# design.net
KiCad netlist of a schematic drawn in Altium Designer
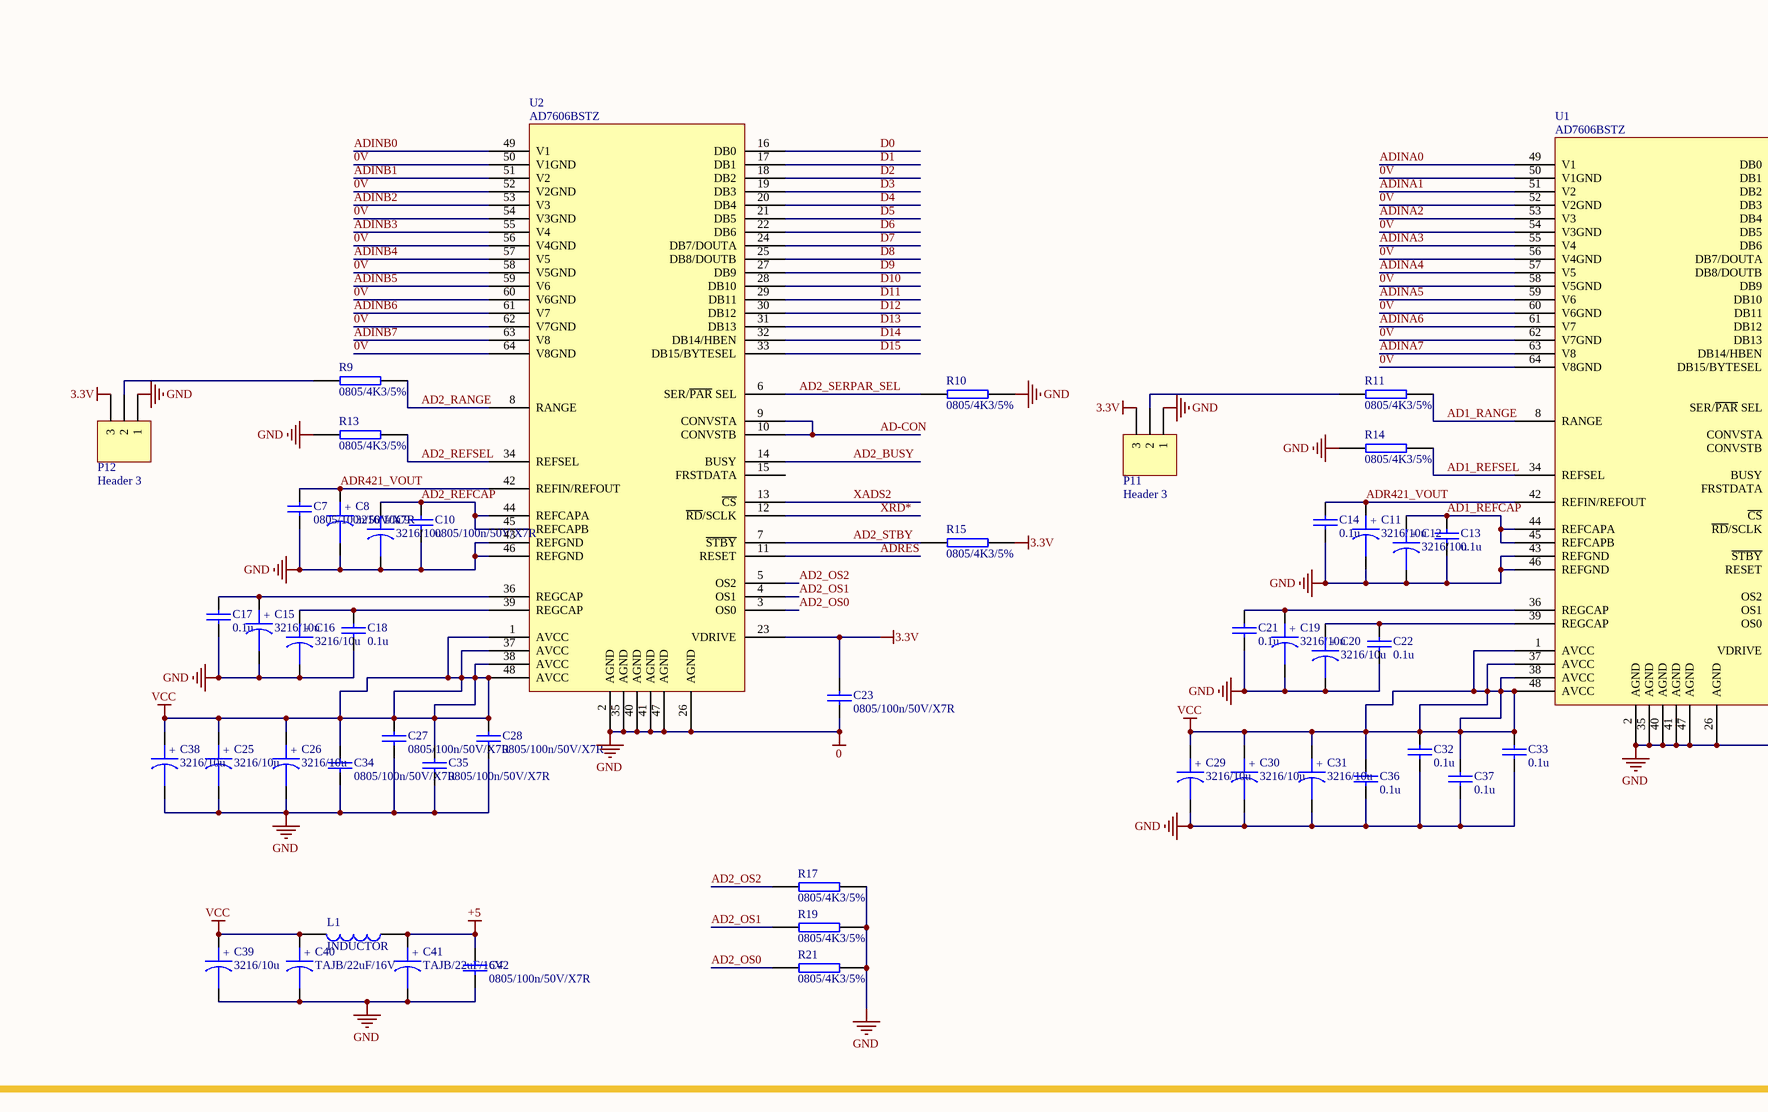
[diagram p0: 底板原理图.SchDoc, top left]
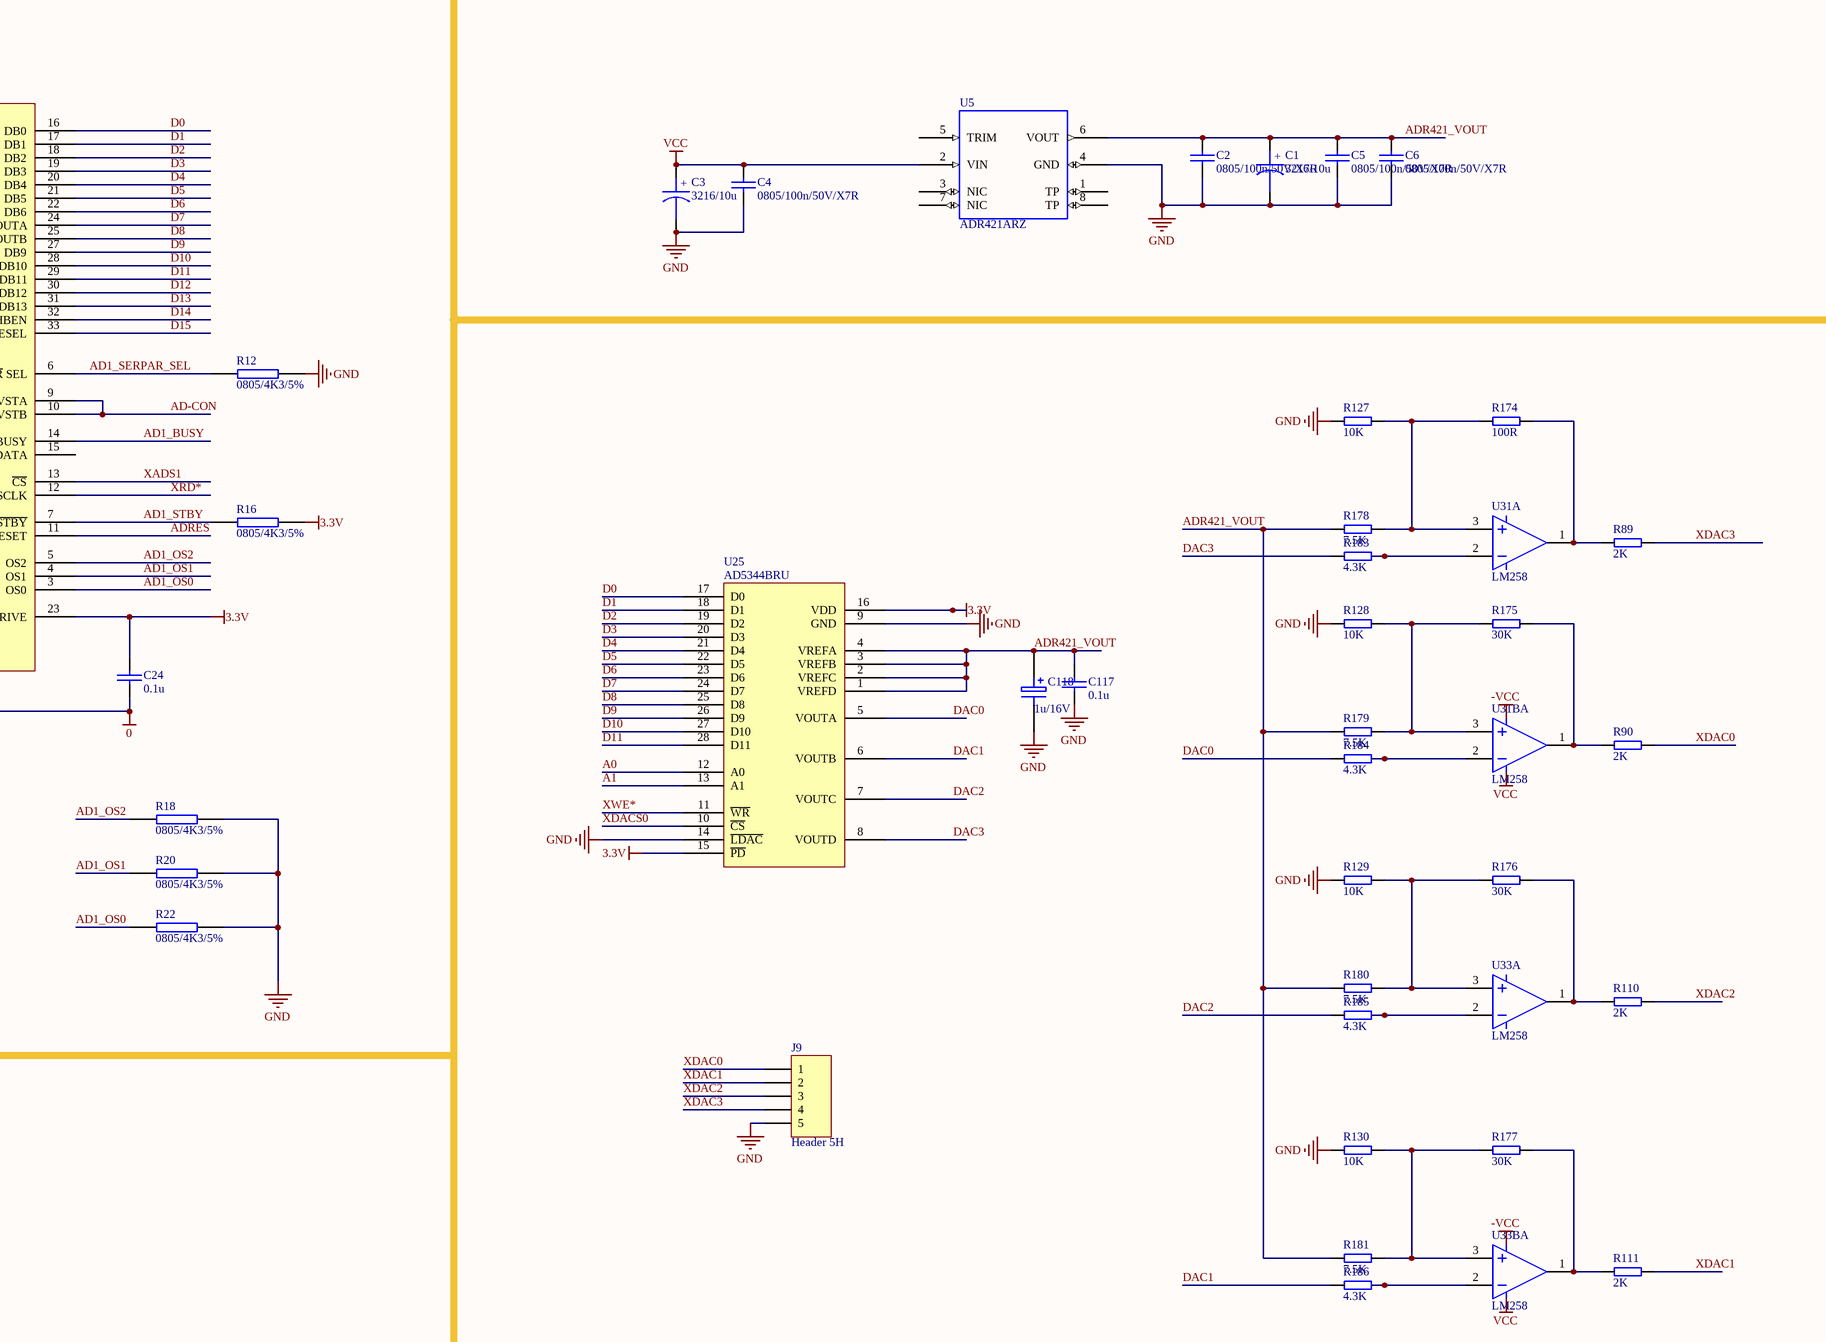
[diagram p1: 底板原理图.SchDoc, top middle]
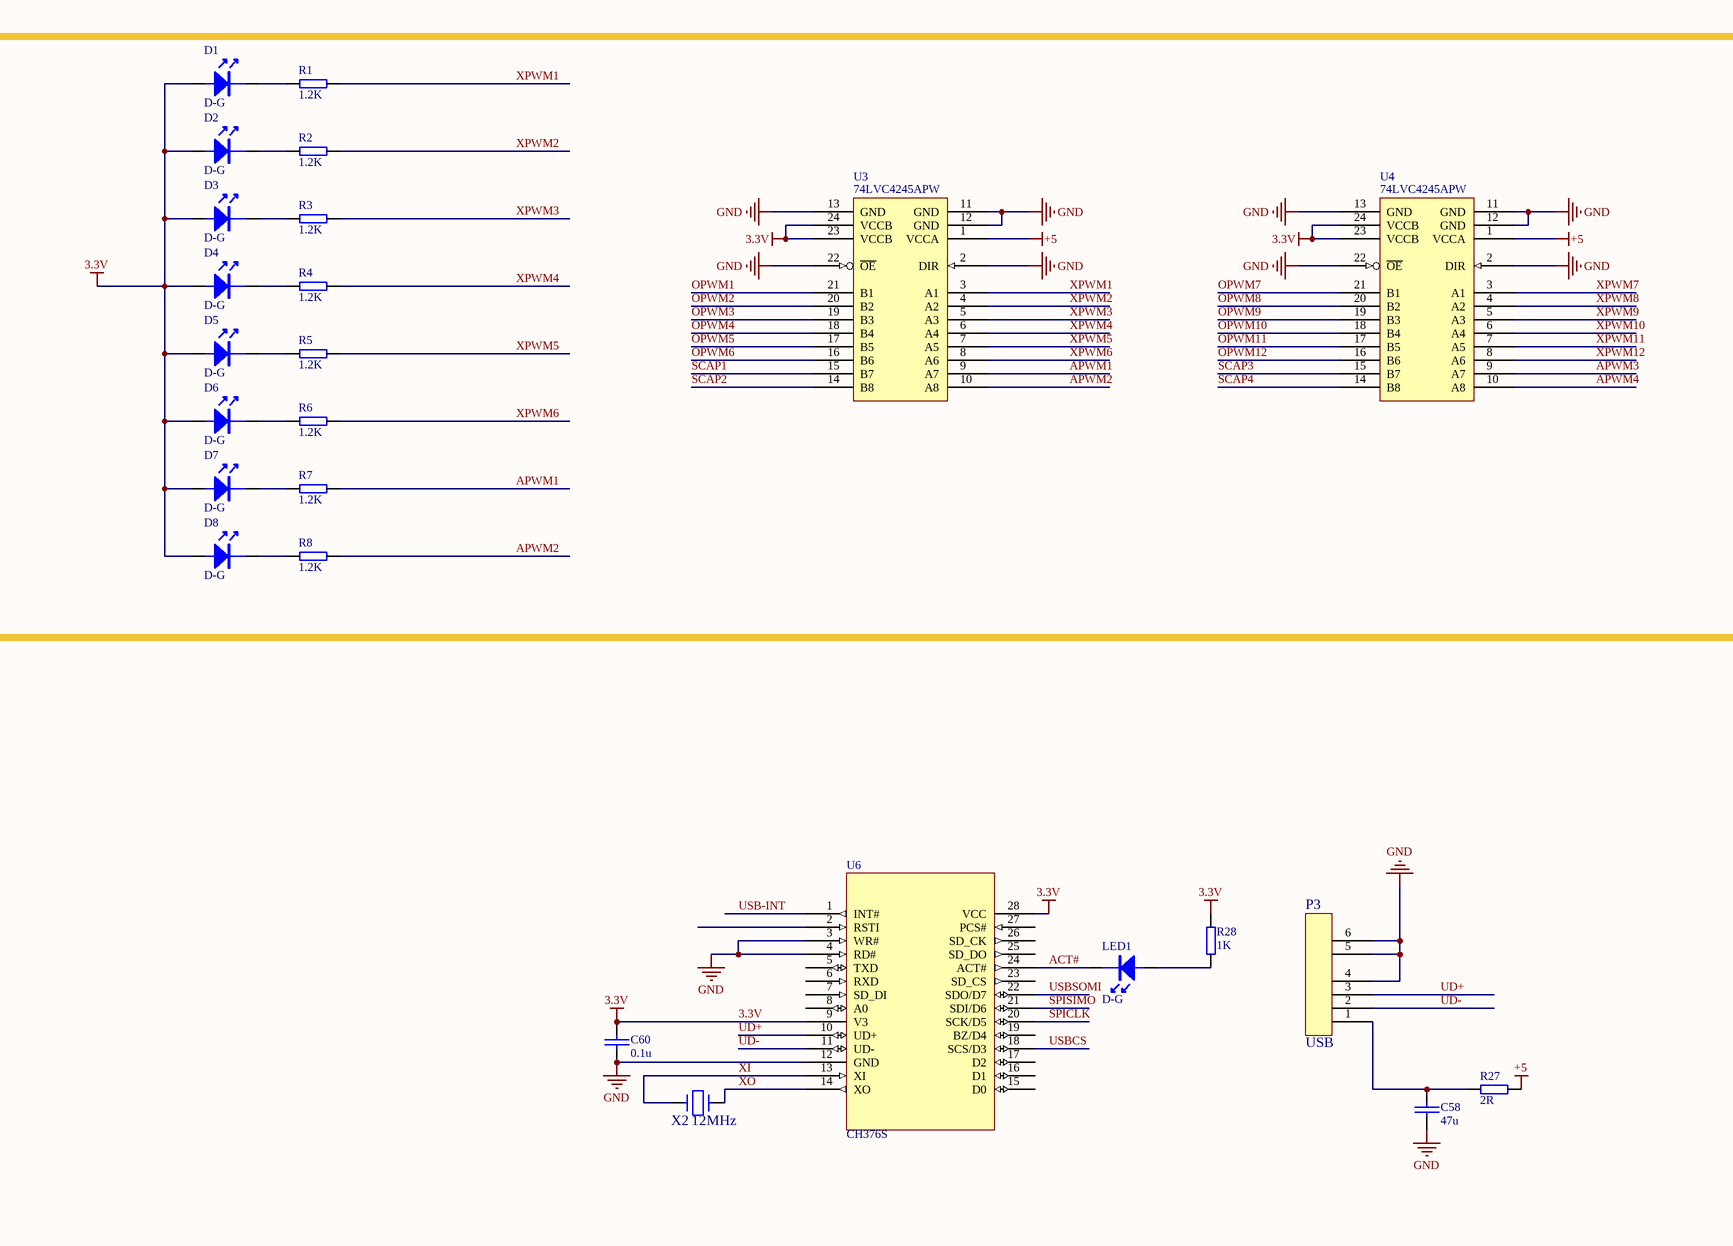
[diagram p2: 底板原理图.SchDoc, top right]
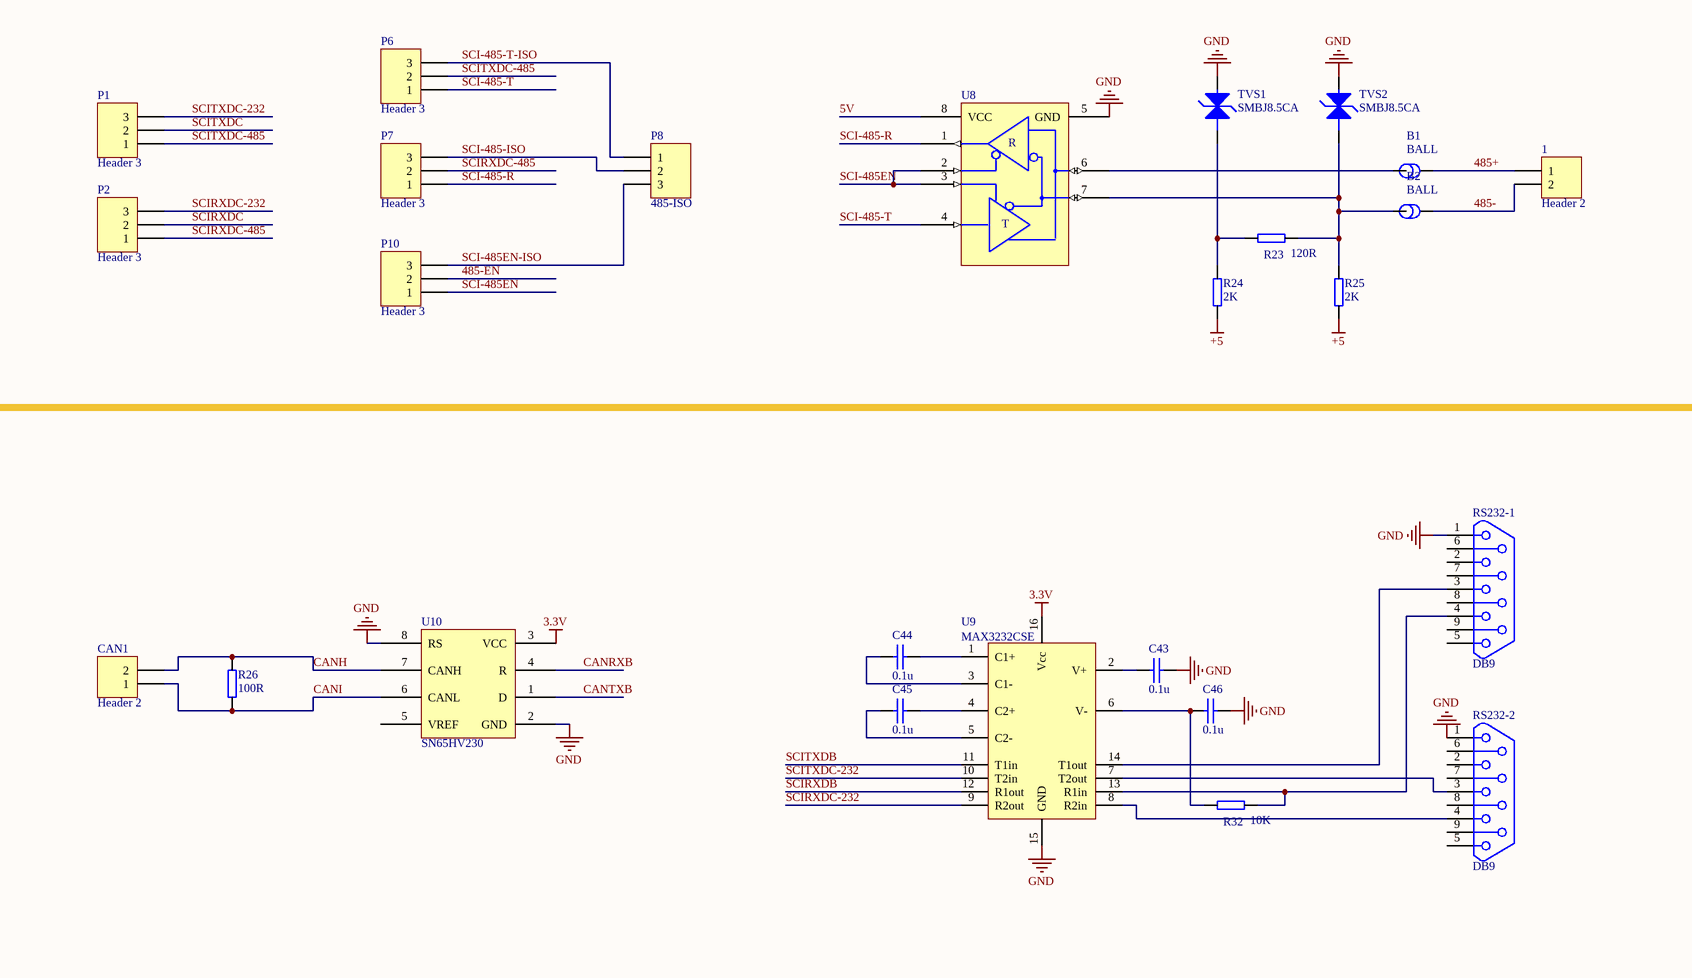
[diagram p3: 底板原理图.SchDoc, centre left]
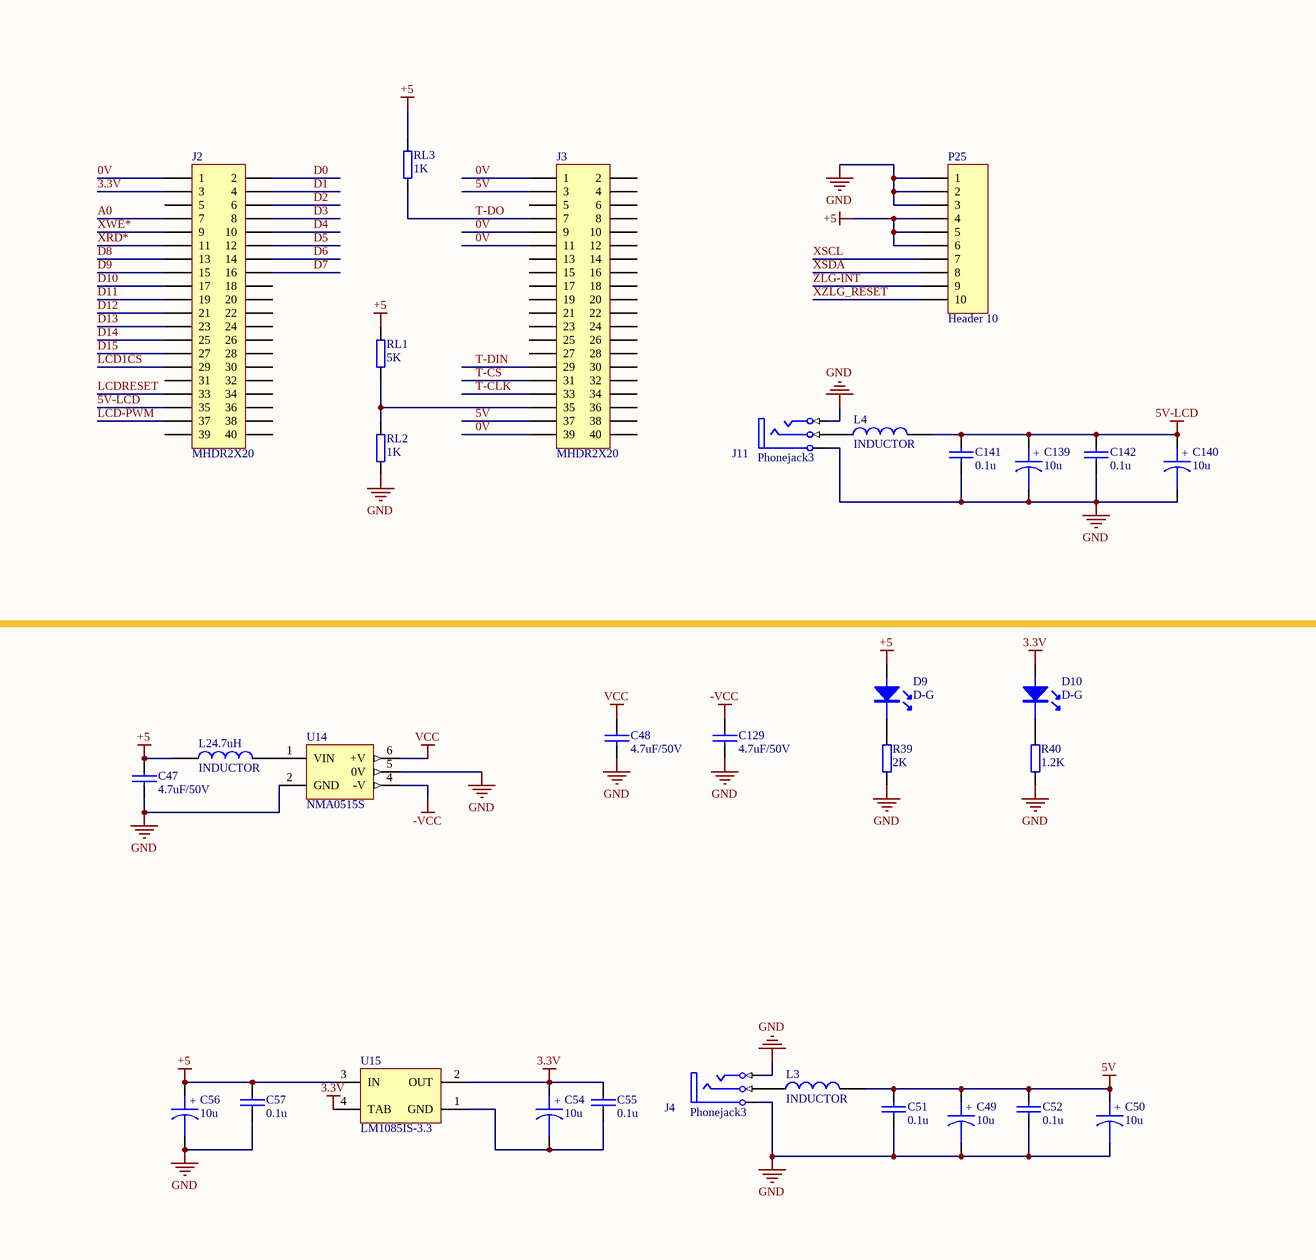
[diagram p4: 底板原理图.SchDoc, centre middle]
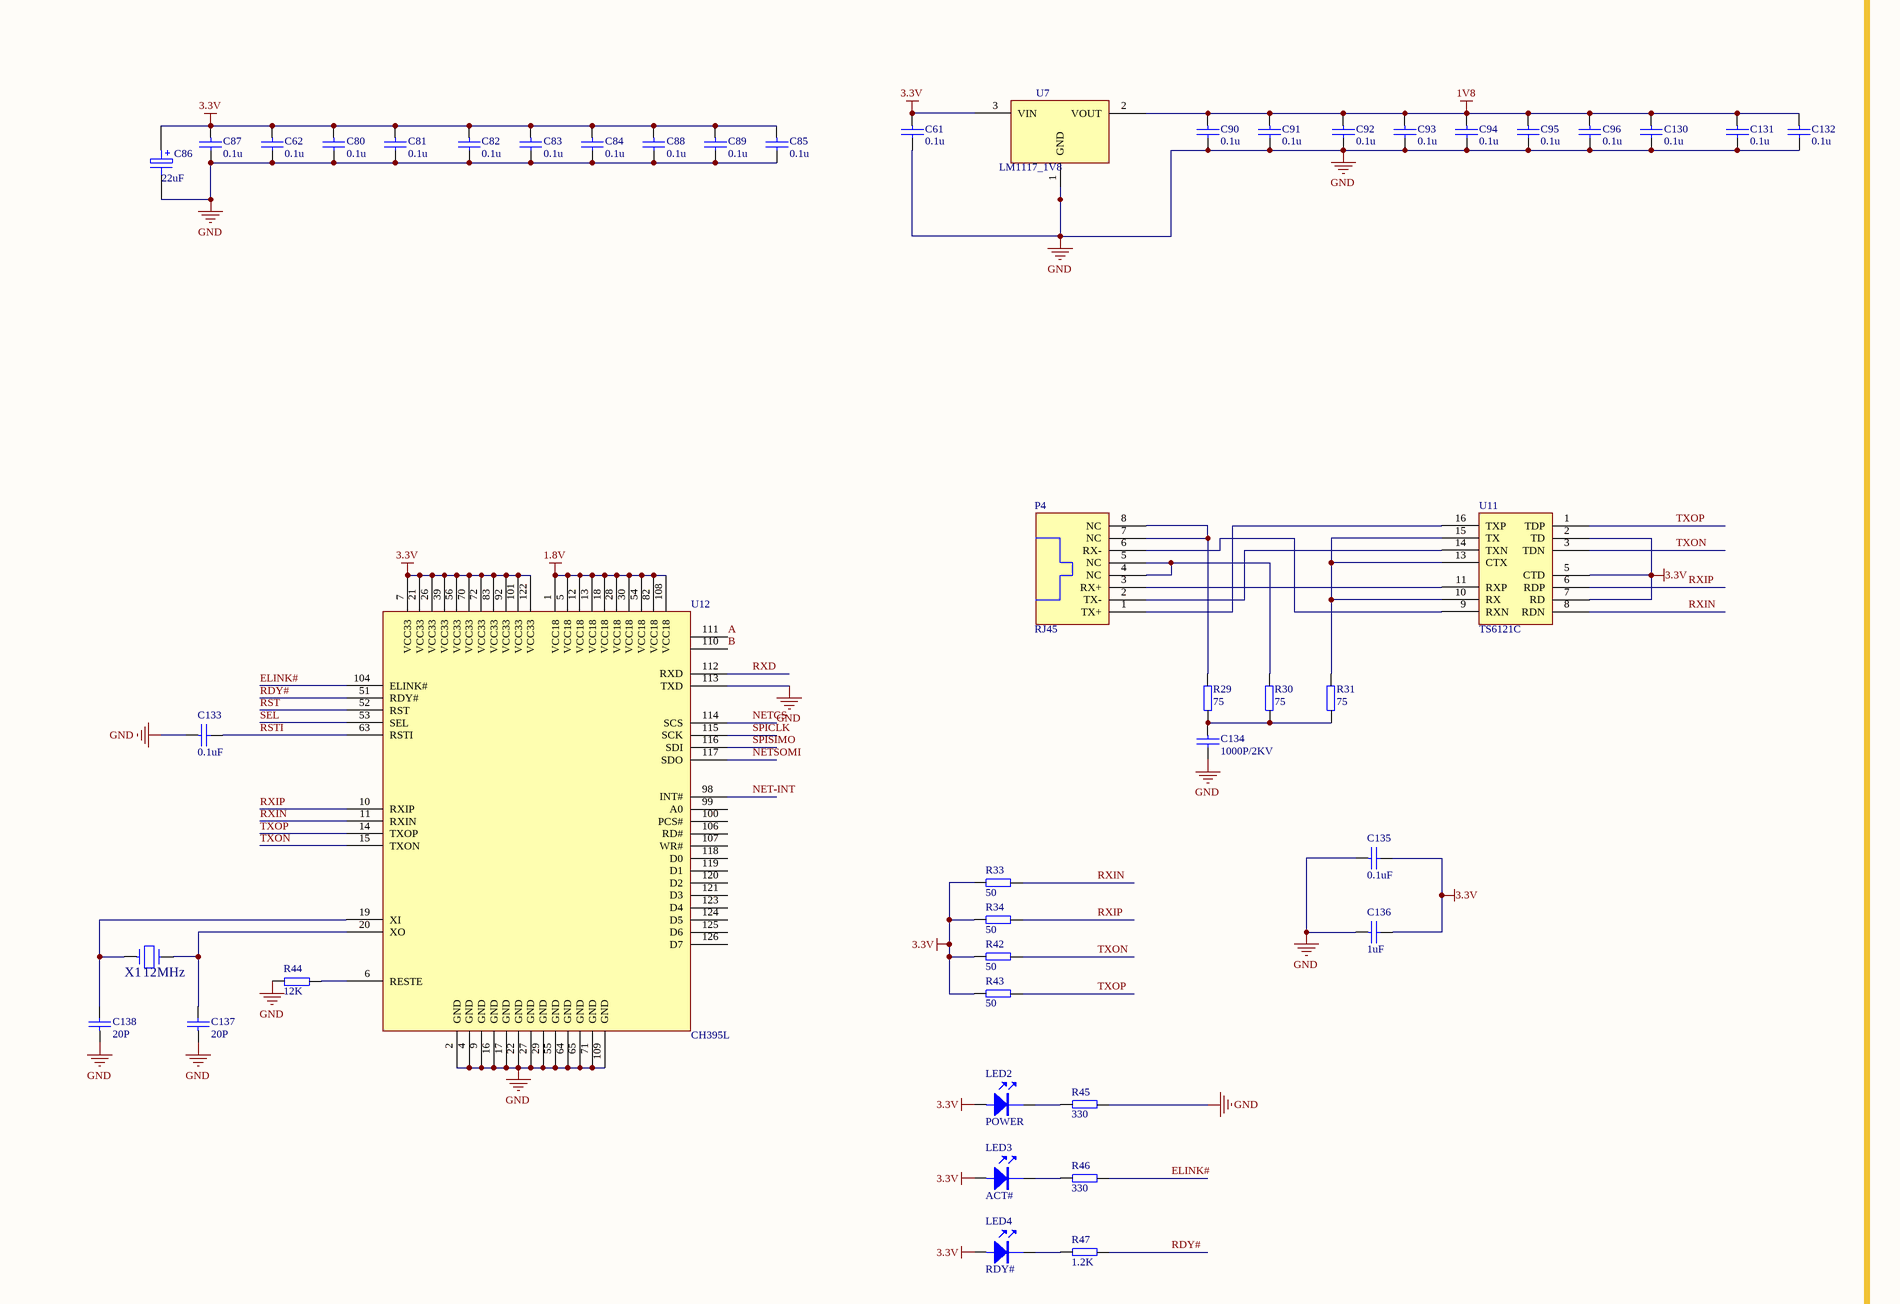
[diagram p5: 底板原理图.SchDoc, centre right]
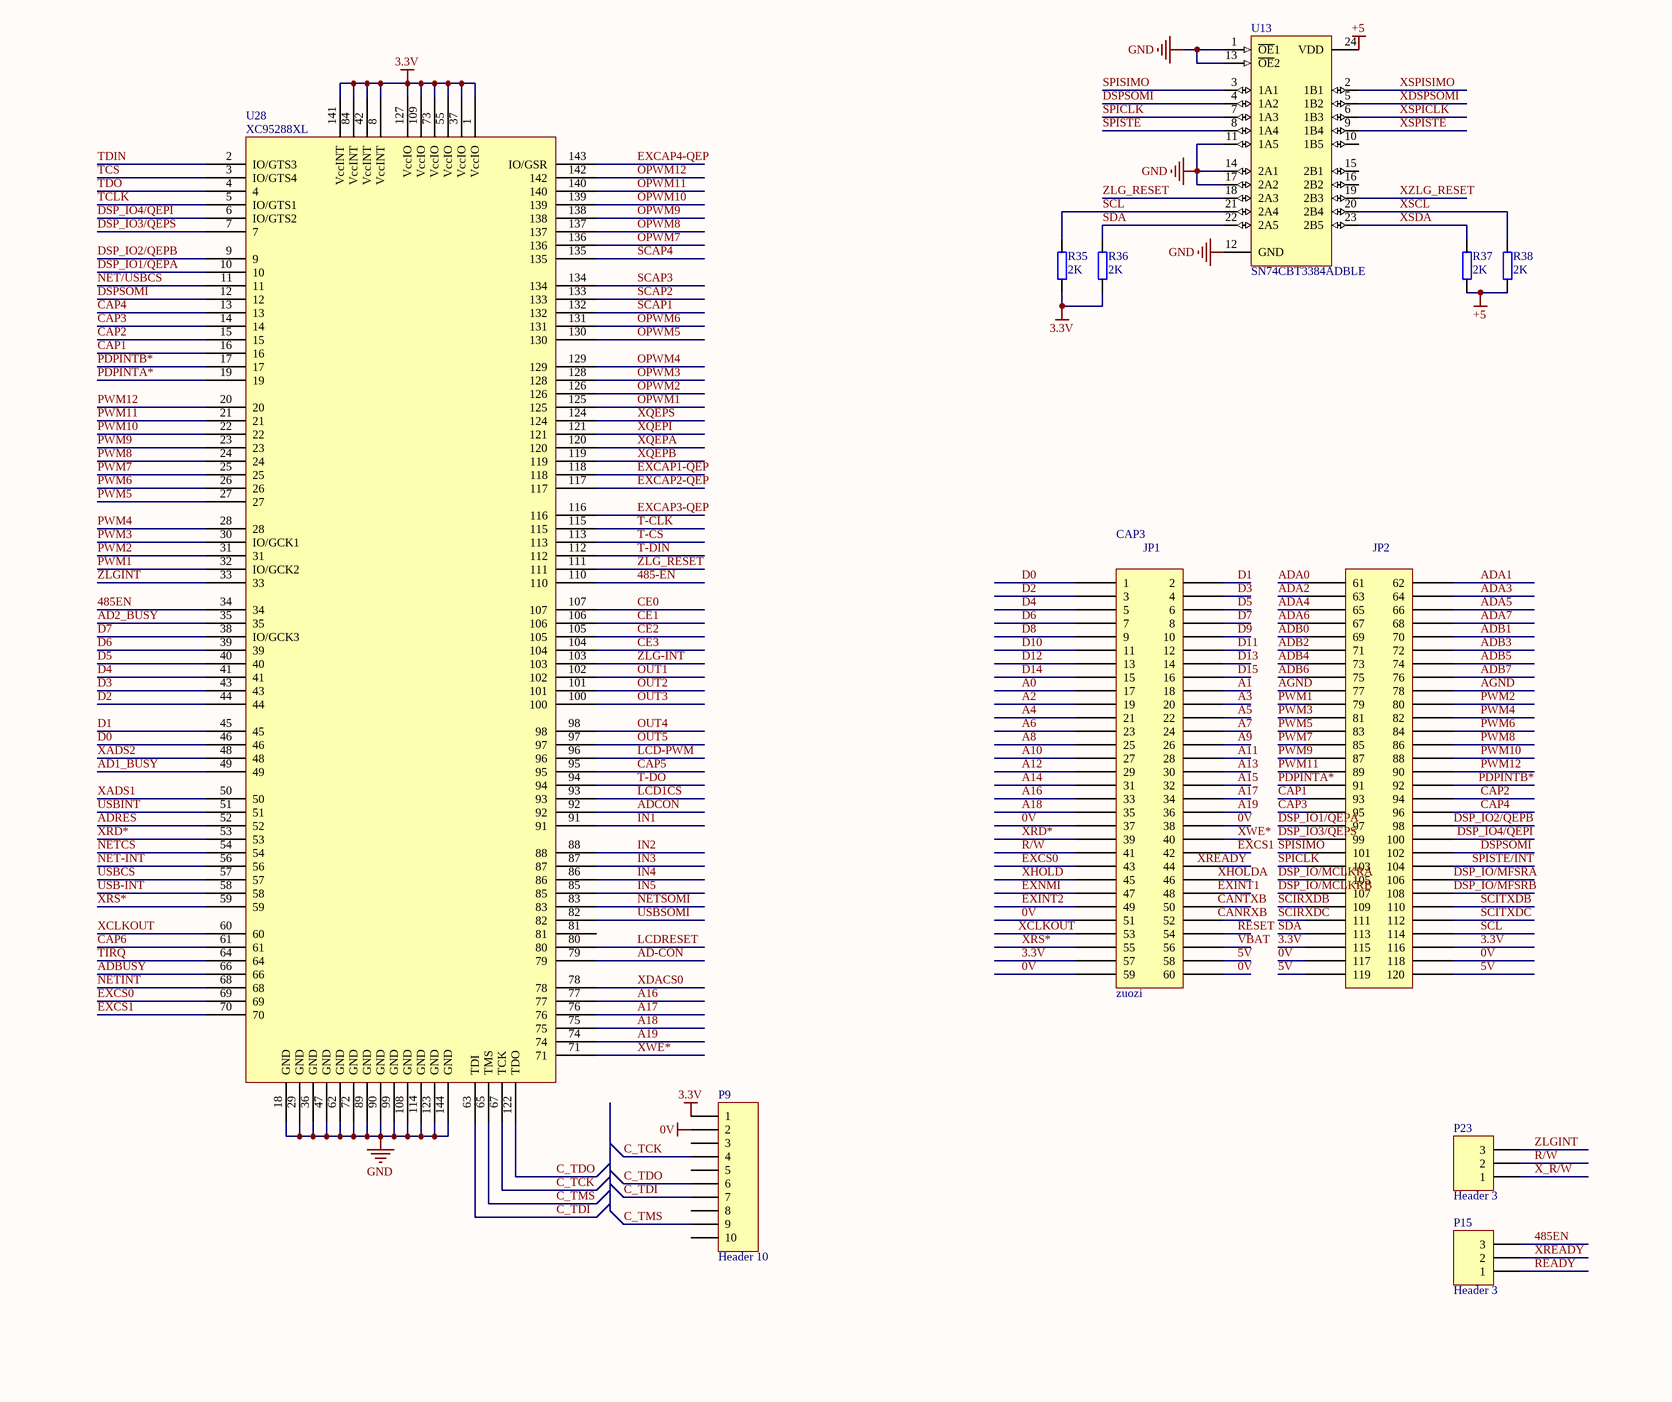
[diagram p6: 底板原理图.SchDoc, bottom left]
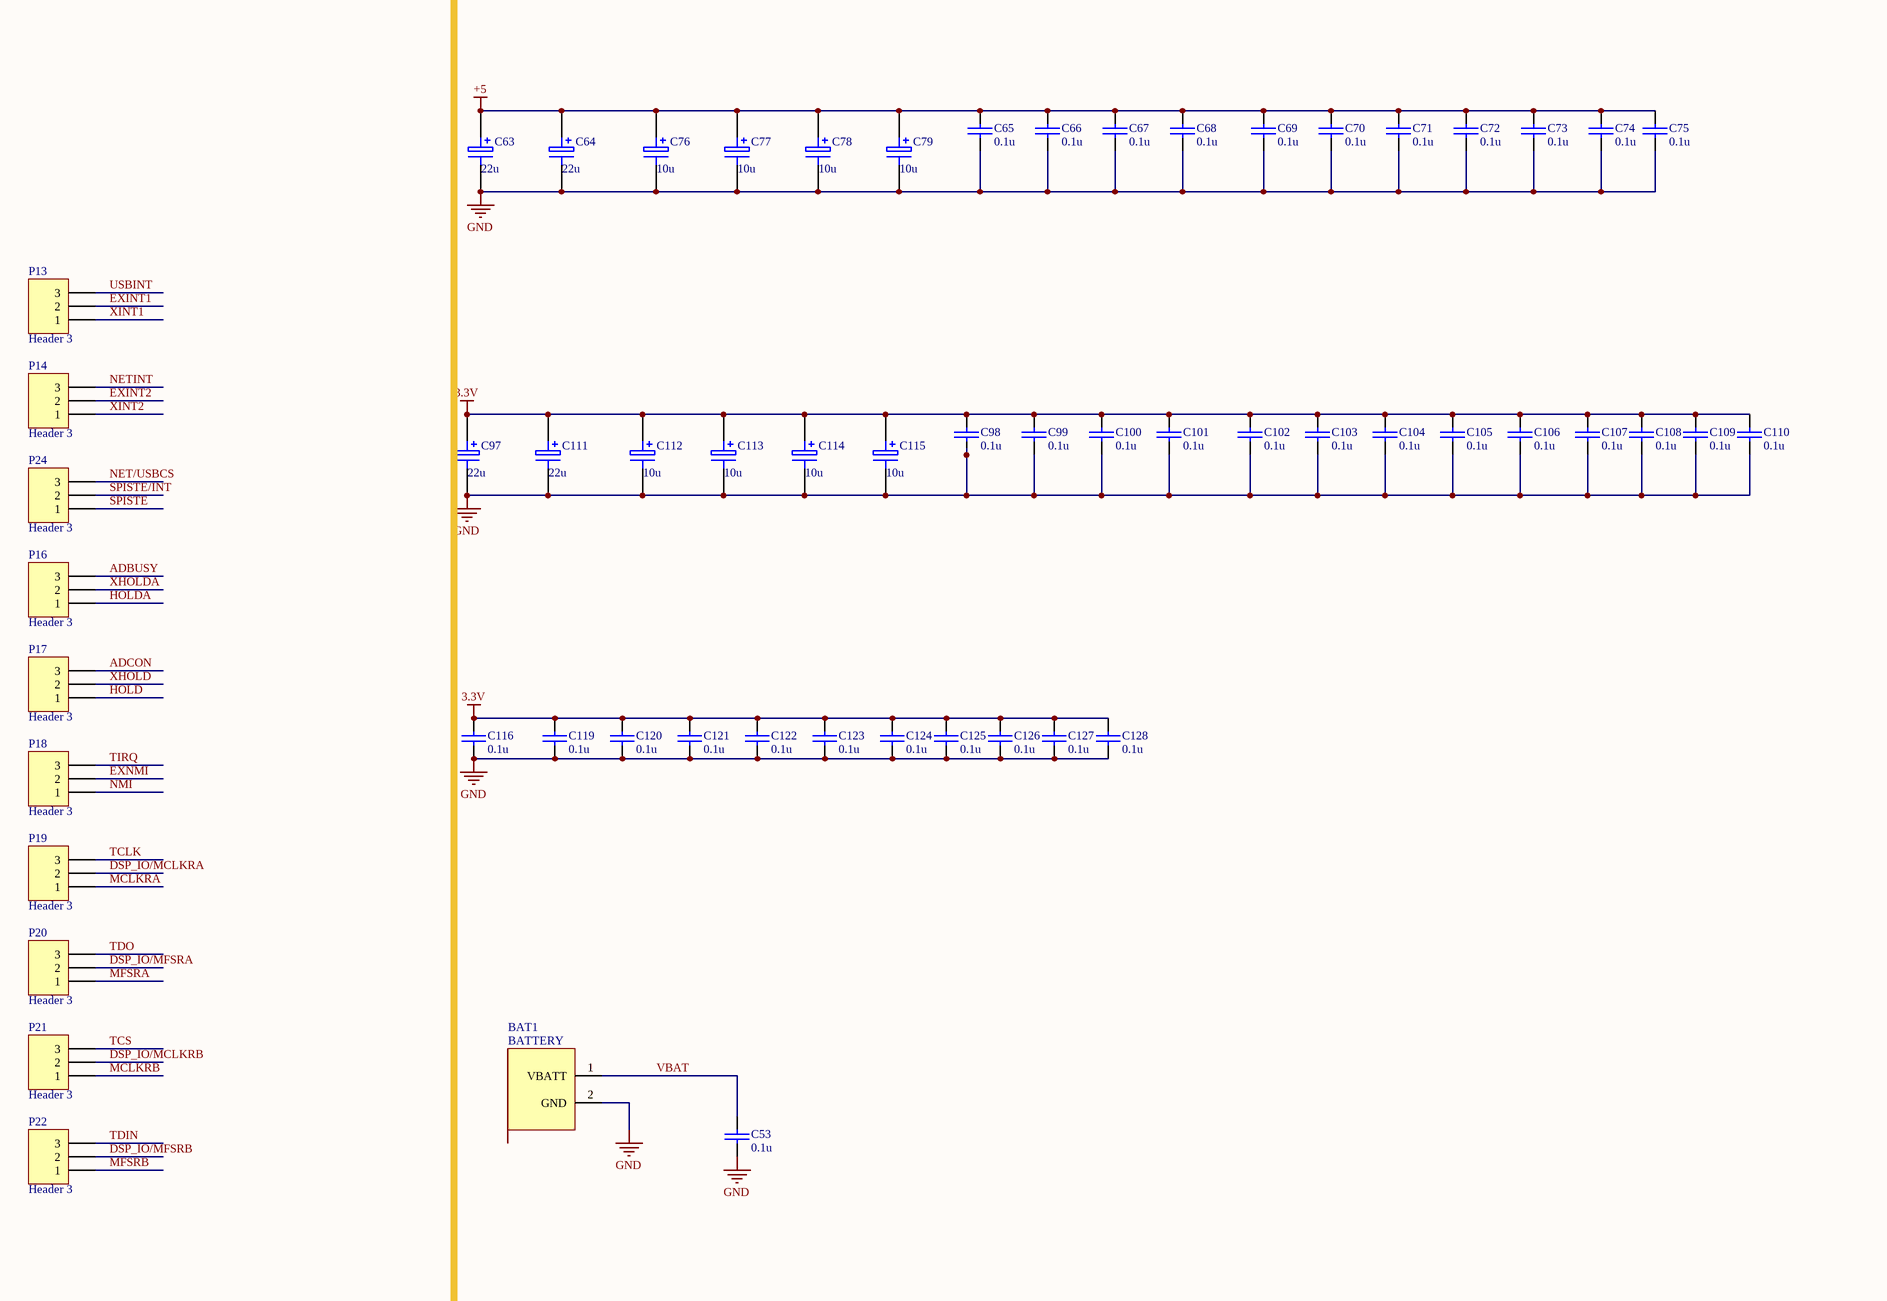
[diagram p7: 底板原理图.SchDoc, bottom middle]
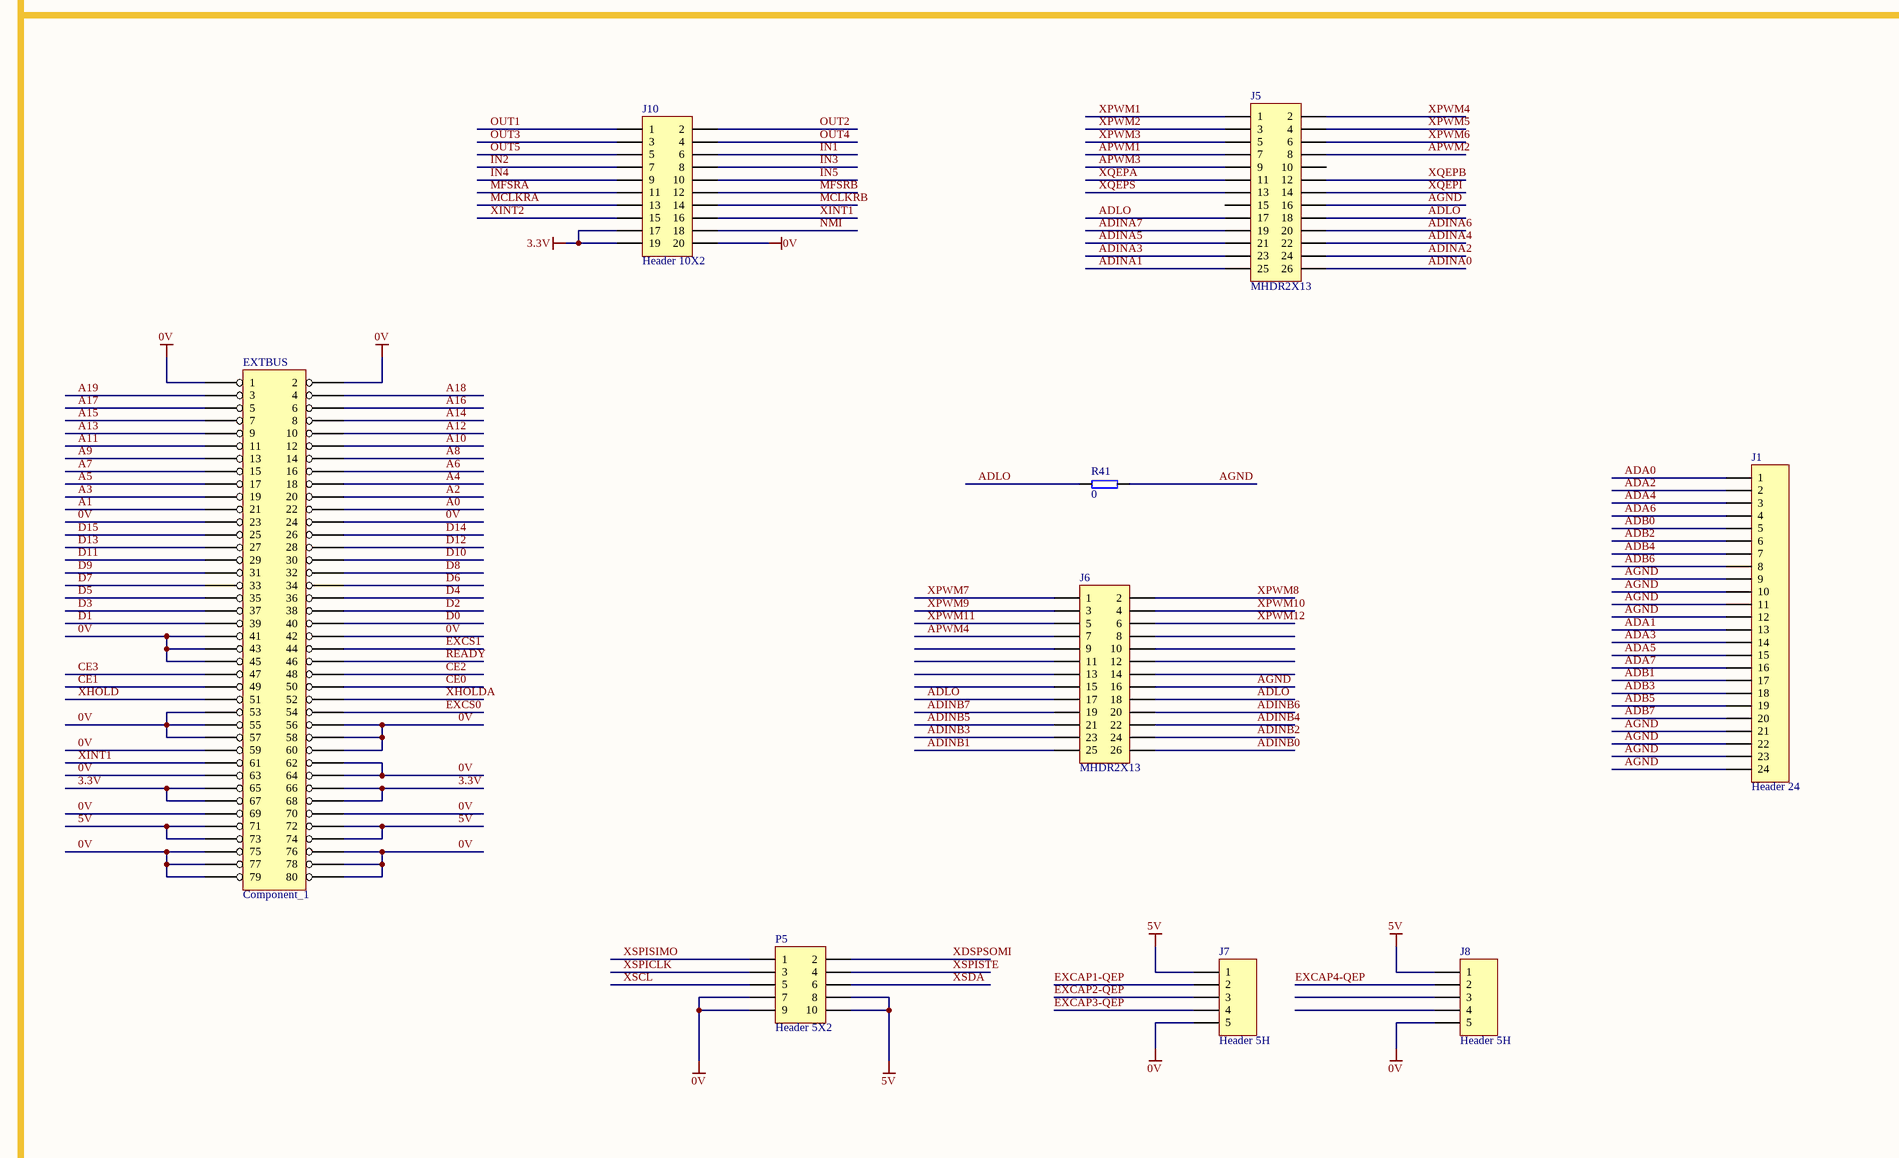
[diagram p8: 底板原理图.SchDoc, bottom right]

(export (version "E")
  (design (tool "Eeschema 10.0.6"))
  (components
    (comp (ref "1")
      (value "Header 2")
      (footprint "HDR1X2")
      (description "Header, 2-Pin")
      (fields (field (name "PUBLISHER") "Altium Limited"))
      (libsource (lib "") (part "Header 2_1"))
    )
    (comp (ref "B1") (value "BALL") (footprint "0805-S") (libsource (lib "*") (part "BALL/S")))
    (comp (ref "B2") (value "BALL") (footprint "0805-S") (libsource (lib "*") (part "BALL/S")))
    (comp (ref "BAT1") (value "BATTERY") (footprint "BAT600") (libsource (lib "*") (part "BATTERY")))
    (comp (ref "C1")
      (value "3216/10u")
      (footprint "3216")
      (description "Capacitor")
      (libsource (lib "*") (part "CAPACITOR POL"))
    )
    (comp (ref "C2") (value "0805/100n/50V/X7R") (footprint "0805") (libsource (lib "*") (part "C")))
    (comp (ref "C3")
      (value "3216/10u")
      (footprint "3216")
      (description "Capacitor")
      (libsource (lib "*") (part "CAPACITOR POL"))
    )
    (comp (ref "C4") (value "0805/100n/50V/X7R") (footprint "0805") (libsource (lib "*") (part "C")))
    (comp (ref "C5") (value "0805/100n/50V/X7R") (footprint "0805") (libsource (lib "*") (part "C")))
    (comp (ref "C6") (value "0805/100n/50V/X7R") (footprint "0805") (libsource (lib "*") (part "C")))
    (comp (ref "C7") (value "0805/100n/50V/X7R") (footprint "0805") (libsource (lib "*") (part "C")))
    (comp (ref "C8")
      (value "3216/10u")
      (footprint "3216")
      (description "Capacitor")
      (libsource (lib "*") (part "CAPACITOR POL"))
    )
    (comp (ref "C9")
      (value "3216/10u")
      (footprint "3216")
      (description "Capacitor")
      (libsource (lib "*") (part "CAPACITOR POL"))
    )
    (comp (ref "C10") (value "0805/100n/50V/X7R") (footprint "0805") (libsource (lib "*") (part "C")))
    (comp (ref "C11")
      (value "3216/10u")
      (footprint "3216")
      (description "Capacitor")
      (libsource (lib "*") (part "CAPACITOR POL"))
    )
    (comp (ref "C12")
      (value "3216/10u")
      (footprint "3216")
      (description "Capacitor")
      (libsource (lib "*") (part "CAPACITOR POL"))
    )
    (comp (ref "C13") (value "0.1u") (footprint "0805") (libsource (lib "*") (part "C")))
    (comp (ref "C14") (value "0.1u") (footprint "0805") (libsource (lib "*") (part "C")))
    (comp (ref "C15")
      (value "3216/10u")
      (footprint "3216")
      (description "Capacitor")
      (libsource (lib "*") (part "CAPACITOR POL"))
    )
    (comp (ref "C16")
      (value "3216/10u")
      (footprint "3216")
      (description "Capacitor")
      (libsource (lib "*") (part "CAPACITOR POL"))
    )
    (comp (ref "C17") (value "0.1u") (footprint "0805") (libsource (lib "*") (part "C")))
    (comp (ref "C18") (value "0.1u") (footprint "0805") (libsource (lib "*") (part "C")))
    (comp (ref "C19")
      (value "3216/10u")
      (footprint "3216")
      (description "Capacitor")
      (libsource (lib "*") (part "CAPACITOR POL"))
    )
    (comp (ref "C20")
      (value "3216/10u")
      (footprint "3216")
      (description "Capacitor")
      (libsource (lib "*") (part "CAPACITOR POL"))
    )
    (comp (ref "C21") (value "0.1u") (footprint "0805") (libsource (lib "*") (part "C")))
    (comp (ref "C22") (value "0.1u") (footprint "0805") (libsource (lib "*") (part "C")))
    (comp (ref "C23") (value "0805/100n/50V/X7R") (footprint "0805") (libsource (lib "*") (part "C")))
    (comp (ref "C24") (value "0.1u") (footprint "0805") (libsource (lib "*") (part "C")))
    (comp (ref "C25")
      (value "3216/10u")
      (footprint "3216")
      (description "Capacitor")
      (libsource (lib "*") (part "CAPACITOR POL"))
    )
    (comp (ref "C26")
      (value "3216/10u")
      (footprint "3216")
      (description "Capacitor")
      (libsource (lib "*") (part "CAPACITOR POL"))
    )
    (comp (ref "C27") (value "0805/100n/50V/X7R") (footprint "0805") (libsource (lib "*") (part "C")))
    (comp (ref "C28") (value "0805/100n/50V/X7R") (footprint "0805") (libsource (lib "*") (part "C")))
    (comp (ref "C29")
      (value "3216/10u")
      (footprint "3216")
      (description "Capacitor")
      (libsource (lib "*") (part "CAPACITOR POL"))
    )
    (comp (ref "C30")
      (value "3216/10u")
      (footprint "3216")
      (description "Capacitor")
      (libsource (lib "*") (part "CAPACITOR POL"))
    )
    (comp (ref "C31")
      (value "3216/10u")
      (footprint "3216")
      (description "Capacitor")
      (libsource (lib "*") (part "CAPACITOR POL"))
    )
    (comp (ref "C32") (value "0.1u") (footprint "0805") (libsource (lib "*") (part "C")))
    (comp (ref "C33") (value "0.1u") (footprint "0805") (libsource (lib "*") (part "C")))
    (comp (ref "C34") (value "0805/100n/50V/X7R") (footprint "0805") (libsource (lib "*") (part "C")))
    (comp (ref "C35") (value "0805/100n/50V/X7R") (footprint "0805") (libsource (lib "*") (part "C")))
    (comp (ref "C36") (value "0.1u") (footprint "0805") (libsource (lib "*") (part "C")))
    (comp (ref "C37") (value "0.1u") (footprint "0805") (libsource (lib "*") (part "C")))
    (comp (ref "C38")
      (value "3216/10u")
      (footprint "3216")
      (description "Capacitor")
      (libsource (lib "*") (part "CAPACITOR POL"))
    )
    (comp (ref "C39")
      (value "3216/10u")
      (footprint "3216")
      (description "Capacitor")
      (libsource (lib "*") (part "CAPACITOR POL"))
    )
    (comp (ref "C40")
      (value "TAJB/22uF/16V")
      (footprint "3216")
      (description "Capacitor")
      (libsource (lib "*") (part "CAPACITOR POL"))
    )
    (comp (ref "C41")
      (value "TAJB/22uF/16V")
      (footprint "3216")
      (description "Capacitor")
      (libsource (lib "*") (part "CAPACITOR POL"))
    )
    (comp (ref "C42") (value "0805/100n/50V/X7R") (footprint "0805") (libsource (lib "*") (part "C")))
    (comp (ref "C43") (value "0.1u") (footprint "0805") (libsource (lib "*") (part "C")))
    (comp (ref "C44") (value "0.1u") (footprint "0805") (libsource (lib "*") (part "C")))
    (comp (ref "C45") (value "0.1u") (footprint "0805") (libsource (lib "*") (part "C")))
    (comp (ref "C46") (value "0.1u") (footprint "0805") (libsource (lib "*") (part "C")))
    (comp (ref "C47") (value "4.7uF/50V") (footprint "0805") (libsource (lib "*") (part "C")))
    (comp (ref "C48") (value "4.7uF/50V") (footprint "0805") (libsource (lib "*") (part "C")))
    (comp (ref "C49")
      (value "10u")
      (footprint "3216")
      (description "Capacitor")
      (libsource (lib "*") (part "CAPACITOR POL"))
    )
    (comp (ref "C50")
      (value "10u")
      (footprint "3216")
      (description "Capacitor")
      (libsource (lib "*") (part "CAPACITOR POL"))
    )
    (comp (ref "C51") (value "0.1u") (footprint "0805") (libsource (lib "*") (part "C")))
    (comp (ref "C52") (value "0.1u") (footprint "0805") (libsource (lib "*") (part "C")))
    (comp (ref "C53") (value "0.1u") (footprint "0805") (libsource (lib "*") (part "C")))
    (comp (ref "C54")
      (value "10u")
      (footprint "3216")
      (description "Capacitor")
      (libsource (lib "*") (part "CAPACITOR POL"))
    )
    (comp (ref "C55") (value "0.1u") (footprint "0805") (libsource (lib "*") (part "C")))
    (comp (ref "C56")
      (value "10u")
      (footprint "3216")
      (description "Capacitor")
      (libsource (lib "*") (part "CAPACITOR POL"))
    )
    (comp (ref "C57") (value "0.1u") (footprint "0805") (libsource (lib "*") (part "C")))
    (comp (ref "C58") (value "47u") (footprint "0805") (libsource (lib "*") (part "C")))
    (comp (ref "C60") (value "0.1u") (footprint "0805") (libsource (lib "*") (part "C")))
    (comp (ref "C61") (value "0.1u") (footprint "0805") (libsource (lib "*") (part "C")))
    (comp (ref "C62") (value "0.1u") (footprint "0805") (libsource (lib "*") (part "C")))
    (comp (ref "C63")
      (value "22u")
      (footprint "3528")
      (description "Electrolytic Capacitor")
      (libsource (lib "*") (part "ELECTRO1"))
    )
    (comp (ref "C64")
      (value "22u")
      (footprint "3528")
      (description "Electrolytic Capacitor")
      (libsource (lib "*") (part "ELECTRO1"))
    )
    (comp (ref "C65") (value "0.1u") (footprint "0805") (libsource (lib "*") (part "C")))
    (comp (ref "C66") (value "0.1u") (footprint "0805") (libsource (lib "*") (part "C")))
    (comp (ref "C67") (value "0.1u") (footprint "0805") (libsource (lib "*") (part "C")))
    (comp (ref "C68") (value "0.1u") (footprint "0805") (libsource (lib "*") (part "C")))
    (comp (ref "C69") (value "0.1u") (footprint "0805") (libsource (lib "*") (part "C")))
    (comp (ref "C70") (value "0.1u") (footprint "0805") (libsource (lib "*") (part "C")))
    (comp (ref "C71") (value "0.1u") (footprint "0805") (libsource (lib "*") (part "C")))
    (comp (ref "C72") (value "0.1u") (footprint "0805") (libsource (lib "*") (part "C")))
    (comp (ref "C73") (value "0.1u") (footprint "0805") (libsource (lib "*") (part "C")))
    (comp (ref "C74") (value "0.1u") (footprint "0805") (libsource (lib "*") (part "C")))
    (comp (ref "C75") (value "0.1u") (footprint "0805") (libsource (lib "*") (part "C")))
    (comp (ref "C76")
      (value "10u")
      (footprint "3528")
      (description "Electrolytic Capacitor")
      (libsource (lib "*") (part "ELECTRO1"))
    )
    (comp (ref "C77")
      (value "10u")
      (footprint "3528")
      (description "Electrolytic Capacitor")
      (libsource (lib "*") (part "ELECTRO1"))
    )
    (comp (ref "C78")
      (value "10u")
      (footprint "3528")
      (description "Electrolytic Capacitor")
      (libsource (lib "*") (part "ELECTRO1"))
    )
    (comp (ref "C79")
      (value "10u")
      (footprint "3528")
      (description "Electrolytic Capacitor")
      (libsource (lib "*") (part "ELECTRO1"))
    )
    (comp (ref "C80") (value "0.1u") (footprint "0805") (libsource (lib "*") (part "C")))
    (comp (ref "C81") (value "0.1u") (footprint "0805") (libsource (lib "*") (part "C")))
    (comp (ref "C82") (value "0.1u") (footprint "0805") (libsource (lib "*") (part "C")))
    (comp (ref "C83") (value "0.1u") (footprint "0805") (libsource (lib "*") (part "C")))
    (comp (ref "C84") (value "0.1u") (footprint "0805") (libsource (lib "*") (part "C")))
    (comp (ref "C85") (value "0.1u") (footprint "0805") (libsource (lib "*") (part "C")))
    (comp (ref "C86")
      (value "22uF")
      (footprint "3528")
      (description "Electrolytic Capacitor")
      (libsource (lib "*") (part "ELECTRO1"))
    )
    (comp (ref "C87") (value "0.1u") (footprint "0805") (libsource (lib "*") (part "C")))
    (comp (ref "C88") (value "0.1u") (footprint "0805") (libsource (lib "*") (part "C")))
    (comp (ref "C89") (value "0.1u") (footprint "0805") (libsource (lib "*") (part "C")))
    (comp (ref "C90") (value "0.1u") (footprint "0805") (libsource (lib "*") (part "C")))
    (comp (ref "C91") (value "0.1u") (footprint "0805") (libsource (lib "*") (part "C")))
    (comp (ref "C92") (value "0.1u") (footprint "0805") (libsource (lib "*") (part "C")))
    (comp (ref "C93") (value "0.1u") (footprint "0805") (libsource (lib "*") (part "C")))
    (comp (ref "C94") (value "0.1u") (footprint "0805") (libsource (lib "*") (part "C")))
    (comp (ref "C95") (value "0.1u") (footprint "0805") (libsource (lib "*") (part "C")))
    (comp (ref "C96") (value "0.1u") (footprint "0805") (libsource (lib "*") (part "C")))
    (comp (ref "C97")
      (value "22u")
      (footprint "3528")
      (description "Electrolytic Capacitor")
      (libsource (lib "*") (part "ELECTRO1"))
    )
    (comp (ref "C98") (value "0.1u") (footprint "0805") (libsource (lib "*") (part "C")))
    (comp (ref "C99") (value "0.1u") (footprint "0805") (libsource (lib "*") (part "C")))
    (comp (ref "C100") (value "0.1u") (footprint "0805") (libsource (lib "*") (part "C")))
    (comp (ref "C101") (value "0.1u") (footprint "0805") (libsource (lib "*") (part "C")))
    (comp (ref "C102") (value "0.1u") (footprint "0805") (libsource (lib "*") (part "C")))
    (comp (ref "C103") (value "0.1u") (footprint "0805") (libsource (lib "*") (part "C")))
    (comp (ref "C104") (value "0.1u") (footprint "0805") (libsource (lib "*") (part "C")))
    (comp (ref "C105") (value "0.1u") (footprint "0805") (libsource (lib "*") (part "C")))
    (comp (ref "C106") (value "0.1u") (footprint "0805") (libsource (lib "*") (part "C")))
    (comp (ref "C107") (value "0.1u") (footprint "0805") (libsource (lib "*") (part "C")))
    (comp (ref "C108") (value "0.1u") (footprint "0805") (libsource (lib "*") (part "C")))
    (comp (ref "C109") (value "0.1u") (footprint "0805") (libsource (lib "*") (part "C")))
    (comp (ref "C110") (value "0.1u") (footprint "0805") (libsource (lib "*") (part "C")))
    (comp (ref "C111")
      (value "22u")
      (footprint "3528")
      (description "Electrolytic Capacitor")
      (libsource (lib "*") (part "ELECTRO1"))
    )
    (comp (ref "C112")
      (value "10u")
      (footprint "3528")
      (description "Electrolytic Capacitor")
      (libsource (lib "*") (part "ELECTRO1"))
    )
    (comp (ref "C113")
      (value "10u")
      (footprint "3528")
      (description "Electrolytic Capacitor")
      (libsource (lib "*") (part "ELECTRO1"))
    )
    (comp (ref "C114")
      (value "10u")
      (footprint "3528")
      (description "Electrolytic Capacitor")
      (libsource (lib "*") (part "ELECTRO1"))
    )
    (comp (ref "C115")
      (value "10u")
      (footprint "3528")
      (description "Electrolytic Capacitor")
      (libsource (lib "*") (part "ELECTRO1"))
    )
    (comp (ref "C116") (value "0.1u") (footprint "0805") (libsource (lib "*") (part "C")))
    (comp (ref "C117") (value "0.1u") (footprint "0805") (libsource (lib "*") (part "C")))
    (comp (ref "C118")
      (value "1u/16V")
      (footprint "3528")
      (description "Electrolytic Capacitor")
      (libsource (lib "*") (part "ELECTRO1"))
    )
    (comp (ref "C119") (value "0.1u") (footprint "0805") (libsource (lib "*") (part "C")))
    (comp (ref "C120") (value "0.1u") (footprint "0805") (libsource (lib "*") (part "C")))
    (comp (ref "C121") (value "0.1u") (footprint "0805") (libsource (lib "*") (part "C")))
    (comp (ref "C122") (value "0.1u") (footprint "0805") (libsource (lib "*") (part "C")))
    (comp (ref "C123") (value "0.1u") (footprint "0805") (libsource (lib "*") (part "C")))
    (comp (ref "C124") (value "0.1u") (footprint "0805") (libsource (lib "*") (part "C")))
    (comp (ref "C125") (value "0.1u") (footprint "0805") (libsource (lib "*") (part "C")))
    (comp (ref "C126") (value "0.1u") (footprint "0805") (libsource (lib "*") (part "C")))
    (comp (ref "C127") (value "0.1u") (footprint "0805") (libsource (lib "*") (part "C")))
    (comp (ref "C128") (value "0.1u") (footprint "0805") (libsource (lib "*") (part "C")))
    (comp (ref "C129") (value "4.7uF/50V") (footprint "0805") (libsource (lib "*") (part "C")))
    (comp (ref "C130") (value "0.1u") (footprint "0805") (libsource (lib "*") (part "C")))
    (comp (ref "C131") (value "0.1u") (footprint "0805") (libsource (lib "*") (part "C")))
    (comp (ref "C132") (value "0.1u") (footprint "0805") (libsource (lib "*") (part "C")))
    (comp (ref "C133") (value "0.1uF") (footprint "0805") (libsource (lib "*") (part "C")))
    (comp (ref "C134") (value "1000P/2KV") (footprint "0805") (libsource (lib "*") (part "C")))
    (comp (ref "C135") (value "0.1uF") (footprint "0805") (libsource (lib "*") (part "C")))
    (comp (ref "C136") (value "1uF") (footprint "0805") (libsource (lib "*") (part "C")))
    (comp (ref "C137") (value "20P") (footprint "0805") (libsource (lib "*") (part "C")))
    (comp (ref "C138") (value "20P") (footprint "0805") (libsource (lib "*") (part "C")))
    (comp (ref "C139")
      (value "10u")
      (footprint "3216")
      (description "Capacitor")
      (libsource (lib "*") (part "CAPACITOR POL"))
    )
    (comp (ref "C140")
      (value "10u")
      (footprint "3216")
      (description "Capacitor")
      (libsource (lib "*") (part "CAPACITOR POL"))
    )
    (comp (ref "C141") (value "0.1u") (footprint "0805") (libsource (lib "*") (part "C")))
    (comp (ref "C142") (value "0.1u") (footprint "0805") (libsource (lib "*") (part "C")))
    (comp (ref "CAN1")
      (value "Header 2")
      (footprint "HDR1X2")
      (description "Header, 2-Pin")
      (fields (field (name "PUBLISHER") "Altium Limited"))
      (libsource (lib "Miscellaneous Connectors") (part "Header 2"))
    )
    (comp (ref "CAP3") (value "zuozi") (footprint "zuozi") (libsource (lib "zuozi") (part "zuozi")))
    (comp (ref "D1") (value "D-G") (footprint "LED0805-JW") (libsource (lib "PCB_Project1") (part "LED")))
    (comp (ref "D2") (value "D-G") (footprint "LED0805-JW") (libsource (lib "PCB_Project1") (part "LED")))
    (comp (ref "D3") (value "D-G") (footprint "LED0805-JW") (libsource (lib "PCB_Project1") (part "LED")))
    (comp (ref "D4") (value "D-G") (footprint "LED0805-JW") (libsource (lib "PCB_Project1") (part "LED")))
    (comp (ref "D5") (value "D-G") (footprint "LED0805-JW") (libsource (lib "PCB_Project1") (part "LED")))
    (comp (ref "D6") (value "D-G") (footprint "LED0805-JW") (libsource (lib "PCB_Project1") (part "LED")))
    (comp (ref "D7") (value "D-G") (footprint "LED0805-JW") (libsource (lib "PCB_Project1") (part "LED")))
    (comp (ref "D8") (value "D-G") (footprint "LED0805-JW") (libsource (lib "PCB_Project1") (part "LED")))
    (comp (ref "D9") (value "D-G") (footprint "LED0805-JW") (libsource (lib "PCB_Project1") (part "LED")))
    (comp (ref "D10") (value "D-G") (footprint "LED0805-JW") (libsource (lib "PCB_Project1") (part "LED")))
    (comp (ref "EXTBUS")
      (value "Component_1")
      (footprint "PLUG80")
      (libsource (lib "*") (part "Component_1_1"))
    )
    (comp (ref "J1")
      (value "Header 24")
      (footprint "PLUG24")
      (description "Header, 24-Pin")
      (fields (field (name "PUBLISHER") "Altium Limited"))
      (libsource (lib "Miscellaneous Connectors") (part "Header 24"))
    )
    (comp (ref "J2")
      (value "MHDR2X20")
      (footprint "MHDR2X20")
      (description "Header, 20-Pin, Dual row")
      (fields (field (name "PUBLISHER") "Altium Limited"))
      (libsource (lib "Miscellaneous Connectors") (part "MHDR2X20"))
    )
    (comp (ref "J3")
      (value "MHDR2X20")
      (footprint "MHDR2X20")
      (description "Header, 20-Pin, Dual row")
      (fields (field (name "PUBLISHER") "Altium Limited"))
      (libsource (lib "Miscellaneous Connectors") (part "MHDR2X20"))
    )
    (comp (ref "J4")
      (value "Phonejack3")
      (footprint "POWER_PLUG")
      (description "Jack Socket, 1/4\" [6.5mm], Thru-Hole, Vertical, 3-Conductor Open Circuit (Non-Normalling)")
      (fields (field (name "PUBLISHER") "Altium Limited"))
      (libsource (lib "PCB_Project1") (part "Phonejack3"))
    )
    (comp (ref "J5")
      (value "MHDR2X13")
      (footprint "IDC26")
      (description "Header, 13-Pin, Dual row")
      (fields (field (name "PUBLISHER") "Altium Limited"))
      (libsource (lib "Miscellaneous Connectors") (part "MHDR2X13"))
    )
    (comp (ref "J6")
      (value "MHDR2X13")
      (footprint "IDC26")
      (description "Header, 13-Pin, Dual row")
      (fields (field (name "PUBLISHER") "Altium Limited"))
      (libsource (lib "Miscellaneous Connectors") (part "MHDR2X13"))
    )
    (comp (ref "J7")
      (value "Header 5H")
      (footprint "SIP5")
      (description "Header, 5-Pin, Right Angle")
      (fields (field (name "PUBLISHER") "Altium Limited"))
      (libsource (lib "Miscellaneous Connectors") (part "Header 5H"))
    )
    (comp (ref "J8")
      (value "Header 5H")
      (footprint "SIP5")
      (description "Header, 5-Pin, Right Angle")
      (fields (field (name "PUBLISHER") "Altium Limited"))
      (libsource (lib "Miscellaneous Connectors") (part "Header 5H"))
    )
    (comp (ref "J9")
      (value "Header 5H")
      (footprint "SIP5")
      (description "Header, 5-Pin, Right Angle")
      (fields (field (name "PUBLISHER") "Altium Limited"))
      (libsource (lib "Miscellaneous Connectors") (part "Header 5H"))
    )
    (comp (ref "J10")
      (value "Header 10X2")
      (footprint "HDR210")
      (description "Header, 10-Pin, Dual row")
      (fields (field (name "PUBLISHER") "Altium Limited"))
      (libsource (lib "Miscellaneous Connectors") (part "Header 10X2"))
    )
    (comp (ref "J11")
      (value "Phonejack3")
      (footprint "POWER_PLUG")
      (description "Jack Socket, 1/4\" [6.5mm], Thru-Hole, Vertical, 3-Conductor Open Circuit (Non-Normalling)")
      (fields (field (name "PUBLISHER") "Altium Limited"))
      (libsource (lib "PCB_Project1") (part "Phonejack3"))
    )
    (comp (ref "L1") (value "INDUCTOR") (footprint "1206") (libsource (lib "*") (part "INDUCTOR")))
    (comp (ref "L3") (value "INDUCTOR") (footprint "1206") (libsource (lib "*") (part "INDUCTOR")))
    (comp (ref "L4") (value "INDUCTOR") (footprint "1206") (libsource (lib "*") (part "INDUCTOR")))
    (comp (ref "L24.7uH") (value "INDUCTOR") (footprint "1206") (libsource (lib "*") (part "INDUCTOR")))
    (comp (ref "LED1") (value "D-G") (footprint "LED0805-JW") (libsource (lib "PCB_Project1") (part "LED")))
    (comp (ref "LED2") (value "POWER") (footprint "LED0805-JW") (libsource (lib "PCB_Project1") (part "LED")))
    (comp (ref "LED3") (value "ACT#") (footprint "LED0805-JW") (libsource (lib "PCB_Project1") (part "LED")))
    (comp (ref "LED4") (value "RDY#") (footprint "LED0805-JW") (libsource (lib "PCB_Project1") (part "LED")))
    (comp (ref "P1")
      (value "Header 3")
      (footprint "HDR1X3")
      (description "Header, 3-Pin")
      (fields (field (name "PUBLISHER") "Altium Limited"))
      (libsource (lib "Miscellaneous Connectors") (part "Header 3"))
    )
    (comp (ref "P2")
      (value "Header 3")
      (footprint "HDR1X3")
      (description "Header, 3-Pin")
      (fields (field (name "PUBLISHER") "Altium Limited"))
      (libsource (lib "Miscellaneous Connectors") (part "Header 3"))
    )
    (comp (ref "P3") (value "USB") (footprint "USBA") (libsource (lib "*") (part "Pro7B.tmp_USB_24")))
    (comp (ref "P4") (value "RJ45") (footprint "RJ45") (libsource (lib "*") (part "RJ45")))
    (comp (ref "P5")
      (value "Header 5X2")
      (footprint "DIP10-2mm")
      (description "Header, 5-Pin, Dual row")
      (fields (field (name "PUBLISHER") "Altium Limited"))
      (libsource (lib "Miscellaneous Connectors") (part "Header 5X2"))
    )
    (comp (ref "P6")
      (value "Header 3")
      (footprint "HDR1X3")
      (description "Header, 3-Pin")
      (fields (field (name "PUBLISHER") "Altium Limited"))
      (libsource (lib "Miscellaneous Connectors") (part "Header 3"))
    )
    (comp (ref "P7")
      (value "Header 3")
      (footprint "HDR1X3")
      (description "Header, 3-Pin")
      (fields (field (name "PUBLISHER") "Altium Limited"))
      (libsource (lib "Miscellaneous Connectors") (part "Header 3"))
    )
    (comp (ref "P8")
      (value "485-ISO")
      (footprint "HDR1X3")
      (description "Header, 3-Pin")
      (fields (field (name "PUBLISHER") "Altium Limited"))
      (libsource (lib "") (part "Header 3_2"))
    )
    (comp (ref "P9")
      (value "Header 10")
      (footprint "HDR110")
      (description "Header, 10-Pin")
      (fields (field (name "PUBLISHER") "Altium Limited"))
      (libsource (lib "Miscellaneous Connectors") (part "Header 10"))
    )
    (comp (ref "P10")
      (value "Header 3")
      (footprint "HDR1X3")
      (description "Header, 3-Pin")
      (fields (field (name "PUBLISHER") "Altium Limited"))
      (libsource (lib "Miscellaneous Connectors") (part "Header 3"))
    )
    (comp (ref "P11")
      (value "Header 3")
      (footprint "HDR1X3")
      (description "Header, 3-Pin")
      (fields (field (name "PUBLISHER") "Altium Limited"))
      (libsource (lib "") (part "Header 3_1"))
    )
    (comp (ref "P12")
      (value "Header 3")
      (footprint "HDR1X3")
      (description "Header, 3-Pin")
      (fields (field (name "PUBLISHER") "Altium Limited"))
      (libsource (lib "") (part "Header 3_1"))
    )
    (comp (ref "P13")
      (value "Header 3")
      (footprint "HDR1X3")
      (description "Header, 3-Pin")
      (fields (field (name "PUBLISHER") "Altium Limited"))
      (libsource (lib "Miscellaneous Connectors") (part "Header 3"))
    )
    (comp (ref "P14")
      (value "Header 3")
      (footprint "HDR1X3")
      (description "Header, 3-Pin")
      (fields (field (name "PUBLISHER") "Altium Limited"))
      (libsource (lib "Miscellaneous Connectors") (part "Header 3"))
    )
    (comp (ref "P15")
      (value "Header 3")
      (footprint "HDR1X3")
      (description "Header, 3-Pin")
      (fields (field (name "PUBLISHER") "Altium Limited"))
      (libsource (lib "Miscellaneous Connectors") (part "Header 3"))
    )
    (comp (ref "P16")
      (value "Header 3")
      (footprint "HDR1X3")
      (description "Header, 3-Pin")
      (fields (field (name "PUBLISHER") "Altium Limited"))
      (libsource (lib "Miscellaneous Connectors") (part "Header 3"))
    )
    (comp (ref "P17")
      (value "Header 3")
      (footprint "HDR1X3")
      (description "Header, 3-Pin")
      (fields (field (name "PUBLISHER") "Altium Limited"))
      (libsource (lib "Miscellaneous Connectors") (part "Header 3"))
    )
    (comp (ref "P18")
      (value "Header 3")
      (footprint "HDR1X3")
      (description "Header, 3-Pin")
      (fields (field (name "PUBLISHER") "Altium Limited"))
      (libsource (lib "Miscellaneous Connectors") (part "Header 3"))
    )
    (comp (ref "P19")
      (value "Header 3")
      (footprint "HDR1X3")
      (description "Header, 3-Pin")
      (fields (field (name "PUBLISHER") "Altium Limited"))
      (libsource (lib "Miscellaneous Connectors") (part "Header 3"))
    )
    (comp (ref "P20")
      (value "Header 3")
      (footprint "HDR1X3")
      (description "Header, 3-Pin")
      (fields (field (name "PUBLISHER") "Altium Limited"))
      (libsource (lib "Miscellaneous Connectors") (part "Header 3"))
    )
    (comp (ref "P21")
      (value "Header 3")
      (footprint "HDR1X3")
      (description "Header, 3-Pin")
      (fields (field (name "PUBLISHER") "Altium Limited"))
      (libsource (lib "Miscellaneous Connectors") (part "Header 3"))
    )
    (comp (ref "P22")
      (value "Header 3")
      (footprint "HDR1X3")
      (description "Header, 3-Pin")
      (fields (field (name "PUBLISHER") "Altium Limited"))
      (libsource (lib "Miscellaneous Connectors") (part "Header 3"))
    )
    (comp (ref "P23")
      (value "Header 3")
      (footprint "HDR1X3")
      (description "Header, 3-Pin")
      (fields (field (name "PUBLISHER") "Altium Limited"))
      (libsource (lib "Miscellaneous Connectors") (part "Header 3"))
    )
    (comp (ref "P24")
      (value "Header 3")
      (footprint "HDR1X3")
      (description "Header, 3-Pin")
      (fields (field (name "PUBLISHER") "Altium Limited"))
      (libsource (lib "Miscellaneous Connectors") (part "Header 3"))
    )
    (comp (ref "P25")
      (value "Header 10")
      (footprint "HDR110")
      (description "Header, 10-Pin")
      (fields (field (name "PUBLISHER") "Altium Limited"))
      (libsource (lib "Miscellaneous Connectors") (part "Header 10"))
    )
    (comp (ref "R1") (value "1.2K") (footprint "0805") (libsource (lib "*") (part "DZ")))
    (comp (ref "R2") (value "1.2K") (footprint "0805") (libsource (lib "*") (part "DZ")))
    (comp (ref "R3") (value "1.2K") (footprint "0805") (libsource (lib "*") (part "DZ")))
    (comp (ref "R4") (value "1.2K") (footprint "0805") (libsource (lib "*") (part "DZ")))
    (comp (ref "R5") (value "1.2K") (footprint "0805") (libsource (lib "*") (part "DZ")))
    (comp (ref "R6") (value "1.2K") (footprint "0805") (libsource (lib "*") (part "DZ")))
    (comp (ref "R7") (value "1.2K") (footprint "0805") (libsource (lib "*") (part "DZ")))
    (comp (ref "R8") (value "1.2K") (footprint "0805") (libsource (lib "*") (part "DZ")))
    (comp (ref "R9") (value "0805/4K3/5%") (footprint "0805") (libsource (lib "*") (part "RES2")))
    (comp (ref "R10") (value "0805/4K3/5%") (footprint "0805") (libsource (lib "*") (part "RES2")))
    (comp (ref "R11") (value "0805/4K3/5%") (footprint "0805") (libsource (lib "*") (part "RES2")))
    (comp (ref "R12") (value "0805/4K3/5%") (footprint "0805") (libsource (lib "*") (part "RES2")))
    (comp (ref "R13") (value "0805/4K3/5%") (footprint "0805") (libsource (lib "*") (part "RES2")))
    (comp (ref "R14") (value "0805/4K3/5%") (footprint "0805") (libsource (lib "*") (part "RES2")))
    (comp (ref "R15") (value "0805/4K3/5%") (footprint "0805") (libsource (lib "*") (part "RES2")))
    (comp (ref "R16") (value "0805/4K3/5%") (footprint "0805") (libsource (lib "*") (part "RES2")))
    (comp (ref "R17") (value "0805/4K3/5%") (footprint "0805") (libsource (lib "*") (part "RES2")))
    (comp (ref "R18") (value "0805/4K3/5%") (footprint "0805") (libsource (lib "*") (part "RES2")))
    (comp (ref "R19") (value "0805/4K3/5%") (footprint "0805") (libsource (lib "*") (part "RES2")))
    (comp (ref "R20") (value "0805/4K3/5%") (footprint "0805") (libsource (lib "*") (part "RES2")))
    (comp (ref "R21") (value "0805/4K3/5%") (footprint "0805") (libsource (lib "*") (part "RES2")))
    (comp (ref "R22") (value "0805/4K3/5%") (footprint "0805") (libsource (lib "*") (part "RES2")))
    (comp (ref "R23") (value "120R") (footprint "0805") (libsource (lib "*") (part "DZ")))
    (comp (ref "R24") (value "2K") (footprint "0805") (libsource (lib "*") (part "DZ")))
    (comp (ref "R25") (value "2K") (footprint "0805") (libsource (lib "*") (part "DZ")))
    (comp (ref "R26") (value "100R") (footprint "0805") (libsource (lib "*") (part "DZ")))
    (comp (ref "R27") (value "2R") (footprint "0805") (libsource (lib "*") (part "DZ")))
    (comp (ref "R28") (value "1K") (footprint "0805") (libsource (lib "*") (part "DZ")))
    (comp (ref "R29") (value "75") (footprint "0805") (libsource (lib "*") (part "DZ")))
    (comp (ref "R30") (value "75") (footprint "0805") (libsource (lib "*") (part "DZ")))
    (comp (ref "R31") (value "75") (footprint "0805") (libsource (lib "*") (part "DZ")))
    (comp (ref "R32") (value "10K") (footprint "0805") (libsource (lib "*") (part "DZ")))
    (comp (ref "R33") (value "50") (footprint "0805") (libsource (lib "*") (part "DZ")))
    (comp (ref "R34") (value "50") (footprint "0805") (libsource (lib "*") (part "DZ")))
    (comp (ref "R35") (value "2K") (footprint "0805") (libsource (lib "*") (part "DZ")))
    (comp (ref "R36") (value "2K") (footprint "0805") (libsource (lib "*") (part "DZ")))
    (comp (ref "R37") (value "2K") (footprint "0805") (libsource (lib "*") (part "DZ")))
    (comp (ref "R38") (value "2K") (footprint "0805") (libsource (lib "*") (part "DZ")))
    (comp (ref "R39") (value "2K") (footprint "0805") (libsource (lib "*") (part "DZ")))
    (comp (ref "R40") (value "1.2K") (footprint "0805") (libsource (lib "*") (part "DZ")))
    (comp (ref "R41") (value "0") (footprint "0805") (libsource (lib "*") (part "DZ")))
    (comp (ref "R42") (value "50") (footprint "0805") (libsource (lib "*") (part "DZ")))
    (comp (ref "R43") (value "50") (footprint "0805") (libsource (lib "*") (part "DZ")))
    (comp (ref "R44") (value "12K") (footprint "0805") (libsource (lib "*") (part "DZ")))
    (comp (ref "R45") (value "330") (footprint "0805") (libsource (lib "*") (part "DZ")))
    (comp (ref "R46") (value "330") (footprint "0805") (libsource (lib "*") (part "DZ")))
    (comp (ref "R47") (value "1.2K") (footprint "0805") (libsource (lib "*") (part "DZ")))
    (comp (ref "R89") (value "2K") (footprint "0805") (libsource (lib "*") (part "DZ")))
    (comp (ref "R90") (value "2K") (footprint "0805") (libsource (lib "*") (part "DZ")))
    (comp (ref "R110") (value "2K") (footprint "0805") (libsource (lib "*") (part "DZ")))
    (comp (ref "R111") (value "2K") (footprint "0805") (libsource (lib "*") (part "DZ")))
    (comp (ref "R127") (value "10K") (footprint "0805") (libsource (lib "*") (part "DZ")))
    (comp (ref "R128") (value "10K") (footprint "0805") (libsource (lib "*") (part "DZ")))
    (comp (ref "R129") (value "10K") (footprint "0805") (libsource (lib "*") (part "DZ")))
    (comp (ref "R130") (value "10K") (footprint "0805") (libsource (lib "*") (part "DZ")))
    (comp (ref "R174") (value "100R") (footprint "0805") (libsource (lib "*") (part "DZ")))
    (comp (ref "R175") (value "30K") (footprint "0805") (libsource (lib "*") (part "DZ")))
    (comp (ref "R176") (value "30K") (footprint "0805") (libsource (lib "*") (part "DZ")))
    (comp (ref "R177") (value "30K") (footprint "0805") (libsource (lib "*") (part "DZ")))
    (comp (ref "R178") (value "7.5K") (footprint "0805") (libsource (lib "*") (part "DZ")))
    (comp (ref "R179") (value "7.5K") (footprint "0805") (libsource (lib "*") (part "DZ")))
    (comp (ref "R180") (value "7.5K") (footprint "0805") (libsource (lib "*") (part "DZ")))
    (comp (ref "R181") (value "7.5K") (footprint "0805") (libsource (lib "*") (part "DZ")))
    (comp (ref "R183") (value "4.3K") (footprint "0805") (libsource (lib "*") (part "DZ")))
    (comp (ref "R184") (value "4.3K") (footprint "0805") (libsource (lib "*") (part "DZ")))
    (comp (ref "R185") (value "4.3K") (footprint "0805") (libsource (lib "*") (part "DZ")))
    (comp (ref "R186") (value "4.3K") (footprint "0805") (libsource (lib "*") (part "DZ")))
    (comp (ref "RL1") (value "5K") (footprint "0805") (libsource (lib "*") (part "DZ")))
    (comp (ref "RL2") (value "1K") (footprint "0805") (libsource (lib "*") (part "DZ")))
    (comp (ref "RL3") (value "1K") (footprint "0805") (libsource (lib "*") (part "DZ")))
    (comp (ref "RS232-1") (value "DB9") (footprint "DB-9RA/M") (libsource (lib "*") (part "DB9")))
    (comp (ref "RS232-2") (value "DB9") (footprint "DB-9RA/M") (libsource (lib "*") (part "DB9")))
    (comp (ref "TVS1") (value "SMBJ8.5CA") (footprint "7227") (libsource (lib "*") (part "BITVS")))
    (comp (ref "TVS2") (value "SMBJ8.5CA") (footprint "7227") (libsource (lib "*") (part "BITVS")))
    (comp (ref "U1")
      (value "AD7606BSTZ")
      (footprint "TQFP64")
      (description "AD7606")
      (libsource (lib "*") (part "AD7606"))
    )
    (comp (ref "U2")
      (value "AD7606BSTZ")
      (footprint "TQFP64")
      (description "AD7606")
      (libsource (lib "*") (part "AD7606"))
    )
    (comp (ref "U3") (value "74LVC4245APW") (footprint "TSOP-24") (libsource (lib "*") (part "74LVC4245A")))
    (comp (ref "U4") (value "74LVC4245APW") (footprint "TSOP-24") (libsource (lib "*") (part "74LVC4245A")))
    (comp (ref "U5") (value "ADR421ARZ") (footprint "SO-8") (libsource (lib "*") (part "ADR421ARZ")))
    (comp (ref "U6")
      (value "CH376S")
      (footprint "SOP28")
      (description "USB Host and SD card Host with File System & USB Device for MCU, parallel / SPI / UART Serial")
      (libsource (lib "*") (part "CH376S"))
    )
    (comp (ref "U7") (value "LM1117_1V8") (footprint "SOT-223") (libsource (lib "*") (part "LM1117_3.3V")))
    (comp (ref "U8") (value "MAX485") (footprint "so-8") (libsource (lib "*") (part "MAX485E")))
    (comp (ref "U9") (value "MAX3232CSE") (footprint "SO-16") (libsource (lib "*") (part "MAX232")))
    (comp (ref "U10") (value "SN65HV230") (footprint "SO-8") (libsource (lib "Sheet1") (part "SN65HVD230")))
    (comp (ref "U11") (value "TS6121C") (footprint "HR601680") (libsource (lib "*") (part "TS6121C")))
    (comp (ref "U12") (value "CH395L") (footprint "LQFP128") (libsource (lib "*") (part "CH395L")))
    (comp (ref "U13")
      (value "SN74CBT3384ADBLE")
      (footprint "3384")
      (description "10-Bit FET Bus Switch")
      (fields (field (name "PUBLISHER") "Altium Limited"))
      (libsource (lib "TI Logic Switch") (part "SN74CBT3384ADBLE"))
    )
    (comp (ref "U14")
      (value "NMA0515S")
      (footprint "MIP-6")
      (description "Isolated 1W Dual Output")
      (fields (field (name "PUBLISHER") "Altium Limited"))
      (libsource (lib "Newport Power Mgt DC-DC Converter") (part "NMA0515S"))
    )
    (comp (ref "U15")
      (value "LM1085IS-3.3")
      (footprint "TS3B_N")
      (description "3A Low Dropout Positive Regulators")
      (fields
        (field (name "MANUFACTURER") "National Semiconductor")
        (field (name "DIGIKEYPARTNUMBER") "LM1085IS-3.3-ND")
        (field (name "PUBLISHER") "Altium Limited")
      )
      (libsource (lib "NSC LDO") (part "LM1085IS-3.3"))
    )
    (comp (ref "U25") (value "AD5344BRU") (footprint "TSOP-28") (libsource (lib "*") (part "AD5344")))
    (comp (ref "U28") (value "XC95288XL") (footprint "QFP144") (libsource (lib "*") (part "XC95288_TQ144")))
    (comp (ref "U31") (value "LM258") (footprint "SO-8") (libsource (lib "*") (part "LF412")))
    (comp (ref "U31B") (value "LM258") (footprint "SO-8") (libsource (lib "*") (part "LF412")))
    (comp (ref "U33") (value "LM258") (footprint "SO-8") (libsource (lib "*") (part "LF412")))
    (comp (ref "U33B") (value "LM258") (footprint "SO-8") (libsource (lib "*") (part "LF412")))
    (comp (ref "X1")
      (value "12MHz")
      (footprint "XTAL40/24")
      (libsource (lib "*") (part "Pro7B.tmp_12MHz_19"))
    )
    (comp (ref "X2")
      (value "12MHz")
      (footprint "XTAL40/24")
      (libsource (lib "*") (part "Pro7B.tmp_12MHz_19"))
    )
  )
  (nets
    (net (code "1") (name "+5") (class "Default")
      (node (ref "C41") (pin "1") (pinfunction "1_1") (pintype "passive"))
      (node (ref "C42") (pin "1") (pintype "passive"))
      (node (ref "C47") (pin "1") (pintype "passive"))
      (node (ref "C56") (pin "1") (pinfunction "1_1") (pintype "passive"))
      (node (ref "C57") (pin "1") (pintype "passive"))
      (node (ref "C63") (pin "1") (pinfunction "1_1") (pintype "passive"))
      (node (ref "C64") (pin "1") (pinfunction "1_1") (pintype "passive"))
      (node (ref "C65") (pin "1") (pintype "passive"))
      (node (ref "C66") (pin "1") (pintype "passive"))
      (node (ref "C67") (pin "1") (pintype "passive"))
      (node (ref "C68") (pin "1") (pintype "passive"))
      (node (ref "C69") (pin "1") (pintype "passive"))
      (node (ref "C70") (pin "1") (pintype "passive"))
      (node (ref "C71") (pin "1") (pintype "passive"))
      (node (ref "C72") (pin "1") (pintype "passive"))
      (node (ref "C73") (pin "1") (pintype "passive"))
      (node (ref "C74") (pin "1") (pintype "passive"))
      (node (ref "C75") (pin "1") (pintype "passive"))
      (node (ref "C76") (pin "1") (pinfunction "1_1") (pintype "passive"))
      (node (ref "C77") (pin "1") (pinfunction "1_1") (pintype "passive"))
      (node (ref "C78") (pin "1") (pinfunction "1_1") (pintype "passive"))
      (node (ref "C79") (pin "1") (pinfunction "1_1") (pintype "passive"))
      (node (ref "D9") (pin "1") (pintype "passive"))
      (node (ref "L1") (pin "1") (pinfunction "1_1") (pintype "passive"))
      (node (ref "L24.7uH") (pin "1") (pinfunction "1_1") (pintype "passive"))
      (node (ref "P25") (pin "4") (pinfunction "4_4") (pintype "passive"))
      (node (ref "P25") (pin "5") (pinfunction "5_5") (pintype "passive"))
      (node (ref "P25") (pin "6") (pinfunction "6_6") (pintype "passive"))
      (node (ref "R24") (pin "1") (pintype "passive"))
      (node (ref "R25") (pin "1") (pintype "passive"))
      (node (ref "R27") (pin "2") (pintype "passive"))
      (node (ref "R37") (pin "1") (pintype "passive"))
      (node (ref "R38") (pin "1") (pintype "passive"))
      (node (ref "RL1") (pin "1") (pintype "passive"))
      (node (ref "RL3") (pin "1") (pintype "passive"))
      (node (ref "U13") (pin "24") (pinfunction "VDD_24") (pintype "power_in"))
      (node (ref "U15") (pin "3") (pinfunction "IN_3") (pintype "power_in"))
      (node (ref "U3") (pin "1") (pinfunction "VCCA_1") (pintype "passive"))
      (node (ref "U4") (pin "1") (pinfunction "VCCA_1") (pintype "passive"))
    )
    (net (code "2") (name "-VCC") (class "Default")
      (node (ref "C129") (pin "1") (pintype "passive"))
      (node (ref "U14") (pin "4") (pinfunction "-V_4") (pintype "output"))
    )
    (net (code "3") (name "/485+") (class "Default")
      (node (ref "1") (pin "1") (pinfunction "1_1") (pintype "passive"))
      (node (ref "B1") (pin "2") (pinfunction "2_2") (pintype "passive"))
    )
    (net (code "4") (name "/485-") (class "Default")
      (node (ref "1") (pin "2") (pinfunction "2_2") (pintype "passive"))
      (node (ref "B2") (pin "2") (pinfunction "2_2") (pintype "passive"))
    )
    (net (code "5") (name "/485-EN") (class "Default")
      (node (ref "P10") (pin "2") (pinfunction "2_2") (pintype "passive"))
      (node (ref "U28") (pin "110") (pinfunction "110_110") (pintype "passive"))
    )
    (net (code "6") (name "/485EN") (class "Default")
      (node (ref "P15") (pin "3") (pinfunction "3_3") (pintype "passive"))
      (node (ref "U28") (pin "34") (pinfunction "34_34") (pintype "passive"))
    )
    (net (code "7") (name "/A") (class "Default") (node (ref "U12") (pin "111") (pintype "passive")))
    (net (code "8") (name "/A0") (class "Default")
      (node (ref "CAP3") (pin "17") (pinfunction "17_17") (pintype "passive"))
      (node (ref "EXTBUS") (pin "22") (pinfunction "22_22") (pintype "passive"))
      (node (ref "J2") (pin "7") (pinfunction "7_7") (pintype "passive"))
      (node (ref "U25") (pin "12") (pinfunction "A0_12") (pintype "passive"))
    )
    (net (code "9") (name "/A1") (class "Default")
      (node (ref "CAP3") (pin "18") (pinfunction "18_18") (pintype "passive"))
      (node (ref "EXTBUS") (pin "21") (pinfunction "21_21") (pintype "passive"))
      (node (ref "U25") (pin "13") (pinfunction "A1_13") (pintype "passive"))
    )
    (net (code "10") (name "/A2") (class "Default")
      (node (ref "CAP3") (pin "19") (pinfunction "19_19") (pintype "passive"))
      (node (ref "EXTBUS") (pin "20") (pinfunction "20_20") (pintype "passive"))
    )
    (net (code "11") (name "/A3") (class "Default")
      (node (ref "CAP3") (pin "20") (pinfunction "20_20") (pintype "passive"))
      (node (ref "EXTBUS") (pin "19") (pinfunction "19_19") (pintype "passive"))
    )
    (net (code "12") (name "/A4") (class "Default")
      (node (ref "CAP3") (pin "21") (pinfunction "21_21") (pintype "passive"))
      (node (ref "EXTBUS") (pin "18") (pinfunction "18_18") (pintype "passive"))
    )
    (net (code "13") (name "/A5") (class "Default")
      (node (ref "CAP3") (pin "22") (pinfunction "22_22") (pintype "passive"))
      (node (ref "EXTBUS") (pin "17") (pinfunction "17_17") (pintype "passive"))
    )
    (net (code "14") (name "/A6") (class "Default")
      (node (ref "CAP3") (pin "23") (pinfunction "23_23") (pintype "passive"))
      (node (ref "EXTBUS") (pin "16") (pinfunction "16_16") (pintype "passive"))
    )
    (net (code "15") (name "/A7") (class "Default")
      (node (ref "CAP3") (pin "24") (pinfunction "24_24") (pintype "passive"))
      (node (ref "EXTBUS") (pin "15") (pinfunction "15_15") (pintype "passive"))
    )
    (net (code "16") (name "/A8") (class "Default")
      (node (ref "CAP3") (pin "25") (pinfunction "25_25") (pintype "passive"))
      (node (ref "EXTBUS") (pin "14") (pinfunction "14_14") (pintype "passive"))
    )
    (net (code "17") (name "/A9") (class "Default")
      (node (ref "CAP3") (pin "26") (pinfunction "26_26") (pintype "passive"))
      (node (ref "EXTBUS") (pin "13") (pinfunction "13_13") (pintype "passive"))
    )
    (net (code "18") (name "/A10") (class "Default")
      (node (ref "CAP3") (pin "27") (pinfunction "27_27") (pintype "passive"))
      (node (ref "EXTBUS") (pin "12") (pinfunction "12_12") (pintype "passive"))
    )
    (net (code "19") (name "/A11") (class "Default")
      (node (ref "CAP3") (pin "28") (pinfunction "28_28") (pintype "passive"))
      (node (ref "EXTBUS") (pin "11") (pinfunction "11_11") (pintype "passive"))
    )
    (net (code "20") (name "/A12") (class "Default")
      (node (ref "CAP3") (pin "29") (pinfunction "29_29") (pintype "passive"))
      (node (ref "EXTBUS") (pin "10") (pinfunction "10_10") (pintype "passive"))
    )
    (net (code "21") (name "/A13") (class "Default")
      (node (ref "CAP3") (pin "30") (pinfunction "30_30") (pintype "passive"))
      (node (ref "EXTBUS") (pin "9") (pinfunction "9_9") (pintype "passive"))
    )
    (net (code "22") (name "/A14") (class "Default")
      (node (ref "CAP3") (pin "31") (pinfunction "31_31") (pintype "passive"))
      (node (ref "EXTBUS") (pin "8") (pinfunction "8_8") (pintype "passive"))
    )
    (net (code "23") (name "/A15") (class "Default")
      (node (ref "CAP3") (pin "32") (pinfunction "32_32") (pintype "passive"))
      (node (ref "EXTBUS") (pin "7") (pinfunction "7_7") (pintype "passive"))
    )
    (net (code "24") (name "/A16") (class "Default")
      (node (ref "CAP3") (pin "33") (pinfunction "33_33") (pintype "passive"))
      (node (ref "EXTBUS") (pin "6") (pinfunction "6_6") (pintype "passive"))
      (node (ref "U28") (pin "77") (pinfunction "77_77") (pintype "passive"))
    )
    (net (code "25") (name "/A17") (class "Default")
      (node (ref "CAP3") (pin "34") (pinfunction "34_34") (pintype "passive"))
      (node (ref "EXTBUS") (pin "5") (pinfunction "5_5") (pintype "passive"))
      (node (ref "U28") (pin "76") (pinfunction "76_76") (pintype "passive"))
    )
    (net (code "26") (name "/A18") (class "Default")
      (node (ref "CAP3") (pin "35") (pinfunction "35_35") (pintype "passive"))
      (node (ref "EXTBUS") (pin "4") (pinfunction "4_4") (pintype "passive"))
      (node (ref "U28") (pin "75") (pinfunction "75_75") (pintype "passive"))
    )
    (net (code "27") (name "/A19") (class "Default")
      (node (ref "CAP3") (pin "36") (pinfunction "36_36") (pintype "passive"))
      (node (ref "EXTBUS") (pin "3") (pinfunction "3_3") (pintype "passive"))
      (node (ref "U28") (pin "74") (pinfunction "74_74") (pintype "passive"))
    )
    (net (code "28") (name "/ACT#") (class "Default")
      (node (ref "LED1") (pin "2") (pintype "passive"))
      (node (ref "U6") (pin "24") (pinfunction "ACT#_24") (pintype "output"))
    )
    (net (code "29") (name "/AD-CON") (class "Default")
      (node (ref "U1") (pin "10") (pinfunction "CONVSTB_10") (pintype "passive"))
      (node (ref "U1") (pin "9") (pinfunction "CONVSTA_9") (pintype "passive"))
      (node (ref "U2") (pin "10") (pinfunction "CONVSTB_10") (pintype "passive"))
      (node (ref "U2") (pin "9") (pinfunction "CONVSTA_9") (pintype "passive"))
      (node (ref "U28") (pin "79") (pinfunction "79_79") (pintype "passive"))
    )
    (net (code "30") (name "/AD1_BUSY") (class "Default")
      (node (ref "U1") (pin "14") (pinfunction "BUSY_14") (pintype "passive"))
      (node (ref "U28") (pin "49") (pinfunction "49_49") (pintype "passive"))
    )
    (net (code "31") (name "/AD1_OS0") (class "Default")
      (node (ref "R22") (pin "2") (pinfunction "2_2") (pintype "passive"))
      (node (ref "U1") (pin "3") (pinfunction "OS0_3") (pintype "passive"))
    )
    (net (code "32") (name "/AD1_OS1") (class "Default")
      (node (ref "R20") (pin "2") (pinfunction "2_2") (pintype "passive"))
      (node (ref "U1") (pin "4") (pinfunction "OS1_4") (pintype "passive"))
    )
    (net (code "33") (name "/AD1_OS2") (class "Default")
      (node (ref "R18") (pin "2") (pinfunction "2_2") (pintype "passive"))
      (node (ref "U1") (pin "5") (pinfunction "OS2_5") (pintype "passive"))
    )
    (net (code "34") (name "/AD1_RANGE") (class "Default")
      (node (ref "R11") (pin "2") (pinfunction "2_2") (pintype "passive"))
      (node (ref "U1") (pin "8") (pinfunction "RANGE_8") (pintype "passive"))
    )
    (net (code "35") (name "/AD1_REFCAP") (class "Default")
      (node (ref "C12") (pin "1") (pinfunction "1_1") (pintype "passive"))
      (node (ref "C13") (pin "1") (pintype "passive"))
      (node (ref "U1") (pin "44") (pinfunction "REFCAPA_44") (pintype "passive"))
      (node (ref "U1") (pin "45") (pinfunction "REFCAPB_45") (pintype "passive"))
    )
    (net (code "36") (name "/AD1_REFSEL") (class "Default")
      (node (ref "R14") (pin "2") (pinfunction "2_2") (pintype "passive"))
      (node (ref "U1") (pin "34") (pinfunction "REFSEL_34") (pintype "passive"))
    )
    (net (code "37") (name "/AD1_SERPAR_SEL") (class "Default")
      (node (ref "R12") (pin "2") (pinfunction "2_2") (pintype "passive"))
      (node (ref "U1") (pin "6") (pinfunction "SER/~{PAR}_SEL_6") (pintype "passive"))
    )
    (net (code "38") (name "/AD1_STBY") (class "Default")
      (node (ref "R16") (pin "2") (pinfunction "2_2") (pintype "passive"))
      (node (ref "U1") (pin "7") (pinfunction "~{STBY}_7") (pintype "passive"))
    )
    (net (code "39") (name "/AD2_BUSY") (class "Default")
      (node (ref "U2") (pin "14") (pinfunction "BUSY_14") (pintype "passive"))
      (node (ref "U28") (pin "35") (pinfunction "35_35") (pintype "passive"))
    )
    (net (code "40") (name "/AD2_OS0") (class "Default")
      (node (ref "R21") (pin "2") (pinfunction "2_2") (pintype "passive"))
      (node (ref "U2") (pin "3") (pinfunction "OS0_3") (pintype "passive"))
    )
    (net (code "41") (name "/AD2_OS1") (class "Default")
      (node (ref "R19") (pin "2") (pinfunction "2_2") (pintype "passive"))
      (node (ref "U2") (pin "4") (pinfunction "OS1_4") (pintype "passive"))
    )
    (net (code "42") (name "/AD2_OS2") (class "Default")
      (node (ref "R17") (pin "2") (pinfunction "2_2") (pintype "passive"))
      (node (ref "U2") (pin "5") (pinfunction "OS2_5") (pintype "passive"))
    )
    (net (code "43") (name "/AD2_RANGE") (class "Default")
      (node (ref "R9") (pin "2") (pinfunction "2_2") (pintype "passive"))
      (node (ref "U2") (pin "8") (pinfunction "RANGE_8") (pintype "passive"))
    )
    (net (code "44") (name "/AD2_REFCAP") (class "Default")
      (node (ref "C10") (pin "1") (pintype "passive"))
      (node (ref "C9") (pin "1") (pinfunction "1_1") (pintype "passive"))
      (node (ref "U2") (pin "44") (pinfunction "REFCAPA_44") (pintype "passive"))
      (node (ref "U2") (pin "45") (pinfunction "REFCAPB_45") (pintype "passive"))
    )
    (net (code "45") (name "/AD2_REFSEL") (class "Default")
      (node (ref "R13") (pin "2") (pinfunction "2_2") (pintype "passive"))
      (node (ref "U2") (pin "34") (pinfunction "REFSEL_34") (pintype "passive"))
    )
    (net (code "46") (name "/AD2_SERPAR_SEL") (class "Default")
      (node (ref "R10") (pin "2") (pinfunction "2_2") (pintype "passive"))
      (node (ref "U2") (pin "6") (pinfunction "SER/~{PAR}_SEL_6") (pintype "passive"))
    )
    (net (code "47") (name "/AD2_STBY") (class "Default")
      (node (ref "R15") (pin "2") (pinfunction "2_2") (pintype "passive"))
      (node (ref "U2") (pin "7") (pinfunction "~{STBY}_7") (pintype "passive"))
    )
    (net (code "48") (name "/ADA0") (class "Default")
      (node (ref "CAP3") (pin "61") (pinfunction "61_61") (pintype "passive"))
      (node (ref "J1") (pin "1") (pinfunction "1_1") (pintype "passive"))
    )
    (net (code "49") (name "/ADA1") (class "Default")
      (node (ref "CAP3") (pin "62") (pinfunction "62_62") (pintype "passive"))
      (node (ref "J1") (pin "13") (pinfunction "13_13") (pintype "passive"))
    )
    (net (code "50") (name "/ADA2") (class "Default")
      (node (ref "CAP3") (pin "63") (pinfunction "63_63") (pintype "passive"))
      (node (ref "J1") (pin "2") (pinfunction "2_2") (pintype "passive"))
    )
    (net (code "51") (name "/ADA3") (class "Default")
      (node (ref "CAP3") (pin "64") (pinfunction "64_64") (pintype "passive"))
      (node (ref "J1") (pin "14") (pinfunction "14_14") (pintype "passive"))
    )
    (net (code "52") (name "/ADA4") (class "Default")
      (node (ref "CAP3") (pin "65") (pinfunction "65_65") (pintype "passive"))
      (node (ref "J1") (pin "3") (pinfunction "3_3") (pintype "passive"))
    )
    (net (code "53") (name "/ADA5") (class "Default")
      (node (ref "CAP3") (pin "66") (pinfunction "66_66") (pintype "passive"))
      (node (ref "J1") (pin "15") (pinfunction "15_15") (pintype "passive"))
    )
    (net (code "54") (name "/ADA6") (class "Default")
      (node (ref "CAP3") (pin "67") (pinfunction "67_67") (pintype "passive"))
      (node (ref "J1") (pin "4") (pinfunction "4_4") (pintype "passive"))
    )
    (net (code "55") (name "/ADA7") (class "Default")
      (node (ref "CAP3") (pin "68") (pinfunction "68_68") (pintype "passive"))
      (node (ref "J1") (pin "16") (pinfunction "16_16") (pintype "passive"))
    )
    (net (code "56") (name "/ADB0") (class "Default")
      (node (ref "CAP3") (pin "69") (pinfunction "69_69") (pintype "passive"))
      (node (ref "J1") (pin "5") (pinfunction "5_5") (pintype "passive"))
    )
    (net (code "57") (name "/ADB1") (class "Default")
      (node (ref "CAP3") (pin "70") (pinfunction "70_70") (pintype "passive"))
      (node (ref "J1") (pin "17") (pinfunction "17_17") (pintype "passive"))
    )
    (net (code "58") (name "/ADB2") (class "Default")
      (node (ref "CAP3") (pin "71") (pinfunction "71_71") (pintype "passive"))
      (node (ref "J1") (pin "6") (pinfunction "6_6") (pintype "passive"))
    )
    (net (code "59") (name "/ADB3") (class "Default")
      (node (ref "CAP3") (pin "72") (pinfunction "72_72") (pintype "passive"))
      (node (ref "J1") (pin "18") (pinfunction "18_18") (pintype "passive"))
    )
    (net (code "60") (name "/ADB4") (class "Default")
      (node (ref "CAP3") (pin "73") (pinfunction "73_73") (pintype "passive"))
      (node (ref "J1") (pin "7") (pinfunction "7_7") (pintype "passive"))
    )
    (net (code "61") (name "/ADB5") (class "Default")
      (node (ref "CAP3") (pin "74") (pinfunction "74_74") (pintype "passive"))
      (node (ref "J1") (pin "19") (pinfunction "19_19") (pintype "passive"))
    )
    (net (code "62") (name "/ADB6") (class "Default")
      (node (ref "CAP3") (pin "75") (pinfunction "75_75") (pintype "passive"))
      (node (ref "J1") (pin "8") (pinfunction "8_8") (pintype "passive"))
    )
    (net (code "63") (name "/ADB7") (class "Default")
      (node (ref "CAP3") (pin "76") (pinfunction "76_76") (pintype "passive"))
      (node (ref "J1") (pin "20") (pinfunction "20_20") (pintype "passive"))
    )
    (net (code "64") (name "/ADBUSY") (class "Default")
      (node (ref "P16") (pin "3") (pinfunction "3_3") (pintype "passive"))
      (node (ref "U28") (pin "66") (pinfunction "66_66") (pintype "passive"))
    )
    (net (code "65") (name "/ADCON") (class "Default")
      (node (ref "P17") (pin "3") (pinfunction "3_3") (pintype "passive"))
      (node (ref "U28") (pin "92") (pinfunction "92_92") (pintype "passive"))
    )
    (net (code "66") (name "/ADINA0") (class "Default")
      (node (ref "J5") (pin "26") (pinfunction "26_26") (pintype "passive"))
      (node (ref "U1") (pin "49") (pinfunction "V1_49") (pintype "passive"))
    )
    (net (code "67") (name "/ADINA1") (class "Default")
      (node (ref "J5") (pin "25") (pinfunction "25_25") (pintype "passive"))
      (node (ref "U1") (pin "51") (pinfunction "V2_51") (pintype "passive"))
    )
    (net (code "68") (name "/ADINA2") (class "Default")
      (node (ref "J5") (pin "24") (pinfunction "24_24") (pintype "passive"))
      (node (ref "U1") (pin "53") (pinfunction "V3_53") (pintype "passive"))
    )
    (net (code "69") (name "/ADINA3") (class "Default")
      (node (ref "J5") (pin "23") (pinfunction "23_23") (pintype "passive"))
      (node (ref "U1") (pin "55") (pinfunction "V4_55") (pintype "passive"))
    )
    (net (code "70") (name "/ADINA4") (class "Default")
      (node (ref "J5") (pin "22") (pinfunction "22_22") (pintype "passive"))
      (node (ref "U1") (pin "57") (pinfunction "V5_57") (pintype "passive"))
    )
    (net (code "71") (name "/ADINA5") (class "Default")
      (node (ref "J5") (pin "21") (pinfunction "21_21") (pintype "passive"))
      (node (ref "U1") (pin "59") (pinfunction "V6_59") (pintype "passive"))
    )
    (net (code "72") (name "/ADINA6") (class "Default")
      (node (ref "J5") (pin "20") (pinfunction "20_20") (pintype "passive"))
      (node (ref "U1") (pin "61") (pinfunction "V7_61") (pintype "passive"))
    )
    (net (code "73") (name "/ADINA7") (class "Default")
      (node (ref "J5") (pin "19") (pinfunction "19_19") (pintype "passive"))
      (node (ref "U1") (pin "63") (pinfunction "V8_63") (pintype "passive"))
    )
    (net (code "74") (name "/ADINB0") (class "Default")
      (node (ref "J6") (pin "26") (pinfunction "26_26") (pintype "passive"))
      (node (ref "U2") (pin "49") (pinfunction "V1_49") (pintype "passive"))
    )
    (net (code "75") (name "/ADINB1") (class "Default")
      (node (ref "J6") (pin "25") (pinfunction "25_25") (pintype "passive"))
      (node (ref "U2") (pin "51") (pinfunction "V2_51") (pintype "passive"))
    )
    (net (code "76") (name "/ADINB2") (class "Default")
      (node (ref "J6") (pin "24") (pinfunction "24_24") (pintype "passive"))
      (node (ref "U2") (pin "53") (pinfunction "V3_53") (pintype "passive"))
    )
    (net (code "77") (name "/ADINB3") (class "Default")
      (node (ref "J6") (pin "23") (pinfunction "23_23") (pintype "passive"))
      (node (ref "U2") (pin "55") (pinfunction "V4_55") (pintype "passive"))
    )
    (net (code "78") (name "/ADINB4") (class "Default")
      (node (ref "J6") (pin "22") (pinfunction "22_22") (pintype "passive"))
      (node (ref "U2") (pin "57") (pinfunction "V5_57") (pintype "passive"))
    )
    (net (code "79") (name "/ADINB5") (class "Default")
      (node (ref "J6") (pin "21") (pinfunction "21_21") (pintype "passive"))
      (node (ref "U2") (pin "59") (pinfunction "V6_59") (pintype "passive"))
    )
    (net (code "80") (name "/ADINB6") (class "Default")
      (node (ref "J6") (pin "20") (pinfunction "20_20") (pintype "passive"))
      (node (ref "U2") (pin "61") (pinfunction "V7_61") (pintype "passive"))
    )
    (net (code "81") (name "/ADINB7") (class "Default")
      (node (ref "J6") (pin "19") (pinfunction "19_19") (pintype "passive"))
      (node (ref "U2") (pin "63") (pinfunction "V8_63") (pintype "passive"))
    )
    (net (code "82") (name "/ADLO") (class "Default")
      (node (ref "J5") (pin "17") (pinfunction "17_17") (pintype "passive"))
      (node (ref "J5") (pin "18") (pinfunction "18_18") (pintype "passive"))
      (node (ref "J6") (pin "17") (pinfunction "17_17") (pintype "passive"))
      (node (ref "J6") (pin "18") (pinfunction "18_18") (pintype "passive"))
      (node (ref "R41") (pin "2") (pintype "passive"))
    )
    (net (code "83") (name "/ADR421_VOUT") (class "Default")
      (node (ref "C1") (pin "1") (pinfunction "1_1") (pintype "passive"))
      (node (ref "C11") (pin "1") (pinfunction "1_1") (pintype "passive"))
      (node (ref "C117") (pin "1") (pintype "passive"))
      (node (ref "C118") (pin "1") (pinfunction "1_1") (pintype "passive"))
      (node (ref "C14") (pin "1") (pintype "passive"))
      (node (ref "C2") (pin "1") (pintype "passive"))
      (node (ref "C5") (pin "1") (pintype "passive"))
      (node (ref "C6") (pin "1") (pintype "passive"))
      (node (ref "C7") (pin "1") (pintype "passive"))
      (node (ref "C8") (pin "1") (pinfunction "1_1") (pintype "passive"))
      (node (ref "R178") (pin "2") (pintype "passive"))
      (node (ref "R179") (pin "2") (pintype "passive"))
      (node (ref "R180") (pin "2") (pintype "passive"))
      (node (ref "R181") (pin "2") (pintype "passive"))
      (node (ref "U1") (pin "42") (pinfunction "REFIN/REFOUT_42") (pintype "passive"))
      (node (ref "U2") (pin "42") (pinfunction "REFIN/REFOUT_42") (pintype "passive"))
      (node (ref "U25") (pin "1") (pinfunction "VREFD_1") (pintype "passive"))
      (node (ref "U25") (pin "2") (pinfunction "VREFC_2") (pintype "passive"))
      (node (ref "U25") (pin "3") (pinfunction "VREFB_3") (pintype "passive"))
      (node (ref "U25") (pin "4") (pinfunction "VREFA_4") (pintype "passive"))
      (node (ref "U5") (pin "6") (pinfunction "VOUT_6") (pintype "output"))
    )
    (net (code "84") (name "/ADRES") (class "Default")
      (node (ref "U1") (pin "11") (pinfunction "RESET_11") (pintype "passive"))
      (node (ref "U2") (pin "11") (pinfunction "RESET_11") (pintype "passive"))
      (node (ref "U28") (pin "52") (pinfunction "52_52") (pintype "passive"))
    )
    (net (code "85") (name "/AGND") (class "Default")
      (node (ref "CAP3") (pin "77") (pinfunction "77_77") (pintype "passive"))
      (node (ref "CAP3") (pin "78") (pinfunction "78_78") (pintype "passive"))
      (node (ref "J1") (pin "10") (pinfunction "10_10") (pintype "passive"))
      (node (ref "J1") (pin "11") (pinfunction "11_11") (pintype "passive"))
      (node (ref "J1") (pin "12") (pinfunction "12_12") (pintype "passive"))
      (node (ref "J1") (pin "21") (pinfunction "21_21") (pintype "passive"))
      (node (ref "J1") (pin "22") (pinfunction "22_22") (pintype "passive"))
      (node (ref "J1") (pin "23") (pinfunction "23_23") (pintype "passive"))
      (node (ref "J1") (pin "24") (pinfunction "24_24") (pintype "passive"))
      (node (ref "J1") (pin "9") (pinfunction "9_9") (pintype "passive"))
      (node (ref "J5") (pin "16") (pinfunction "16_16") (pintype "passive"))
      (node (ref "J6") (pin "16") (pinfunction "16_16") (pintype "passive"))
      (node (ref "R41") (pin "1") (pintype "passive"))
    )
    (net (code "86") (name "/APWM1") (class "Default")
      (node (ref "J5") (pin "7") (pinfunction "7_7") (pintype "passive"))
      (node (ref "R7") (pin "1") (pintype "passive"))
      (node (ref "U3") (pin "9") (pinfunction "A7_9") (pintype "passive"))
    )
    (net (code "87") (name "/APWM2") (class "Default")
      (node (ref "J5") (pin "8") (pinfunction "8_8") (pintype "passive"))
      (node (ref "R8") (pin "1") (pintype "passive"))
      (node (ref "U3") (pin "10") (pinfunction "A8_10") (pintype "passive"))
    )
    (net (code "88") (name "/APWM3") (class "Default")
      (node (ref "J5") (pin "9") (pinfunction "9_9") (pintype "passive"))
      (node (ref "U4") (pin "9") (pinfunction "A7_9") (pintype "passive"))
    )
    (net (code "89") (name "/APWM4") (class "Default")
      (node (ref "J6") (pin "7") (pinfunction "7_7") (pintype "passive"))
      (node (ref "U4") (pin "10") (pinfunction "A8_10") (pintype "passive"))
    )
    (net (code "90") (name "/B") (class "Default") (node (ref "U12") (pin "110") (pintype "passive")))
    (net (code "91") (name "/CANH") (class "Default")
      (node (ref "CAN1") (pin "2") (pinfunction "2_2") (pintype "passive"))
      (node (ref "R26") (pin "2") (pintype "passive"))
      (node (ref "U10") (pin "7") (pinfunction "CANH_7") (pintype "passive"))
    )
    (net (code "92") (name "/CANI") (class "Default")
      (node (ref "CAN1") (pin "1") (pinfunction "1_1") (pintype "passive"))
      (node (ref "R26") (pin "1") (pintype "passive"))
      (node (ref "U10") (pin "6") (pinfunction "CANL_6") (pintype "passive"))
    )
    (net (code "93") (name "/CANRXB") (class "Default")
      (node (ref "U10") (pin "4") (pinfunction "R_4") (pintype "passive"))
    )
    (net (code "94") (name "/CANTXB") (class "Default")
      (node (ref "U10") (pin "1") (pinfunction "D_1") (pintype "passive"))
    )
    (net (code "95") (name "/CAP1") (class "Default")
      (node (ref "CAP3") (pin "93") (pinfunction "93_93") (pintype "passive"))
      (node (ref "U28") (pin "16") (pinfunction "16_16") (pintype "passive"))
    )
    (net (code "96") (name "/CAP2") (class "Default")
      (node (ref "CAP3") (pin "94") (pinfunction "94_94") (pintype "passive"))
      (node (ref "U28") (pin "15") (pinfunction "15_15") (pintype "passive"))
    )
    (net (code "97") (name "/CAP3") (class "Default")
      (node (ref "CAP3") (pin "95") (pinfunction "95_95") (pintype "passive"))
      (node (ref "U28") (pin "14") (pinfunction "14_14") (pintype "passive"))
    )
    (net (code "98") (name "/CAP4") (class "Default")
      (node (ref "CAP3") (pin "96") (pinfunction "96_96") (pintype "passive"))
      (node (ref "U28") (pin "13") (pinfunction "13_13") (pintype "passive"))
    )
    (net (code "99") (name "/CAP5") (class "Default")
      (node (ref "U28") (pin "95") (pinfunction "95_95") (pintype "passive"))
    )
    (net (code "100") (name "/CAP6") (class "Default")
      (node (ref "U28") (pin "61") (pinfunction "61_61") (pintype "passive"))
    )
    (net (code "101") (name "/CE0") (class "Default")
      (node (ref "EXTBUS") (pin "50") (pinfunction "50_50") (pintype "passive"))
      (node (ref "U28") (pin "107") (pinfunction "107_107") (pintype "passive"))
    )
    (net (code "102") (name "/CE1") (class "Default")
      (node (ref "EXTBUS") (pin "49") (pinfunction "49_49") (pintype "passive"))
      (node (ref "U28") (pin "106") (pinfunction "106_106") (pintype "passive"))
    )
    (net (code "103") (name "/CE2") (class "Default")
      (node (ref "EXTBUS") (pin "48") (pinfunction "48_48") (pintype "passive"))
      (node (ref "U28") (pin "105") (pinfunction "105_105") (pintype "passive"))
    )
    (net (code "104") (name "/CE3") (class "Default")
      (node (ref "EXTBUS") (pin "47") (pinfunction "47_47") (pintype "passive"))
      (node (ref "U28") (pin "104") (pinfunction "104_104") (pintype "passive"))
    )
    (net (code "105") (name "/C_TCK") (class "Default")
      (node (ref "P9") (pin "4") (pinfunction "4_4") (pintype "passive"))
      (node (ref "U28") (pin "67") (pinfunction "TCK_67") (pintype "passive"))
    )
    (net (code "106") (name "/C_TDI") (class "Default")
      (node (ref "P9") (pin "7") (pinfunction "7_7") (pintype "passive"))
      (node (ref "U28") (pin "63") (pinfunction "TDI_63") (pintype "passive"))
    )
    (net (code "107") (name "/C_TDO") (class "Default")
      (node (ref "P9") (pin "6") (pinfunction "6_6") (pintype "passive"))
      (node (ref "U28") (pin "122") (pinfunction "TDO_122") (pintype "passive"))
    )
    (net (code "108") (name "/C_TMS") (class "Default")
      (node (ref "P9") (pin "9") (pinfunction "9_9") (pintype "passive"))
      (node (ref "U28") (pin "65") (pinfunction "TMS_65") (pintype "passive"))
    )
    (net (code "109") (name "/D0") (class "Default")
      (node (ref "CAP3") (pin "1") (pinfunction "1_1") (pintype "passive"))
      (node (ref "EXTBUS") (pin "40") (pinfunction "40_40") (pintype "passive"))
      (node (ref "J2") (pin "2") (pinfunction "2_2") (pintype "passive"))
      (node (ref "U1") (pin "16") (pinfunction "DB0_16") (pintype "passive"))
      (node (ref "U2") (pin "16") (pinfunction "DB0_16") (pintype "passive"))
      (node (ref "U25") (pin "17") (pinfunction "D0_17") (pintype "passive"))
      (node (ref "U28") (pin "46") (pinfunction "46_46") (pintype "passive"))
    )
    (net (code "110") (name "/D1") (class "Default")
      (node (ref "CAP3") (pin "2") (pinfunction "2_2") (pintype "passive"))
      (node (ref "EXTBUS") (pin "39") (pinfunction "39_39") (pintype "passive"))
      (node (ref "J2") (pin "4") (pinfunction "4_4") (pintype "passive"))
      (node (ref "U1") (pin "17") (pinfunction "DB1_17") (pintype "passive"))
      (node (ref "U2") (pin "17") (pinfunction "DB1_17") (pintype "passive"))
      (node (ref "U25") (pin "18") (pinfunction "D1_18") (pintype "passive"))
      (node (ref "U28") (pin "45") (pinfunction "45_45") (pintype "passive"))
    )
    (net (code "111") (name "/D2") (class "Default")
      (node (ref "CAP3") (pin "3") (pinfunction "3_3") (pintype "passive"))
      (node (ref "EXTBUS") (pin "38") (pinfunction "38_38") (pintype "passive"))
      (node (ref "J2") (pin "6") (pinfunction "6_6") (pintype "passive"))
      (node (ref "U1") (pin "18") (pinfunction "DB2_18") (pintype "passive"))
      (node (ref "U2") (pin "18") (pinfunction "DB2_18") (pintype "passive"))
      (node (ref "U25") (pin "19") (pinfunction "D2_19") (pintype "passive"))
      (node (ref "U28") (pin "44") (pinfunction "44_44") (pintype "passive"))
    )
    (net (code "112") (name "/D3") (class "Default")
      (node (ref "CAP3") (pin "4") (pinfunction "4_4") (pintype "passive"))
      (node (ref "EXTBUS") (pin "37") (pinfunction "37_37") (pintype "passive"))
      (node (ref "J2") (pin "8") (pinfunction "8_8") (pintype "passive"))
      (node (ref "U1") (pin "19") (pinfunction "DB3_19") (pintype "passive"))
      (node (ref "U2") (pin "19") (pinfunction "DB3_19") (pintype "passive"))
      (node (ref "U25") (pin "20") (pinfunction "D3_20") (pintype "passive"))
      (node (ref "U28") (pin "43") (pinfunction "43_43") (pintype "passive"))
    )
    (net (code "113") (name "/D4") (class "Default")
      (node (ref "CAP3") (pin "5") (pinfunction "5_5") (pintype "passive"))
      (node (ref "EXTBUS") (pin "36") (pinfunction "36_36") (pintype "passive"))
      (node (ref "J2") (pin "10") (pinfunction "10_10") (pintype "passive"))
      (node (ref "U1") (pin "20") (pinfunction "DB4_20") (pintype "passive"))
      (node (ref "U2") (pin "20") (pinfunction "DB4_20") (pintype "passive"))
      (node (ref "U25") (pin "21") (pinfunction "D4_21") (pintype "passive"))
      (node (ref "U28") (pin "41") (pinfunction "41_41") (pintype "passive"))
    )
    (net (code "114") (name "/D5") (class "Default")
      (node (ref "CAP3") (pin "6") (pinfunction "6_6") (pintype "passive"))
      (node (ref "EXTBUS") (pin "35") (pinfunction "35_35") (pintype "passive"))
      (node (ref "J2") (pin "12") (pinfunction "12_12") (pintype "passive"))
      (node (ref "U1") (pin "21") (pinfunction "DB5_21") (pintype "passive"))
      (node (ref "U2") (pin "21") (pinfunction "DB5_21") (pintype "passive"))
      (node (ref "U25") (pin "22") (pinfunction "D5_22") (pintype "passive"))
      (node (ref "U28") (pin "40") (pinfunction "40_40") (pintype "passive"))
    )
    (net (code "115") (name "/D6") (class "Default")
      (node (ref "CAP3") (pin "7") (pinfunction "7_7") (pintype "passive"))
      (node (ref "EXTBUS") (pin "34") (pinfunction "34_34") (pintype "passive"))
      (node (ref "J2") (pin "14") (pinfunction "14_14") (pintype "passive"))
      (node (ref "U1") (pin "22") (pinfunction "DB6_22") (pintype "passive"))
      (node (ref "U2") (pin "22") (pinfunction "DB6_22") (pintype "passive"))
      (node (ref "U25") (pin "23") (pinfunction "D6_23") (pintype "passive"))
      (node (ref "U28") (pin "39") (pinfunction "39_39") (pintype "passive"))
    )
    (net (code "116") (name "/D7") (class "Default")
      (node (ref "CAP3") (pin "8") (pinfunction "8_8") (pintype "passive"))
      (node (ref "EXTBUS") (pin "33") (pinfunction "33_33") (pintype "passive"))
      (node (ref "J2") (pin "16") (pinfunction "16_16") (pintype "passive"))
      (node (ref "U1") (pin "24") (pinfunction "DB7/DOUTA_24") (pintype "passive"))
      (node (ref "U2") (pin "24") (pinfunction "DB7/DOUTA_24") (pintype "passive"))
      (node (ref "U25") (pin "24") (pinfunction "D7_24") (pintype "passive"))
      (node (ref "U28") (pin "38") (pinfunction "IO/GCK3_38") (pintype "passive"))
    )
    (net (code "117") (name "/D8") (class "Default")
      (node (ref "CAP3") (pin "9") (pinfunction "9_9") (pintype "passive"))
      (node (ref "EXTBUS") (pin "32") (pinfunction "32_32") (pintype "passive"))
      (node (ref "J2") (pin "13") (pinfunction "13_13") (pintype "passive"))
      (node (ref "U1") (pin "25") (pinfunction "DB8/DOUTB_25") (pintype "passive"))
      (node (ref "U2") (pin "25") (pinfunction "DB8/DOUTB_25") (pintype "passive"))
      (node (ref "U25") (pin "25") (pinfunction "D8_25") (pintype "passive"))
    )
    (net (code "118") (name "/D9") (class "Default")
      (node (ref "CAP3") (pin "10") (pinfunction "10_10") (pintype "passive"))
      (node (ref "EXTBUS") (pin "31") (pinfunction "31_31") (pintype "passive"))
      (node (ref "J2") (pin "15") (pinfunction "15_15") (pintype "passive"))
      (node (ref "U1") (pin "27") (pinfunction "DB9_27") (pintype "passive"))
      (node (ref "U2") (pin "27") (pinfunction "DB9_27") (pintype "passive"))
      (node (ref "U25") (pin "26") (pinfunction "D9_26") (pintype "passive"))
    )
    (net (code "119") (name "/D10") (class "Default")
      (node (ref "CAP3") (pin "11") (pinfunction "11_11") (pintype "passive"))
      (node (ref "EXTBUS") (pin "30") (pinfunction "30_30") (pintype "passive"))
      (node (ref "J2") (pin "17") (pinfunction "17_17") (pintype "passive"))
      (node (ref "U1") (pin "28") (pinfunction "DB10_28") (pintype "passive"))
      (node (ref "U2") (pin "28") (pinfunction "DB10_28") (pintype "passive"))
      (node (ref "U25") (pin "27") (pinfunction "D10_27") (pintype "passive"))
    )
    (net (code "120") (name "/D11") (class "Default")
      (node (ref "CAP3") (pin "12") (pinfunction "12_12") (pintype "passive"))
      (node (ref "EXTBUS") (pin "29") (pinfunction "29_29") (pintype "passive"))
      (node (ref "J2") (pin "19") (pinfunction "19_19") (pintype "passive"))
      (node (ref "U1") (pin "29") (pinfunction "DB11_29") (pintype "passive"))
      (node (ref "U2") (pin "29") (pinfunction "DB11_29") (pintype "passive"))
      (node (ref "U25") (pin "28") (pinfunction "D11_28") (pintype "passive"))
    )
    (net (code "121") (name "/D12") (class "Default")
      (node (ref "CAP3") (pin "13") (pinfunction "13_13") (pintype "passive"))
      (node (ref "EXTBUS") (pin "28") (pinfunction "28_28") (pintype "passive"))
      (node (ref "J2") (pin "21") (pinfunction "21_21") (pintype "passive"))
      (node (ref "U1") (pin "30") (pinfunction "DB12_30") (pintype "passive"))
      (node (ref "U2") (pin "30") (pinfunction "DB12_30") (pintype "passive"))
    )
    (net (code "122") (name "/D13") (class "Default")
      (node (ref "CAP3") (pin "14") (pinfunction "14_14") (pintype "passive"))
      (node (ref "EXTBUS") (pin "27") (pinfunction "27_27") (pintype "passive"))
      (node (ref "J2") (pin "23") (pinfunction "23_23") (pintype "passive"))
      (node (ref "U1") (pin "31") (pinfunction "DB13_31") (pintype "passive"))
      (node (ref "U2") (pin "31") (pinfunction "DB13_31") (pintype "passive"))
    )
    (net (code "123") (name "/D14") (class "Default")
      (node (ref "CAP3") (pin "15") (pinfunction "15_15") (pintype "passive"))
      (node (ref "EXTBUS") (pin "26") (pinfunction "26_26") (pintype "passive"))
      (node (ref "J2") (pin "25") (pinfunction "25_25") (pintype "passive"))
      (node (ref "U1") (pin "32") (pinfunction "DB14/HBEN_32") (pintype "passive"))
      (node (ref "U2") (pin "32") (pinfunction "DB14/HBEN_32") (pintype "passive"))
    )
    (net (code "124") (name "/D15") (class "Default")
      (node (ref "CAP3") (pin "16") (pinfunction "16_16") (pintype "passive"))
      (node (ref "EXTBUS") (pin "25") (pinfunction "25_25") (pintype "passive"))
      (node (ref "J2") (pin "27") (pinfunction "27_27") (pintype "passive"))
      (node (ref "U1") (pin "33") (pinfunction "DB15/BYTESEL_33") (pintype "passive"))
      (node (ref "U2") (pin "33") (pinfunction "DB15/BYTESEL_33") (pintype "passive"))
    )
    (net (code "125") (name "/DAC0") (class "Default")
      (node (ref "R184") (pin "2") (pintype "passive"))
      (node (ref "U25") (pin "5") (pinfunction "VOUTA_5") (pintype "passive"))
    )
    (net (code "126") (name "/DAC1") (class "Default")
      (node (ref "R186") (pin "2") (pintype "passive"))
      (node (ref "U25") (pin "6") (pinfunction "VOUTB_6") (pintype "passive"))
    )
    (net (code "127") (name "/DAC2") (class "Default")
      (node (ref "R185") (pin "2") (pintype "passive"))
      (node (ref "U25") (pin "7") (pinfunction "VOUTC_7") (pintype "passive"))
    )
    (net (code "128") (name "/DAC3") (class "Default")
      (node (ref "R183") (pin "2") (pintype "passive"))
      (node (ref "U25") (pin "8") (pinfunction "VOUTD_8") (pintype "passive"))
    )
    (net (code "129") (name "/DSPSOMI") (class "Default")
      (node (ref "CAP3") (pin "102") (pinfunction "102_102") (pintype "passive"))
      (node (ref "U13") (pin "4") (pinfunction "1A2_4") (pintype "bidirectional"))
      (node (ref "U28") (pin "12") (pinfunction "12_12") (pintype "passive"))
    )
    (net (code "130") (name "/DSP_IO1{slash}QEPA") (class "Default")
      (node (ref "CAP3") (pin "97") (pinfunction "97_97") (pintype "passive"))
      (node (ref "U28") (pin "10") (pinfunction "10_10") (pintype "passive"))
    )
    (net (code "131") (name "/DSP_IO2{slash}QEPB") (class "Default")
      (node (ref "CAP3") (pin "98") (pinfunction "98_98") (pintype "passive"))
      (node (ref "U28") (pin "9") (pinfunction "9_9") (pintype "passive"))
    )
    (net (code "132") (name "/DSP_IO3{slash}QEPS") (class "Default")
      (node (ref "CAP3") (pin "99") (pinfunction "99_99") (pintype "passive"))
      (node (ref "U28") (pin "7") (pinfunction "7_7") (pintype "passive"))
    )
    (net (code "133") (name "/DSP_IO4{slash}QEPI") (class "Default")
      (node (ref "CAP3") (pin "100") (pinfunction "100_100") (pintype "passive"))
      (node (ref "U28") (pin "6") (pinfunction "IO/GTS2_6") (pintype "passive"))
    )
    (net (code "134") (name "/DSP_IO{slash}MCLKRA") (class "Default")
      (node (ref "CAP3") (pin "105") (pinfunction "105_105") (pintype "passive"))
      (node (ref "P19") (pin "2") (pinfunction "2_2") (pintype "passive"))
    )
    (net (code "135") (name "/DSP_IO{slash}MCLKRB") (class "Default")
      (node (ref "CAP3") (pin "107") (pinfunction "107_107") (pintype "passive"))
      (node (ref "P21") (pin "2") (pinfunction "2_2") (pintype "passive"))
    )
    (net (code "136") (name "/DSP_IO{slash}MFSRA") (class "Default")
      (node (ref "CAP3") (pin "106") (pinfunction "106_106") (pintype "passive"))
      (node (ref "P20") (pin "2") (pinfunction "2_2") (pintype "passive"))
    )
    (net (code "137") (name "/DSP_IO{slash}MFSRB") (class "Default")
      (node (ref "CAP3") (pin "108") (pinfunction "108_108") (pintype "passive"))
      (node (ref "P22") (pin "2") (pinfunction "2_2") (pintype "passive"))
    )
    (net (code "138") (name "/ELINK#") (class "Default")
      (node (ref "R46") (pin "1") (pintype "passive"))
      (node (ref "U12") (pin "104") (pinfunction "ELINK#_104") (pintype "passive"))
    )
    (net (code "139") (name "/EXCAP1-QEP") (class "Default")
      (node (ref "J7") (pin "2") (pinfunction "2_2") (pintype "passive"))
      (node (ref "U28") (pin "118") (pinfunction "118_118") (pintype "passive"))
    )
    (net (code "140") (name "/EXCAP2-QEP") (class "Default")
      (node (ref "J7") (pin "3") (pinfunction "3_3") (pintype "passive"))
      (node (ref "U28") (pin "117") (pinfunction "117_117") (pintype "passive"))
    )
    (net (code "141") (name "/EXCAP3-QEP") (class "Default")
      (node (ref "J7") (pin "4") (pinfunction "4_4") (pintype "passive"))
      (node (ref "U28") (pin "116") (pinfunction "116_116") (pintype "passive"))
    )
    (net (code "142") (name "/EXCAP4-QEP") (class "Default")
      (node (ref "J8") (pin "2") (pinfunction "2_2") (pintype "passive"))
      (node (ref "U28") (pin "143") (pinfunction "IO/GSR_143") (pintype "passive"))
    )
    (net (code "143") (name "/EXCS0") (class "Default")
      (node (ref "CAP3") (pin "43") (pinfunction "43_43") (pintype "passive"))
      (node (ref "EXTBUS") (pin "54") (pinfunction "54_54") (pintype "passive"))
      (node (ref "U28") (pin "69") (pinfunction "69_69") (pintype "passive"))
    )
    (net (code "144") (name "/EXCS1") (class "Default")
      (node (ref "CAP3") (pin "42") (pinfunction "42_42") (pintype "passive"))
      (node (ref "EXTBUS") (pin "44") (pinfunction "44_44") (pintype "passive"))
      (node (ref "U28") (pin "70") (pinfunction "70_70") (pintype "passive"))
    )
    (net (code "145") (name "/EXINT1") (class "Default")
      (node (ref "P13") (pin "2") (pinfunction "2_2") (pintype "passive"))
    )
    (net (code "146") (name "/EXINT2") (class "Default")
      (node (ref "CAP3") (pin "49") (pinfunction "49_49") (pintype "passive"))
      (node (ref "P14") (pin "2") (pinfunction "2_2") (pintype "passive"))
    )
    (net (code "147") (name "/EXNMI") (class "Default")
      (node (ref "CAP3") (pin "47") (pinfunction "47_47") (pintype "passive"))
      (node (ref "P18") (pin "2") (pinfunction "2_2") (pintype "passive"))
    )
    (net (code "148") (name "/HOLD") (class "Default")
      (node (ref "P17") (pin "1") (pinfunction "1_1") (pintype "passive"))
    )
    (net (code "149") (name "/HOLDA") (class "Default")
      (node (ref "P16") (pin "1") (pinfunction "1_1") (pintype "passive"))
    )
    (net (code "150") (name "/IN1") (class "Default")
      (node (ref "J10") (pin "6") (pinfunction "6_6") (pintype "passive"))
      (node (ref "U28") (pin "91") (pinfunction "91_91") (pintype "passive"))
    )
    (net (code "151") (name "/IN2") (class "Default")
      (node (ref "J10") (pin "7") (pinfunction "7_7") (pintype "passive"))
      (node (ref "U28") (pin "88") (pinfunction "88_88") (pintype "passive"))
    )
    (net (code "152") (name "/IN3") (class "Default")
      (node (ref "J10") (pin "8") (pinfunction "8_8") (pintype "passive"))
      (node (ref "U28") (pin "87") (pinfunction "87_87") (pintype "passive"))
    )
    (net (code "153") (name "/IN4") (class "Default")
      (node (ref "J10") (pin "9") (pinfunction "9_9") (pintype "passive"))
      (node (ref "U28") (pin "86") (pinfunction "86_86") (pintype "passive"))
    )
    (net (code "154") (name "/IN5") (class "Default")
      (node (ref "J10") (pin "10") (pinfunction "10_10") (pintype "passive"))
      (node (ref "U28") (pin "85") (pinfunction "85_85") (pintype "passive"))
    )
    (net (code "155") (name "/LCD-PWM") (class "Default")
      (node (ref "J2") (pin "37") (pinfunction "37_37") (pintype "passive"))
      (node (ref "U28") (pin "96") (pinfunction "96_96") (pintype "passive"))
    )
    (net (code "156") (name "/LCD1CS") (class "Default")
      (node (ref "J2") (pin "29") (pinfunction "29_29") (pintype "passive"))
      (node (ref "U28") (pin "93") (pinfunction "93_93") (pintype "passive"))
    )
    (net (code "157") (name "/LCDRESET") (class "Default")
      (node (ref "J2") (pin "33") (pinfunction "33_33") (pintype "passive"))
      (node (ref "U28") (pin "80") (pinfunction "80_80") (pintype "passive"))
    )
    (net (code "158") (name "/MCLKRA") (class "Default")
      (node (ref "J10") (pin "13") (pinfunction "13_13") (pintype "passive"))
      (node (ref "P19") (pin "1") (pinfunction "1_1") (pintype "passive"))
    )
    (net (code "159") (name "/MCLKRB") (class "Default")
      (node (ref "J10") (pin "14") (pinfunction "14_14") (pintype "passive"))
      (node (ref "P21") (pin "1") (pinfunction "1_1") (pintype "passive"))
    )
    (net (code "160") (name "/MFSRA") (class "Default")
      (node (ref "J10") (pin "11") (pinfunction "11_11") (pintype "passive"))
      (node (ref "P20") (pin "1") (pinfunction "1_1") (pintype "passive"))
    )
    (net (code "161") (name "/MFSRB") (class "Default")
      (node (ref "J10") (pin "12") (pinfunction "12_12") (pintype "passive"))
      (node (ref "P22") (pin "1") (pinfunction "1_1") (pintype "passive"))
    )
    (net (code "162") (name "/NET-INT") (class "Default")
      (node (ref "U12") (pin "98") (pinfunction "INT#_98") (pintype "passive"))
      (node (ref "U28") (pin "56") (pinfunction "56_56") (pintype "passive"))
    )
    (net (code "163") (name "/NETCS") (class "Default")
      (node (ref "U12") (pin "114") (pinfunction "SCS_114") (pintype "passive"))
      (node (ref "U28") (pin "54") (pinfunction "54_54") (pintype "passive"))
    )
    (net (code "164") (name "/NETINT") (class "Default")
      (node (ref "P14") (pin "3") (pinfunction "3_3") (pintype "passive"))
      (node (ref "U28") (pin "68") (pinfunction "68_68") (pintype "passive"))
    )
    (net (code "165") (name "/NETSOMI") (class "Default")
      (node (ref "U12") (pin "117") (pinfunction "SDO_117") (pintype "passive"))
      (node (ref "U28") (pin "83") (pinfunction "83_83") (pintype "passive"))
    )
    (net (code "166") (name "/NET{slash}USBCS") (class "Default")
      (node (ref "P24") (pin "3") (pinfunction "3_3") (pintype "passive"))
      (node (ref "U28") (pin "11") (pinfunction "11_11") (pintype "passive"))
    )
    (net (code "167") (name "/NMI") (class "Default")
      (node (ref "J10") (pin "18") (pinfunction "18_18") (pintype "passive"))
      (node (ref "P18") (pin "1") (pinfunction "1_1") (pintype "passive"))
    )
    (net (code "168") (name "/OPWM1") (class "Default")
      (node (ref "U28") (pin "125") (pinfunction "125_125") (pintype "passive"))
      (node (ref "U3") (pin "21") (pinfunction "B1_21") (pintype "passive"))
    )
    (net (code "169") (name "/OPWM2") (class "Default")
      (node (ref "U28") (pin "126") (pinfunction "126_126") (pintype "passive"))
      (node (ref "U3") (pin "20") (pinfunction "B2_20") (pintype "passive"))
    )
    (net (code "170") (name "/OPWM3") (class "Default")
      (node (ref "U28") (pin "128") (pinfunction "128_128") (pintype "passive"))
      (node (ref "U3") (pin "19") (pinfunction "B3_19") (pintype "passive"))
    )
    (net (code "171") (name "/OPWM4") (class "Default")
      (node (ref "U28") (pin "129") (pinfunction "129_129") (pintype "passive"))
      (node (ref "U3") (pin "18") (pinfunction "B4_18") (pintype "passive"))
    )
    (net (code "172") (name "/OPWM5") (class "Default")
      (node (ref "U28") (pin "130") (pinfunction "130_130") (pintype "passive"))
      (node (ref "U3") (pin "17") (pinfunction "B5_17") (pintype "passive"))
    )
    (net (code "173") (name "/OPWM6") (class "Default")
      (node (ref "U28") (pin "131") (pinfunction "131_131") (pintype "passive"))
      (node (ref "U3") (pin "16") (pinfunction "B6_16") (pintype "passive"))
    )
    (net (code "174") (name "/OPWM7") (class "Default")
      (node (ref "U28") (pin "136") (pinfunction "136_136") (pintype "passive"))
      (node (ref "U4") (pin "21") (pinfunction "B1_21") (pintype "passive"))
    )
    (net (code "175") (name "/OPWM8") (class "Default")
      (node (ref "U28") (pin "137") (pinfunction "137_137") (pintype "passive"))
      (node (ref "U4") (pin "20") (pinfunction "B2_20") (pintype "passive"))
    )
    (net (code "176") (name "/OPWM9") (class "Default")
      (node (ref "U28") (pin "138") (pinfunction "138_138") (pintype "passive"))
      (node (ref "U4") (pin "19") (pinfunction "B3_19") (pintype "passive"))
    )
    (net (code "177") (name "/OPWM10") (class "Default")
      (node (ref "U28") (pin "139") (pinfunction "139_139") (pintype "passive"))
      (node (ref "U4") (pin "18") (pinfunction "B4_18") (pintype "passive"))
    )
    (net (code "178") (name "/OPWM11") (class "Default")
      (node (ref "U28") (pin "140") (pinfunction "140_140") (pintype "passive"))
      (node (ref "U4") (pin "17") (pinfunction "B5_17") (pintype "passive"))
    )
    (net (code "179") (name "/OPWM12") (class "Default")
      (node (ref "U28") (pin "142") (pinfunction "142_142") (pintype "passive"))
      (node (ref "U4") (pin "16") (pinfunction "B6_16") (pintype "passive"))
    )
    (net (code "180") (name "/OUT1") (class "Default")
      (node (ref "J10") (pin "1") (pinfunction "1_1") (pintype "passive"))
      (node (ref "U28") (pin "102") (pinfunction "102_102") (pintype "passive"))
    )
    (net (code "181") (name "/OUT2") (class "Default")
      (node (ref "J10") (pin "2") (pinfunction "2_2") (pintype "passive"))
      (node (ref "U28") (pin "101") (pinfunction "101_101") (pintype "passive"))
    )
    (net (code "182") (name "/OUT3") (class "Default")
      (node (ref "J10") (pin "3") (pinfunction "3_3") (pintype "passive"))
      (node (ref "U28") (pin "100") (pinfunction "100_100") (pintype "passive"))
    )
    (net (code "183") (name "/OUT4") (class "Default")
      (node (ref "J10") (pin "4") (pinfunction "4_4") (pintype "passive"))
      (node (ref "U28") (pin "98") (pinfunction "98_98") (pintype "passive"))
    )
    (net (code "184") (name "/OUT5") (class "Default")
      (node (ref "J10") (pin "5") (pinfunction "5_5") (pintype "passive"))
      (node (ref "U28") (pin "97") (pinfunction "97_97") (pintype "passive"))
    )
    (net (code "185") (name "/PDPINTA*") (class "Default")
      (node (ref "CAP3") (pin "91") (pinfunction "91_91") (pintype "passive"))
      (node (ref "U28") (pin "19") (pinfunction "19_19") (pintype "passive"))
    )
    (net (code "186") (name "/PDPINTB*") (class "Default")
      (node (ref "CAP3") (pin "92") (pinfunction "92_92") (pintype "passive"))
      (node (ref "U28") (pin "17") (pinfunction "17_17") (pintype "passive"))
    )
    (net (code "187") (name "/PWM1") (class "Default")
      (node (ref "CAP3") (pin "79") (pinfunction "79_79") (pintype "passive"))
      (node (ref "U28") (pin "32") (pinfunction "IO/GCK2_32") (pintype "passive"))
    )
    (net (code "188") (name "/PWM2") (class "Default")
      (node (ref "CAP3") (pin "80") (pinfunction "80_80") (pintype "passive"))
      (node (ref "U28") (pin "31") (pinfunction "31_31") (pintype "passive"))
    )
    (net (code "189") (name "/PWM3") (class "Default")
      (node (ref "CAP3") (pin "81") (pinfunction "81_81") (pintype "passive"))
      (node (ref "U28") (pin "30") (pinfunction "IO/GCK1_30") (pintype "passive"))
    )
    (net (code "190") (name "/PWM4") (class "Default")
      (node (ref "CAP3") (pin "82") (pinfunction "82_82") (pintype "passive"))
      (node (ref "U28") (pin "28") (pinfunction "28_28") (pintype "passive"))
    )
    (net (code "191") (name "/PWM5") (class "Default")
      (node (ref "CAP3") (pin "83") (pinfunction "83_83") (pintype "passive"))
      (node (ref "U28") (pin "27") (pinfunction "27_27") (pintype "passive"))
    )
    (net (code "192") (name "/PWM6") (class "Default")
      (node (ref "CAP3") (pin "84") (pinfunction "84_84") (pintype "passive"))
      (node (ref "U28") (pin "26") (pinfunction "26_26") (pintype "passive"))
    )
    (net (code "193") (name "/PWM7") (class "Default")
      (node (ref "CAP3") (pin "85") (pinfunction "85_85") (pintype "passive"))
      (node (ref "U28") (pin "25") (pinfunction "25_25") (pintype "passive"))
    )
    (net (code "194") (name "/PWM8") (class "Default")
      (node (ref "CAP3") (pin "86") (pinfunction "86_86") (pintype "passive"))
      (node (ref "U28") (pin "24") (pinfunction "24_24") (pintype "passive"))
    )
    (net (code "195") (name "/PWM9") (class "Default")
      (node (ref "CAP3") (pin "87") (pinfunction "87_87") (pintype "passive"))
      (node (ref "U28") (pin "23") (pinfunction "23_23") (pintype "passive"))
    )
    (net (code "196") (name "/PWM10") (class "Default")
      (node (ref "CAP3") (pin "88") (pinfunction "88_88") (pintype "passive"))
      (node (ref "U28") (pin "22") (pinfunction "22_22") (pintype "passive"))
    )
    (net (code "197") (name "/PWM11") (class "Default")
      (node (ref "CAP3") (pin "89") (pinfunction "89_89") (pintype "passive"))
      (node (ref "U28") (pin "21") (pinfunction "21_21") (pintype "passive"))
    )
    (net (code "198") (name "/PWM12") (class "Default")
      (node (ref "CAP3") (pin "90") (pinfunction "90_90") (pintype "passive"))
      (node (ref "U28") (pin "20") (pinfunction "20_20") (pintype "passive"))
    )
    (net (code "199") (name "/RDY#") (class "Default")
      (node (ref "R47") (pin "1") (pintype "passive"))
      (node (ref "U12") (pin "51") (pinfunction "RDY#_51") (pintype "passive"))
    )
    (net (code "200") (name "/READY") (class "Default")
      (node (ref "EXTBUS") (pin "46") (pinfunction "46_46") (pintype "passive"))
      (node (ref "P15") (pin "1") (pinfunction "1_1") (pintype "passive"))
    )
    (net (code "201") (name "/RESET") (class "Default")
      (node (ref "CAP3") (pin "54") (pinfunction "54_54") (pintype "passive"))
    )
    (net (code "202") (name "/RST") (class "Default")
      (node (ref "U12") (pin "52") (pinfunction "RST_52") (pintype "passive"))
    )
    (net (code "203") (name "/RSTI") (class "Default")
      (node (ref "C133") (pin "2") (pintype "passive"))
      (node (ref "U12") (pin "63") (pinfunction "RSTI_63") (pintype "passive"))
    )
    (net (code "204") (name "/RXD") (class "Default")
      (node (ref "U12") (pin "112") (pinfunction "RXD_112") (pintype "passive"))
    )
    (net (code "205") (name "/RXIN") (class "Default")
      (node (ref "R33") (pin "1") (pintype "passive"))
      (node (ref "U11") (pin "8") (pinfunction "RDN_8") (pintype "passive"))
      (node (ref "U12") (pin "11") (pinfunction "RXIN_11") (pintype "passive"))
    )
    (net (code "206") (name "/RXIP") (class "Default")
      (node (ref "R34") (pin "1") (pintype "passive"))
      (node (ref "U11") (pin "6") (pinfunction "RDP_6") (pintype "passive"))
      (node (ref "U12") (pin "10") (pinfunction "RXIP_10") (pintype "passive"))
    )
    (net (code "207") (name "/R{slash}W") (class "Default")
      (node (ref "CAP3") (pin "41") (pinfunction "41_41") (pintype "passive"))
      (node (ref "P23") (pin "2") (pinfunction "2_2") (pintype "passive"))
    )
    (net (code "208") (name "/SCAP1") (class "Default")
      (node (ref "U28") (pin "132") (pinfunction "132_132") (pintype "passive"))
      (node (ref "U3") (pin "15") (pinfunction "B7_15") (pintype "passive"))
    )
    (net (code "209") (name "/SCAP2") (class "Default")
      (node (ref "U28") (pin "133") (pinfunction "133_133") (pintype "passive"))
      (node (ref "U3") (pin "14") (pinfunction "B8_14") (pintype "passive"))
    )
    (net (code "210") (name "/SCAP3") (class "Default")
      (node (ref "U28") (pin "134") (pinfunction "134_134") (pintype "passive"))
      (node (ref "U4") (pin "15") (pinfunction "B7_15") (pintype "passive"))
    )
    (net (code "211") (name "/SCAP4") (class "Default")
      (node (ref "U28") (pin "135") (pinfunction "135_135") (pintype "passive"))
      (node (ref "U4") (pin "14") (pinfunction "B8_14") (pintype "passive"))
    )
    (net (code "212") (name "/SCI-485-ISO") (class "Default")
      (node (ref "P7") (pin "3") (pinfunction "3_3") (pintype "passive"))
      (node (ref "P8") (pin "2") (pinfunction "2_2") (pintype "passive"))
    )
    (net (code "213") (name "/SCI-485-R") (class "Default")
      (node (ref "P7") (pin "1") (pinfunction "1_1") (pintype "passive"))
      (node (ref "U8") (pin "1") (pintype "output"))
    )
    (net (code "214") (name "/SCI-485-T") (class "Default")
      (node (ref "P6") (pin "1") (pinfunction "1_1") (pintype "passive"))
      (node (ref "U8") (pin "4") (pintype "input"))
    )
    (net (code "215") (name "/SCI-485-T-ISO") (class "Default")
      (node (ref "P6") (pin "3") (pinfunction "3_3") (pintype "passive"))
      (node (ref "P8") (pin "1") (pinfunction "1_1") (pintype "passive"))
    )
    (net (code "216") (name "/SCI-485EN") (class "Default")
      (node (ref "P10") (pin "1") (pinfunction "1_1") (pintype "passive"))
      (node (ref "U8") (pin "2") (pintype "input"))
      (node (ref "U8") (pin "3") (pintype "input"))
    )
    (net (code "217") (name "/SCI-485EN-ISO") (class "Default")
      (node (ref "P10") (pin "3") (pinfunction "3_3") (pintype "passive"))
      (node (ref "P8") (pin "3") (pinfunction "3_3") (pintype "passive"))
    )
    (net (code "218") (name "/SCIRXDB") (class "Default")
      (node (ref "CAP3") (pin "109") (pinfunction "109_109") (pintype "passive"))
      (node (ref "U9") (pin "12") (pinfunction "R1out_12") (pintype "passive"))
    )
    (net (code "219") (name "/SCIRXDC") (class "Default")
      (node (ref "CAP3") (pin "111") (pinfunction "111_111") (pintype "passive"))
      (node (ref "P2") (pin "2") (pinfunction "2_2") (pintype "passive"))
    )
    (net (code "220") (name "/SCIRXDC-232") (class "Default")
      (node (ref "P2") (pin "3") (pinfunction "3_3") (pintype "passive"))
      (node (ref "U9") (pin "9") (pinfunction "R2out_9") (pintype "passive"))
    )
    (net (code "221") (name "/SCIRXDC-485") (class "Default")
      (node (ref "P2") (pin "1") (pinfunction "1_1") (pintype "passive"))
      (node (ref "P7") (pin "2") (pinfunction "2_2") (pintype "passive"))
    )
    (net (code "222") (name "/SCITXDB") (class "Default")
      (node (ref "CAP3") (pin "110") (pinfunction "110_110") (pintype "passive"))
      (node (ref "U9") (pin "11") (pinfunction "T1in_11") (pintype "passive"))
    )
    (net (code "223") (name "/SCITXDC") (class "Default")
      (node (ref "CAP3") (pin "112") (pinfunction "112_112") (pintype "passive"))
      (node (ref "P1") (pin "2") (pinfunction "2_2") (pintype "passive"))
    )
    (net (code "224") (name "/SCITXDC-232") (class "Default")
      (node (ref "P1") (pin "3") (pinfunction "3_3") (pintype "passive"))
      (node (ref "U9") (pin "10") (pinfunction "T2in_10") (pintype "passive"))
    )
    (net (code "225") (name "/SCITXDC-485") (class "Default")
      (node (ref "P1") (pin "1") (pinfunction "1_1") (pintype "passive"))
      (node (ref "P6") (pin "2") (pinfunction "2_2") (pintype "passive"))
    )
    (net (code "226") (name "/SCL") (class "Default")
      (node (ref "CAP3") (pin "114") (pinfunction "114_114") (pintype "passive"))
      (node (ref "R35") (pin "2") (pintype "passive"))
      (node (ref "U13") (pin "21") (pinfunction "2A4_21") (pintype "bidirectional"))
    )
    (net (code "227") (name "/SDA") (class "Default")
      (node (ref "CAP3") (pin "113") (pinfunction "113_113") (pintype "passive"))
      (node (ref "R36") (pin "2") (pintype "passive"))
      (node (ref "U13") (pin "22") (pinfunction "2A5_22") (pintype "bidirectional"))
    )
    (net (code "228") (name "/SEL") (class "Default")
      (node (ref "U12") (pin "53") (pinfunction "SEL_53") (pintype "passive"))
    )
    (net (code "229") (name "/SPICLK") (class "Default")
      (node (ref "CAP3") (pin "103") (pinfunction "103_103") (pintype "passive"))
      (node (ref "U12") (pin "115") (pinfunction "SCK_115") (pintype "passive"))
      (node (ref "U13") (pin "7") (pinfunction "1A3_7") (pintype "bidirectional"))
      (node (ref "U6") (pin "20") (pinfunction "SCK/D5_20") (pintype "bidirectional"))
    )
    (net (code "230") (name "/SPISIMO") (class "Default")
      (node (ref "CAP3") (pin "101") (pinfunction "101_101") (pintype "passive"))
      (node (ref "U12") (pin "116") (pinfunction "SDI_116") (pintype "passive"))
      (node (ref "U13") (pin "3") (pinfunction "1A1_3") (pintype "bidirectional"))
      (node (ref "U6") (pin "21") (pinfunction "SDI/D6_21") (pintype "bidirectional"))
    )
    (net (code "231") (name "/SPISTE") (class "Default")
      (node (ref "P24") (pin "1") (pinfunction "1_1") (pintype "passive"))
      (node (ref "U13") (pin "8") (pinfunction "1A4_8") (pintype "bidirectional"))
    )
    (net (code "232") (name "/SPISTE{slash}INT") (class "Default")
      (node (ref "CAP3") (pin "104") (pinfunction "104_104") (pintype "passive"))
      (node (ref "P24") (pin "2") (pinfunction "2_2") (pintype "passive"))
    )
    (net (code "233") (name "/T-CLK") (class "Default")
      (node (ref "J3") (pin "33") (pinfunction "33_33") (pintype "passive"))
      (node (ref "U28") (pin "115") (pinfunction "115_115") (pintype "passive"))
    )
    (net (code "234") (name "/T-CS") (class "Default")
      (node (ref "J3") (pin "31") (pinfunction "31_31") (pintype "passive"))
      (node (ref "U28") (pin "113") (pinfunction "113_113") (pintype "passive"))
    )
    (net (code "235") (name "/T-DIN") (class "Default")
      (node (ref "J3") (pin "29") (pinfunction "29_29") (pintype "passive"))
      (node (ref "U28") (pin "112") (pinfunction "112_112") (pintype "passive"))
    )
    (net (code "236") (name "/T-DO") (class "Default")
      (node (ref "J3") (pin "7") (pinfunction "7_7") (pintype "passive"))
      (node (ref "RL3") (pin "2") (pintype "passive"))
      (node (ref "U28") (pin "94") (pinfunction "94_94") (pintype "passive"))
    )
    (net (code "237") (name "/TCLK") (class "Default")
      (node (ref "P19") (pin "3") (pinfunction "3_3") (pintype "passive"))
      (node (ref "U28") (pin "5") (pinfunction "IO/GTS1_5") (pintype "passive"))
    )
    (net (code "238") (name "/TCS") (class "Default")
      (node (ref "P21") (pin "3") (pinfunction "3_3") (pintype "passive"))
      (node (ref "U28") (pin "3") (pinfunction "IO/GTS4_3") (pintype "passive"))
    )
    (net (code "239") (name "/TDIN") (class "Default")
      (node (ref "P22") (pin "3") (pinfunction "3_3") (pintype "passive"))
      (node (ref "U28") (pin "2") (pinfunction "IO/GTS3_2") (pintype "passive"))
    )
    (net (code "240") (name "/TDO") (class "Default")
      (node (ref "P20") (pin "3") (pinfunction "3_3") (pintype "passive"))
      (node (ref "U28") (pin "4") (pinfunction "4_4") (pintype "passive"))
    )
    (net (code "241") (name "/TIRQ") (class "Default")
      (node (ref "P18") (pin "3") (pinfunction "3_3") (pintype "passive"))
      (node (ref "U28") (pin "64") (pinfunction "64_64") (pintype "passive"))
    )
    (net (code "242") (name "/TXON") (class "Default")
      (node (ref "R42") (pin "1") (pintype "passive"))
      (node (ref "U11") (pin "3") (pinfunction "TDN_3") (pintype "passive"))
      (node (ref "U12") (pin "15") (pinfunction "TXON_15") (pintype "passive"))
    )
    (net (code "243") (name "/TXOP") (class "Default")
      (node (ref "R43") (pin "1") (pintype "passive"))
      (node (ref "U11") (pin "1") (pinfunction "TDP_1") (pintype "passive"))
      (node (ref "U12") (pin "14") (pinfunction "TXOP_14") (pintype "passive"))
    )
    (net (code "244") (name "/UD+") (class "Default")
      (node (ref "P3") (pin "3") (pintype "passive"))
      (node (ref "U6") (pin "10") (pinfunction "UD+_10") (pintype "bidirectional"))
    )
    (net (code "245") (name "/UD-") (class "Default")
      (node (ref "P3") (pin "2") (pintype "passive"))
      (node (ref "U6") (pin "11") (pinfunction "UD-_11") (pintype "bidirectional"))
    )
    (net (code "246") (name "/USB-INT") (class "Default")
      (node (ref "U28") (pin "58") (pinfunction "58_58") (pintype "passive"))
      (node (ref "U6") (pin "1") (pinfunction "INT#_1") (pintype "output"))
    )
    (net (code "247") (name "/USBCS") (class "Default")
      (node (ref "U28") (pin "57") (pinfunction "57_57") (pintype "passive"))
      (node (ref "U6") (pin "18") (pinfunction "SCS/D3_18") (pintype "bidirectional"))
    )
    (net (code "248") (name "/USBINT") (class "Default")
      (node (ref "P13") (pin "3") (pinfunction "3_3") (pintype "passive"))
      (node (ref "U28") (pin "51") (pinfunction "51_51") (pintype "passive"))
    )
    (net (code "249") (name "/USBSOMI") (class "Default")
      (node (ref "U28") (pin "82") (pinfunction "82_82") (pintype "passive"))
      (node (ref "U6") (pin "22") (pinfunction "SDO/D7_22") (pintype "bidirectional"))
    )
    (net (code "250") (name "/VBAT") (class "Default")
      (node (ref "BAT1") (pin "1") (pinfunction "VBATT_1") (pintype "passive"))
      (node (ref "C53") (pin "1") (pintype "passive"))
      (node (ref "CAP3") (pin "56") (pinfunction "56_56") (pintype "passive"))
    )
    (net (code "251") (name "/XADS1") (class "Default")
      (node (ref "U1") (pin "13") (pinfunction "~{CS}_13") (pintype "passive"))
      (node (ref "U28") (pin "50") (pinfunction "50_50") (pintype "passive"))
    )
    (net (code "252") (name "/XADS2") (class "Default")
      (node (ref "U2") (pin "13") (pinfunction "~{CS}_13") (pintype "passive"))
      (node (ref "U28") (pin "48") (pinfunction "48_48") (pintype "passive"))
    )
    (net (code "253") (name "/XCLKOUT") (class "Default")
      (node (ref "CAP3") (pin "53") (pinfunction "53_53") (pintype "passive"))
      (node (ref "U28") (pin "60") (pinfunction "60_60") (pintype "passive"))
    )
    (net (code "254") (name "/XDAC0") (class "Default")
      (node (ref "J9") (pin "1") (pinfunction "1_1") (pintype "passive"))
      (node (ref "R90") (pin "1") (pintype "passive"))
    )
    (net (code "255") (name "/XDAC1") (class "Default")
      (node (ref "J9") (pin "2") (pinfunction "2_2") (pintype "passive"))
      (node (ref "R111") (pin "1") (pintype "passive"))
    )
    (net (code "256") (name "/XDAC2") (class "Default")
      (node (ref "J9") (pin "3") (pinfunction "3_3") (pintype "passive"))
      (node (ref "R110") (pin "1") (pintype "passive"))
    )
    (net (code "257") (name "/XDAC3") (class "Default")
      (node (ref "J9") (pin "4") (pinfunction "4_4") (pintype "passive"))
      (node (ref "R89") (pin "1") (pintype "passive"))
    )
    (net (code "258") (name "/XDACS0") (class "Default")
      (node (ref "U25") (pin "10") (pinfunction "~{CS}_10") (pintype "passive"))
      (node (ref "U28") (pin "78") (pinfunction "78_78") (pintype "passive"))
    )
    (net (code "259") (name "/XDSPSOMI") (class "Default")
      (node (ref "P5") (pin "2") (pinfunction "2_2") (pintype "passive"))
      (node (ref "U13") (pin "5") (pinfunction "1B2_5") (pintype "bidirectional"))
    )
    (net (code "260") (name "/XHOLD") (class "Default")
      (node (ref "CAP3") (pin "45") (pinfunction "45_45") (pintype "passive"))
      (node (ref "EXTBUS") (pin "51") (pinfunction "51_51") (pintype "passive"))
      (node (ref "P17") (pin "2") (pinfunction "2_2") (pintype "passive"))
    )
    (net (code "261") (name "/XHOLDA") (class "Default")
      (node (ref "EXTBUS") (pin "52") (pinfunction "52_52") (pintype "passive"))
      (node (ref "P16") (pin "2") (pinfunction "2_2") (pintype "passive"))
    )
    (net (code "262") (name "/XI") (class "Default")
      (node (ref "U6") (pin "13") (pinfunction "XI_13") (pintype "input"))
      (node (ref "X2") (pin "1") (pintype "passive"))
    )
    (net (code "263") (name "/XINT1") (class "Default")
      (node (ref "EXTBUS") (pin "61") (pinfunction "61_61") (pintype "passive"))
      (node (ref "J10") (pin "16") (pinfunction "16_16") (pintype "passive"))
      (node (ref "P13") (pin "1") (pinfunction "1_1") (pintype "passive"))
    )
    (net (code "264") (name "/XINT2") (class "Default")
      (node (ref "J10") (pin "15") (pinfunction "15_15") (pintype "passive"))
      (node (ref "P14") (pin "1") (pinfunction "1_1") (pintype "passive"))
    )
    (net (code "265") (name "/XO") (class "Default")
      (node (ref "U6") (pin "14") (pinfunction "XO_14") (pintype "output"))
      (node (ref "X2") (pin "2") (pintype "passive"))
    )
    (net (code "266") (name "/XPWM1") (class "Default")
      (node (ref "J5") (pin "1") (pinfunction "1_1") (pintype "passive"))
      (node (ref "R1") (pin "1") (pintype "passive"))
      (node (ref "U3") (pin "3") (pinfunction "A1_3") (pintype "passive"))
    )
    (net (code "267") (name "/XPWM2") (class "Default")
      (node (ref "J5") (pin "3") (pinfunction "3_3") (pintype "passive"))
      (node (ref "R2") (pin "1") (pintype "passive"))
      (node (ref "U3") (pin "4") (pinfunction "A2_4") (pintype "passive"))
    )
    (net (code "268") (name "/XPWM3") (class "Default")
      (node (ref "J5") (pin "5") (pinfunction "5_5") (pintype "passive"))
      (node (ref "R3") (pin "1") (pintype "passive"))
      (node (ref "U3") (pin "5") (pinfunction "A3_5") (pintype "passive"))
    )
    (net (code "269") (name "/XPWM4") (class "Default")
      (node (ref "J5") (pin "2") (pinfunction "2_2") (pintype "passive"))
      (node (ref "R4") (pin "1") (pintype "passive"))
      (node (ref "U3") (pin "6") (pinfunction "A4_6") (pintype "passive"))
    )
    (net (code "270") (name "/XPWM5") (class "Default")
      (node (ref "J5") (pin "4") (pinfunction "4_4") (pintype "passive"))
      (node (ref "R5") (pin "1") (pintype "passive"))
      (node (ref "U3") (pin "7") (pinfunction "A5_7") (pintype "passive"))
    )
    (net (code "271") (name "/XPWM6") (class "Default")
      (node (ref "J5") (pin "6") (pinfunction "6_6") (pintype "passive"))
      (node (ref "R6") (pin "1") (pintype "passive"))
      (node (ref "U3") (pin "8") (pinfunction "A6_8") (pintype "passive"))
    )
    (net (code "272") (name "/XPWM7") (class "Default")
      (node (ref "J6") (pin "1") (pinfunction "1_1") (pintype "passive"))
      (node (ref "U4") (pin "3") (pinfunction "A1_3") (pintype "passive"))
    )
    (net (code "273") (name "/XPWM8") (class "Default")
      (node (ref "J6") (pin "2") (pinfunction "2_2") (pintype "passive"))
      (node (ref "U4") (pin "4") (pinfunction "A2_4") (pintype "passive"))
    )
    (net (code "274") (name "/XPWM9") (class "Default")
      (node (ref "J6") (pin "3") (pinfunction "3_3") (pintype "passive"))
      (node (ref "U4") (pin "5") (pinfunction "A3_5") (pintype "passive"))
    )
    (net (code "275") (name "/XPWM10") (class "Default")
      (node (ref "J6") (pin "4") (pinfunction "4_4") (pintype "passive"))
      (node (ref "U4") (pin "6") (pinfunction "A4_6") (pintype "passive"))
    )
    (net (code "276") (name "/XPWM11") (class "Default")
      (node (ref "J6") (pin "5") (pinfunction "5_5") (pintype "passive"))
      (node (ref "U4") (pin "7") (pinfunction "A5_7") (pintype "passive"))
    )
    (net (code "277") (name "/XPWM12") (class "Default")
      (node (ref "J6") (pin "6") (pinfunction "6_6") (pintype "passive"))
      (node (ref "U4") (pin "8") (pinfunction "A6_8") (pintype "passive"))
    )
    (net (code "278") (name "/XQEPA") (class "Default")
      (node (ref "J5") (pin "11") (pinfunction "11_11") (pintype "passive"))
      (node (ref "U28") (pin "120") (pinfunction "120_120") (pintype "passive"))
    )
    (net (code "279") (name "/XQEPB") (class "Default")
      (node (ref "J5") (pin "12") (pinfunction "12_12") (pintype "passive"))
      (node (ref "U28") (pin "119") (pinfunction "119_119") (pintype "passive"))
    )
    (net (code "280") (name "/XQEPI") (class "Default")
      (node (ref "J5") (pin "14") (pinfunction "14_14") (pintype "passive"))
      (node (ref "U28") (pin "121") (pinfunction "121_121") (pintype "passive"))
    )
    (net (code "281") (name "/XQEPS") (class "Default")
      (node (ref "J5") (pin "13") (pinfunction "13_13") (pintype "passive"))
      (node (ref "U28") (pin "124") (pinfunction "124_124") (pintype "passive"))
    )
    (net (code "282") (name "/XRD*") (class "Default")
      (node (ref "CAP3") (pin "39") (pinfunction "39_39") (pintype "passive"))
      (node (ref "J2") (pin "11") (pinfunction "11_11") (pintype "passive"))
      (node (ref "U1") (pin "12") (pinfunction "~{RD}/SCLK_12") (pintype "passive"))
      (node (ref "U2") (pin "12") (pinfunction "~{RD}/SCLK_12") (pintype "passive"))
      (node (ref "U28") (pin "53") (pinfunction "53_53") (pintype "passive"))
    )
    (net (code "283") (name "/XREADY") (class "Default")
      (node (ref "P15") (pin "2") (pinfunction "2_2") (pintype "passive"))
    )
    (net (code "284") (name "/XRS*") (class "Default")
      (node (ref "CAP3") (pin "55") (pinfunction "55_55") (pintype "passive"))
      (node (ref "U28") (pin "59") (pinfunction "59_59") (pintype "passive"))
    )
    (net (code "285") (name "/XSCL") (class "Default")
      (node (ref "P25") (pin "7") (pinfunction "7_7") (pintype "passive"))
      (node (ref "P5") (pin "5") (pinfunction "5_5") (pintype "passive"))
      (node (ref "R38") (pin "2") (pintype "passive"))
      (node (ref "U13") (pin "20") (pinfunction "2B4_20") (pintype "bidirectional"))
    )
    (net (code "286") (name "/XSDA") (class "Default")
      (node (ref "P25") (pin "8") (pinfunction "8_8") (pintype "passive"))
      (node (ref "P5") (pin "6") (pinfunction "6_6") (pintype "passive"))
      (node (ref "R37") (pin "2") (pintype "passive"))
      (node (ref "U13") (pin "23") (pinfunction "2B5_23") (pintype "bidirectional"))
    )
    (net (code "287") (name "/XSPICLK") (class "Default")
      (node (ref "P5") (pin "3") (pinfunction "3_3") (pintype "passive"))
      (node (ref "U13") (pin "6") (pinfunction "1B3_6") (pintype "bidirectional"))
    )
    (net (code "288") (name "/XSPISIMO") (class "Default")
      (node (ref "P5") (pin "1") (pinfunction "1_1") (pintype "passive"))
      (node (ref "U13") (pin "2") (pinfunction "1B1_2") (pintype "bidirectional"))
    )
    (net (code "289") (name "/XSPISTE") (class "Default")
      (node (ref "P5") (pin "4") (pinfunction "4_4") (pintype "passive"))
      (node (ref "U13") (pin "9") (pinfunction "1B4_9") (pintype "bidirectional"))
    )
    (net (code "290") (name "/XWE*") (class "Default")
      (node (ref "CAP3") (pin "40") (pinfunction "40_40") (pintype "passive"))
      (node (ref "J2") (pin "9") (pinfunction "9_9") (pintype "passive"))
      (node (ref "U25") (pin "11") (pinfunction "~{WR}_11") (pintype "passive"))
      (node (ref "U28") (pin "71") (pinfunction "71_71") (pintype "passive"))
    )
    (net (code "291") (name "/XZLG_RESET") (class "Default")
      (node (ref "P25") (pin "10") (pinfunction "10_10") (pintype "passive"))
      (node (ref "U13") (pin "19") (pinfunction "2B3_19") (pintype "bidirectional"))
    )
    (net (code "292") (name "/X_R{slash}W") (class "Default")
      (node (ref "P23") (pin "1") (pinfunction "1_1") (pintype "passive"))
    )
    (net (code "293") (name "/ZLG-INT") (class "Default")
      (node (ref "P25") (pin "9") (pinfunction "9_9") (pintype "passive"))
      (node (ref "U28") (pin "103") (pinfunction "103_103") (pintype "passive"))
    )
    (net (code "294") (name "/ZLGINT") (class "Default")
      (node (ref "P23") (pin "3") (pinfunction "3_3") (pintype "passive"))
      (node (ref "U28") (pin "33") (pinfunction "33_33") (pintype "passive"))
    )
    (net (code "295") (name "/ZLG_RESET") (class "Default")
      (node (ref "U13") (pin "18") (pinfunction "2A3_18") (pintype "bidirectional"))
      (node (ref "U28") (pin "111") (pinfunction "111_111") (pintype "passive"))
    )
    (net (code "296") (name "0") (class "Default")
      (node (ref "BAT1") (pin "2") (pinfunction "GND_2") (pintype "passive"))
      (node (ref "C1") (pin "2") (pinfunction "2_2") (pintype "passive"))
      (node (ref "C10") (pin "2") (pintype "passive"))
      (node (ref "C100") (pin "2") (pintype "passive"))
      (node (ref "C101") (pin "2") (pintype "passive"))
      (node (ref "C102") (pin "2") (pintype "passive"))
      (node (ref "C103") (pin "2") (pintype "passive"))
      (node (ref "C104") (pin "2") (pintype "passive"))
      (node (ref "C105") (pin "2") (pintype "passive"))
      (node (ref "C106") (pin "2") (pintype "passive"))
      (node (ref "C107") (pin "2") (pintype "passive"))
      (node (ref "C108") (pin "2") (pintype "passive"))
      (node (ref "C109") (pin "2") (pintype "passive"))
      (node (ref "C11") (pin "2") (pinfunction "2_2") (pintype "passive"))
      (node (ref "C110") (pin "2") (pintype "passive"))
      (node (ref "C111") (pin "2") (pinfunction "2_2") (pintype "passive"))
      (node (ref "C112") (pin "2") (pinfunction "2_2") (pintype "passive"))
      (node (ref "C113") (pin "2") (pinfunction "2_2") (pintype "passive"))
      (node (ref "C114") (pin "2") (pinfunction "2_2") (pintype "passive"))
      (node (ref "C115") (pin "2") (pinfunction "2_2") (pintype "passive"))
      (node (ref "C116") (pin "2") (pintype "passive"))
      (node (ref "C117") (pin "2") (pintype "passive"))
      (node (ref "C118") (pin "2") (pinfunction "2_2") (pintype "passive"))
      (node (ref "C119") (pin "2") (pintype "passive"))
      (node (ref "C12") (pin "2") (pinfunction "2_2") (pintype "passive"))
      (node (ref "C120") (pin "2") (pintype "passive"))
      (node (ref "C121") (pin "2") (pintype "passive"))
      (node (ref "C122") (pin "2") (pintype "passive"))
      (node (ref "C123") (pin "2") (pintype "passive"))
      (node (ref "C124") (pin "2") (pintype "passive"))
      (node (ref "C125") (pin "2") (pintype "passive"))
      (node (ref "C126") (pin "2") (pintype "passive"))
      (node (ref "C127") (pin "2") (pintype "passive"))
      (node (ref "C128") (pin "2") (pintype "passive"))
      (node (ref "C129") (pin "2") (pintype "passive"))
      (node (ref "C13") (pin "2") (pintype "passive"))
      (node (ref "C130") (pin "2") (pintype "passive"))
      (node (ref "C131") (pin "2") (pintype "passive"))
      (node (ref "C132") (pin "2") (pintype "passive"))
      (node (ref "C133") (pin "1") (pintype "passive"))
      (node (ref "C134") (pin "2") (pintype "passive"))
      (node (ref "C135") (pin "1") (pintype "passive"))
      (node (ref "C136") (pin "1") (pintype "passive"))
      (node (ref "C137") (pin "1") (pintype "passive"))
      (node (ref "C138") (pin "1") (pintype "passive"))
      (node (ref "C139") (pin "2") (pinfunction "2_2") (pintype "passive"))
      (node (ref "C14") (pin "2") (pintype "passive"))
      (node (ref "C140") (pin "2") (pinfunction "2_2") (pintype "passive"))
      (node (ref "C141") (pin "2") (pintype "passive"))
      (node (ref "C142") (pin "2") (pintype "passive"))
      (node (ref "C15") (pin "2") (pinfunction "2_2") (pintype "passive"))
      (node (ref "C16") (pin "2") (pinfunction "2_2") (pintype "passive"))
      (node (ref "C17") (pin "2") (pintype "passive"))
      (node (ref "C18") (pin "2") (pintype "passive"))
      (node (ref "C19") (pin "2") (pinfunction "2_2") (pintype "passive"))
      (node (ref "C2") (pin "2") (pintype "passive"))
      (node (ref "C20") (pin "2") (pinfunction "2_2") (pintype "passive"))
      (node (ref "C21") (pin "2") (pintype "passive"))
      (node (ref "C22") (pin "2") (pintype "passive"))
      (node (ref "C23") (pin "2") (pintype "passive"))
      (node (ref "C24") (pin "2") (pintype "passive"))
      (node (ref "C25") (pin "2") (pinfunction "2_2") (pintype "passive"))
      (node (ref "C26") (pin "2") (pinfunction "2_2") (pintype "passive"))
      (node (ref "C27") (pin "2") (pintype "passive"))
      (node (ref "C28") (pin "2") (pintype "passive"))
      (node (ref "C29") (pin "2") (pinfunction "2_2") (pintype "passive"))
      (node (ref "C3") (pin "2") (pinfunction "2_2") (pintype "passive"))
      (node (ref "C30") (pin "2") (pinfunction "2_2") (pintype "passive"))
      (node (ref "C31") (pin "2") (pinfunction "2_2") (pintype "passive"))
      (node (ref "C32") (pin "2") (pintype "passive"))
      (node (ref "C33") (pin "2") (pintype "passive"))
      (node (ref "C34") (pin "2") (pintype "passive"))
      (node (ref "C35") (pin "2") (pintype "passive"))
      (node (ref "C36") (pin "2") (pintype "passive"))
      (node (ref "C37") (pin "2") (pintype "passive"))
      (node (ref "C38") (pin "2") (pinfunction "2_2") (pintype "passive"))
      (node (ref "C39") (pin "2") (pinfunction "2_2") (pintype "passive"))
      (node (ref "C4") (pin "2") (pintype "passive"))
      (node (ref "C40") (pin "2") (pinfunction "2_2") (pintype "passive"))
      (node (ref "C41") (pin "2") (pinfunction "2_2") (pintype "passive"))
      (node (ref "C42") (pin "2") (pintype "passive"))
      (node (ref "C43") (pin "2") (pintype "passive"))
      (node (ref "C46") (pin "2") (pintype "passive"))
      (node (ref "C47") (pin "2") (pintype "passive"))
      (node (ref "C48") (pin "2") (pintype "passive"))
      (node (ref "C49") (pin "2") (pinfunction "2_2") (pintype "passive"))
      (node (ref "C5") (pin "2") (pintype "passive"))
      (node (ref "C50") (pin "2") (pinfunction "2_2") (pintype "passive"))
      (node (ref "C51") (pin "2") (pintype "passive"))
      (node (ref "C52") (pin "2") (pintype "passive"))
      (node (ref "C53") (pin "2") (pintype "passive"))
      (node (ref "C56") (pin "2") (pinfunction "2_2") (pintype "passive"))
      (node (ref "C57") (pin "2") (pintype "passive"))
      (node (ref "C58") (pin "2") (pintype "passive"))
      (node (ref "C6") (pin "2") (pintype "passive"))
      (node (ref "C60") (pin "2") (pintype "passive"))
      (node (ref "C61") (pin "2") (pintype "passive"))
      (node (ref "C62") (pin "2") (pintype "passive"))
      (node (ref "C63") (pin "2") (pinfunction "2_2") (pintype "passive"))
      (node (ref "C64") (pin "2") (pinfunction "2_2") (pintype "passive"))
      (node (ref "C65") (pin "2") (pintype "passive"))
      (node (ref "C66") (pin "2") (pintype "passive"))
      (node (ref "C67") (pin "2") (pintype "passive"))
      (node (ref "C68") (pin "2") (pintype "passive"))
      (node (ref "C69") (pin "2") (pintype "passive"))
      (node (ref "C7") (pin "2") (pintype "passive"))
      (node (ref "C70") (pin "2") (pintype "passive"))
      (node (ref "C71") (pin "2") (pintype "passive"))
      (node (ref "C72") (pin "2") (pintype "passive"))
      (node (ref "C73") (pin "2") (pintype "passive"))
      (node (ref "C74") (pin "2") (pintype "passive"))
      (node (ref "C75") (pin "2") (pintype "passive"))
      (node (ref "C76") (pin "2") (pinfunction "2_2") (pintype "passive"))
      (node (ref "C77") (pin "2") (pinfunction "2_2") (pintype "passive"))
      (node (ref "C78") (pin "2") (pinfunction "2_2") (pintype "passive"))
      (node (ref "C79") (pin "2") (pinfunction "2_2") (pintype "passive"))
      (node (ref "C8") (pin "2") (pinfunction "2_2") (pintype "passive"))
      (node (ref "C80") (pin "2") (pintype "passive"))
      (node (ref "C81") (pin "2") (pintype "passive"))
      (node (ref "C82") (pin "2") (pintype "passive"))
      (node (ref "C83") (pin "2") (pintype "passive"))
      (node (ref "C84") (pin "2") (pintype "passive"))
      (node (ref "C85") (pin "2") (pintype "passive"))
      (node (ref "C86") (pin "2") (pinfunction "2_2") (pintype "passive"))
      (node (ref "C87") (pin "2") (pintype "passive"))
      (node (ref "C88") (pin "2") (pintype "passive"))
      (node (ref "C89") (pin "2") (pintype "passive"))
      (node (ref "C9") (pin "2") (pinfunction "2_2") (pintype "passive"))
      (node (ref "C90") (pin "2") (pintype "passive"))
      (node (ref "C91") (pin "2") (pintype "passive"))
      (node (ref "C92") (pin "2") (pintype "passive"))
      (node (ref "C93") (pin "2") (pintype "passive"))
      (node (ref "C94") (pin "2") (pintype "passive"))
      (node (ref "C95") (pin "2") (pintype "passive"))
      (node (ref "C96") (pin "2") (pintype "passive"))
      (node (ref "C97") (pin "2") (pinfunction "2_2") (pintype "passive"))
      (node (ref "C98") (pin "2") (pintype "passive"))
      (node (ref "C99") (pin "2") (pintype "passive"))
      (node (ref "J11") (pin "1") (pinfunction "T_1") (pintype "input"))
      (node (ref "J11") (pin "3") (pinfunction "S_3") (pintype "power_in"))
      (node (ref "J4") (pin "1") (pinfunction "T_1") (pintype "input"))
      (node (ref "J4") (pin "3") (pinfunction "S_3") (pintype "power_in"))
      (node (ref "J9") (pin "5") (pinfunction "5_5") (pintype "passive"))
      (node (ref "P11") (pin "1") (pinfunction "1_1") (pintype "passive"))
      (node (ref "P12") (pin "1") (pinfunction "1_1") (pintype "passive"))
      (node (ref "P25") (pin "1") (pinfunction "1_1") (pintype "passive"))
      (node (ref "P25") (pin "2") (pinfunction "2_2") (pintype "passive"))
      (node (ref "P25") (pin "3") (pinfunction "3_3") (pintype "passive"))
      (node (ref "P3") (pin "4") (pintype "passive"))
      (node (ref "P3") (pin "5") (pintype "passive"))
      (node (ref "P3") (pin "6") (pintype "passive"))
      (node (ref "R10") (pin "1") (pinfunction "1_1") (pintype "passive"))
      (node (ref "R12") (pin "1") (pinfunction "1_1") (pintype "passive"))
      (node (ref "R127") (pin "2") (pintype "passive"))
      (node (ref "R128") (pin "2") (pintype "passive"))
      (node (ref "R129") (pin "2") (pintype "passive"))
      (node (ref "R13") (pin "1") (pinfunction "1_1") (pintype "passive"))
      (node (ref "R130") (pin "2") (pintype "passive"))
      (node (ref "R14") (pin "1") (pinfunction "1_1") (pintype "passive"))
      (node (ref "R17") (pin "1") (pinfunction "1_1") (pintype "passive"))
      (node (ref "R18") (pin "1") (pinfunction "1_1") (pintype "passive"))
      (node (ref "R19") (pin "1") (pinfunction "1_1") (pintype "passive"))
      (node (ref "R20") (pin "1") (pinfunction "1_1") (pintype "passive"))
      (node (ref "R21") (pin "1") (pinfunction "1_1") (pintype "passive"))
      (node (ref "R22") (pin "1") (pinfunction "1_1") (pintype "passive"))
      (node (ref "R39") (pin "2") (pintype "passive"))
      (node (ref "R40") (pin "2") (pintype "passive"))
      (node (ref "R44") (pin "1") (pintype "passive"))
      (node (ref "R45") (pin "1") (pintype "passive"))
      (node (ref "RL2") (pin "2") (pintype "passive"))
      (node (ref "RS232-1") (pin "1") (pinfunction "1_1") (pintype "passive"))
      (node (ref "RS232-2") (pin "1") (pinfunction "1_1") (pintype "passive"))
      (node (ref "TVS1") (pin "2") (pintype "passive"))
      (node (ref "TVS2") (pin "2") (pintype "passive"))
      (node (ref "U1") (pin "2") (pinfunction "AGND_2") (pintype "passive"))
      (node (ref "U1") (pin "26") (pinfunction "AGND_26") (pintype "passive"))
      (node (ref "U1") (pin "35") (pinfunction "AGND_35") (pintype "passive"))
      (node (ref "U1") (pin "40") (pinfunction "AGND_40") (pintype "passive"))
      (node (ref "U1") (pin "41") (pinfunction "AGND_41") (pintype "passive"))
      (node (ref "U1") (pin "43") (pinfunction "REFGND_43") (pintype "passive"))
      (node (ref "U1") (pin "46") (pinfunction "REFGND_46") (pintype "passive"))
      (node (ref "U1") (pin "47") (pinfunction "AGND_47") (pintype "passive"))
      (node (ref "U10") (pin "2") (pinfunction "GND_2") (pintype "passive"))
      (node (ref "U10") (pin "8") (pinfunction "RS_8") (pintype "passive"))
      (node (ref "U12") (pin "109") (pinfunction "GND_109") (pintype "passive"))
      (node (ref "U12") (pin "113") (pinfunction "TXD_113") (pintype "passive"))
      (node (ref "U12") (pin "16") (pinfunction "GND_16") (pintype "passive"))
      (node (ref "U12") (pin "17") (pinfunction "GND_17") (pintype "passive"))
      (node (ref "U12") (pin "2") (pinfunction "GND_2") (pintype "passive"))
      (node (ref "U12") (pin "22") (pinfunction "GND_22") (pintype "passive"))
      (node (ref "U12") (pin "27") (pinfunction "GND_27") (pintype "passive"))
      (node (ref "U12") (pin "29") (pinfunction "GND_29") (pintype "passive"))
      (node (ref "U12") (pin "4") (pinfunction "GND_4") (pintype "passive"))
      (node (ref "U12") (pin "55") (pinfunction "GND_55") (pintype "passive"))
      (node (ref "U12") (pin "64") (pinfunction "GND_64") (pintype "passive"))
      (node (ref "U12") (pin "65") (pinfunction "GND_65") (pintype "passive"))
      (node (ref "U12") (pin "71") (pinfunction "GND_71") (pintype "passive"))
      (node (ref "U12") (pin "9") (pinfunction "GND_9") (pintype "passive"))
      (node (ref "U13") (pin "1") (pinfunction "~{OE}1_1") (pintype "input"))
      (node (ref "U13") (pin "11") (pinfunction "1A5_11") (pintype "bidirectional"))
      (node (ref "U13") (pin "12") (pinfunction "GND_12") (pintype "power_in"))
      (node (ref "U13") (pin "13") (pinfunction "~{OE}2_13") (pintype "input"))
      (node (ref "U13") (pin "14") (pinfunction "2A1_14") (pintype "bidirectional"))
      (node (ref "U13") (pin "17") (pinfunction "2A2_17") (pintype "bidirectional"))
      (node (ref "U14") (pin "2") (pinfunction "GND_2") (pintype "power_in"))
      (node (ref "U14") (pin "5") (pinfunction "0V_5") (pintype "output"))
      (node (ref "U2") (pin "2") (pinfunction "AGND_2") (pintype "passive"))
      (node (ref "U2") (pin "26") (pinfunction "AGND_26") (pintype "passive"))
      (node (ref "U2") (pin "35") (pinfunction "AGND_35") (pintype "passive"))
      (node (ref "U2") (pin "40") (pinfunction "AGND_40") (pintype "passive"))
      (node (ref "U2") (pin "41") (pinfunction "AGND_41") (pintype "passive"))
      (node (ref "U2") (pin "43") (pinfunction "REFGND_43") (pintype "passive"))
      (node (ref "U2") (pin "46") (pinfunction "REFGND_46") (pintype "passive"))
      (node (ref "U2") (pin "47") (pinfunction "AGND_47") (pintype "passive"))
      (node (ref "U25") (pin "14") (pinfunction "~{LDAC}_14") (pintype "passive"))
      (node (ref "U25") (pin "9") (pinfunction "GND_9") (pintype "passive"))
      (node (ref "U28") (pin "108") (pinfunction "GND_108") (pintype "passive"))
      (node (ref "U28") (pin "114") (pinfunction "GND_114") (pintype "passive"))
      (node (ref "U28") (pin "123") (pinfunction "GND_123") (pintype "passive"))
      (node (ref "U28") (pin "144") (pinfunction "GND_144") (pintype "passive"))
      (node (ref "U28") (pin "18") (pinfunction "GND_18") (pintype "passive"))
      (node (ref "U28") (pin "29") (pinfunction "GND_29") (pintype "passive"))
      (node (ref "U28") (pin "36") (pinfunction "GND_36") (pintype "passive"))
      (node (ref "U28") (pin "47") (pinfunction "GND_47") (pintype "passive"))
      (node (ref "U28") (pin "62") (pinfunction "GND_62") (pintype "passive"))
      (node (ref "U28") (pin "72") (pinfunction "GND_72") (pintype "passive"))
      (node (ref "U28") (pin "89") (pinfunction "GND_89") (pintype "passive"))
      (node (ref "U28") (pin "90") (pinfunction "GND_90") (pintype "passive"))
      (node (ref "U28") (pin "99") (pinfunction "GND_99") (pintype "passive"))
      (node (ref "U3") (pin "11") (pinfunction "GND_11") (pintype "passive"))
      (node (ref "U3") (pin "12") (pinfunction "GND_12") (pintype "passive"))
      (node (ref "U3") (pin "13") (pinfunction "GND_13") (pintype "passive"))
      (node (ref "U3") (pin "2") (pinfunction "DIR_2") (pintype "input"))
      (node (ref "U3") (pin "22") (pinfunction "~{OE}_22") (pintype "input"))
      (node (ref "U4") (pin "11") (pinfunction "GND_11") (pintype "passive"))
      (node (ref "U4") (pin "12") (pinfunction "GND_12") (pintype "passive"))
      (node (ref "U4") (pin "13") (pinfunction "GND_13") (pintype "passive"))
      (node (ref "U4") (pin "2") (pinfunction "DIR_2") (pintype "input"))
      (node (ref "U4") (pin "22") (pinfunction "~{OE}_22") (pintype "input"))
      (node (ref "U5") (pin "4") (pinfunction "GND_4") (pintype "bidirectional"))
      (node (ref "U6") (pin "12") (pinfunction "GND_12") (pintype "power_in"))
      (node (ref "U6") (pin "3") (pinfunction "WR#_3") (pintype "input"))
      (node (ref "U6") (pin "4") (pinfunction "RD#_4") (pintype "input"))
      (node (ref "U7") (pin "1") (pinfunction "GND_1") (pintype "passive"))
      (node (ref "U8") (pin "5") (pinfunction "GND_5") (pintype "power_in"))
      (node (ref "U9") (pin "15") (pinfunction "GND_15") (pintype "passive"))
    )
    (net (code "297") (name "0V") (class "Default")
      (node (ref "CAP3") (pin "117") (pinfunction "117_117") (pintype "passive"))
      (node (ref "CAP3") (pin "118") (pinfunction "118_118") (pintype "passive"))
      (node (ref "CAP3") (pin "37") (pinfunction "37_37") (pintype "passive"))
      (node (ref "CAP3") (pin "38") (pinfunction "38_38") (pintype "passive"))
      (node (ref "CAP3") (pin "51") (pinfunction "51_51") (pintype "passive"))
      (node (ref "CAP3") (pin "59") (pinfunction "59_59") (pintype "passive"))
      (node (ref "CAP3") (pin "60") (pinfunction "60_60") (pintype "passive"))
      (node (ref "EXTBUS") (pin "1") (pinfunction "1_1") (pintype "passive"))
      (node (ref "EXTBUS") (pin "2") (pinfunction "2_2") (pintype "passive"))
      (node (ref "EXTBUS") (pin "23") (pinfunction "23_23") (pintype "passive"))
      (node (ref "EXTBUS") (pin "24") (pinfunction "24_24") (pintype "passive"))
      (node (ref "EXTBUS") (pin "41") (pinfunction "41_41") (pintype "passive"))
      (node (ref "EXTBUS") (pin "42") (pinfunction "42_42") (pintype "passive"))
      (node (ref "EXTBUS") (pin "43") (pinfunction "43_43") (pintype "passive"))
      (node (ref "EXTBUS") (pin "45") (pinfunction "45_45") (pintype "passive"))
      (node (ref "EXTBUS") (pin "53") (pinfunction "53_53") (pintype "passive"))
      (node (ref "EXTBUS") (pin "55") (pinfunction "55_55") (pintype "passive"))
      (node (ref "EXTBUS") (pin "56") (pinfunction "56_56") (pintype "passive"))
      (node (ref "EXTBUS") (pin "57") (pinfunction "57_57") (pintype "passive"))
      (node (ref "EXTBUS") (pin "58") (pinfunction "58_58") (pintype "passive"))
      (node (ref "EXTBUS") (pin "59") (pinfunction "59_59") (pintype "passive"))
      (node (ref "EXTBUS") (pin "60") (pinfunction "60_60") (pintype "passive"))
      (node (ref "EXTBUS") (pin "62") (pinfunction "62_62") (pintype "passive"))
      (node (ref "EXTBUS") (pin "63") (pinfunction "63_63") (pintype "passive"))
      (node (ref "EXTBUS") (pin "64") (pinfunction "64_64") (pintype "passive"))
      (node (ref "EXTBUS") (pin "69") (pinfunction "69_69") (pintype "passive"))
      (node (ref "EXTBUS") (pin "70") (pinfunction "70_70") (pintype "passive"))
      (node (ref "EXTBUS") (pin "75") (pinfunction "75_75") (pintype "passive"))
      (node (ref "EXTBUS") (pin "76") (pinfunction "76_76") (pintype "passive"))
      (node (ref "EXTBUS") (pin "77") (pinfunction "77_77") (pintype "passive"))
      (node (ref "EXTBUS") (pin "78") (pinfunction "78_78") (pintype "passive"))
      (node (ref "EXTBUS") (pin "79") (pinfunction "79_79") (pintype "passive"))
      (node (ref "EXTBUS") (pin "80") (pinfunction "80_80") (pintype "passive"))
      (node (ref "J10") (pin "20") (pinfunction "20_20") (pintype "passive"))
      (node (ref "J2") (pin "1") (pinfunction "1_1") (pintype "passive"))
      (node (ref "J3") (pin "1") (pinfunction "1_1") (pintype "passive"))
      (node (ref "J3") (pin "11") (pinfunction "11_11") (pintype "passive"))
      (node (ref "J3") (pin "39") (pinfunction "39_39") (pintype "passive"))
      (node (ref "J3") (pin "9") (pinfunction "9_9") (pintype "passive"))
      (node (ref "J7") (pin "5") (pinfunction "5_5") (pintype "passive"))
      (node (ref "J8") (pin "5") (pinfunction "5_5") (pintype "passive"))
      (node (ref "P5") (pin "7") (pinfunction "7_7") (pintype "passive"))
      (node (ref "P5") (pin "9") (pinfunction "9_9") (pintype "passive"))
      (node (ref "P9") (pin "2") (pinfunction "2_2") (pintype "passive"))
      (node (ref "U1") (pin "50") (pinfunction "V1GND_50") (pintype "power_in"))
      (node (ref "U1") (pin "52") (pinfunction "V2GND_52") (pintype "passive"))
      (node (ref "U1") (pin "54") (pinfunction "V3GND_54") (pintype "passive"))
      (node (ref "U1") (pin "56") (pinfunction "V4GND_56") (pintype "passive"))
      (node (ref "U1") (pin "58") (pinfunction "V5GND_58") (pintype "passive"))
      (node (ref "U1") (pin "60") (pinfunction "V6GND_60") (pintype "passive"))
      (node (ref "U1") (pin "62") (pinfunction "V7GND_62") (pintype "passive"))
      (node (ref "U1") (pin "64") (pinfunction "V8GND_64") (pintype "passive"))
      (node (ref "U2") (pin "50") (pinfunction "V1GND_50") (pintype "power_in"))
      (node (ref "U2") (pin "52") (pinfunction "V2GND_52") (pintype "passive"))
      (node (ref "U2") (pin "54") (pinfunction "V3GND_54") (pintype "passive"))
      (node (ref "U2") (pin "56") (pinfunction "V4GND_56") (pintype "passive"))
      (node (ref "U2") (pin "58") (pinfunction "V5GND_58") (pintype "passive"))
      (node (ref "U2") (pin "60") (pinfunction "V6GND_60") (pintype "passive"))
      (node (ref "U2") (pin "62") (pinfunction "V7GND_62") (pintype "passive"))
      (node (ref "U2") (pin "64") (pinfunction "V8GND_64") (pintype "passive"))
    )
    (net (code "298") (name "1.8V") (class "Default")
      (node (ref "U12") (pin "1") (pinfunction "VCC18_1") (pintype "passive"))
      (node (ref "U12") (pin "108") (pinfunction "VCC18_108") (pintype "passive"))
      (node (ref "U12") (pin "12") (pinfunction "VCC18_12") (pintype "passive"))
      (node (ref "U12") (pin "13") (pinfunction "VCC18_13") (pintype "passive"))
      (node (ref "U12") (pin "18") (pinfunction "VCC18_18") (pintype "passive"))
      (node (ref "U12") (pin "28") (pinfunction "VCC18_28") (pintype "passive"))
      (node (ref "U12") (pin "30") (pinfunction "VCC18_30") (pintype "passive"))
      (node (ref "U12") (pin "5") (pinfunction "VCC18_5") (pintype "passive"))
      (node (ref "U12") (pin "54") (pinfunction "VCC18_54") (pintype "passive"))
      (node (ref "U12") (pin "82") (pinfunction "VCC18_82") (pintype "passive"))
    )
    (net (code "299") (name "1V8") (class "Default")
      (node (ref "C130") (pin "1") (pintype "passive"))
      (node (ref "C131") (pin "1") (pintype "passive"))
      (node (ref "C132") (pin "1") (pintype "passive"))
      (node (ref "C90") (pin "1") (pintype "passive"))
      (node (ref "C91") (pin "1") (pintype "passive"))
      (node (ref "C92") (pin "1") (pintype "passive"))
      (node (ref "C93") (pin "1") (pintype "passive"))
      (node (ref "C94") (pin "1") (pintype "passive"))
      (node (ref "C95") (pin "1") (pintype "passive"))
      (node (ref "C96") (pin "1") (pintype "passive"))
      (node (ref "U7") (pin "2") (pinfunction "VOUT_2") (pintype "passive"))
    )
    (net (code "300") (name "3.3V") (class "Default")
      (node (ref "C100") (pin "1") (pintype "passive"))
      (node (ref "C101") (pin "1") (pintype "passive"))
      (node (ref "C102") (pin "1") (pintype "passive"))
      (node (ref "C103") (pin "1") (pintype "passive"))
      (node (ref "C104") (pin "1") (pintype "passive"))
      (node (ref "C105") (pin "1") (pintype "passive"))
      (node (ref "C106") (pin "1") (pintype "passive"))
      (node (ref "C107") (pin "1") (pintype "passive"))
      (node (ref "C108") (pin "1") (pintype "passive"))
      (node (ref "C109") (pin "1") (pintype "passive"))
      (node (ref "C110") (pin "1") (pintype "passive"))
      (node (ref "C111") (pin "1") (pinfunction "1_1") (pintype "passive"))
      (node (ref "C112") (pin "1") (pinfunction "1_1") (pintype "passive"))
      (node (ref "C113") (pin "1") (pinfunction "1_1") (pintype "passive"))
      (node (ref "C114") (pin "1") (pinfunction "1_1") (pintype "passive"))
      (node (ref "C115") (pin "1") (pinfunction "1_1") (pintype "passive"))
      (node (ref "C116") (pin "1") (pintype "passive"))
      (node (ref "C119") (pin "1") (pintype "passive"))
      (node (ref "C120") (pin "1") (pintype "passive"))
      (node (ref "C121") (pin "1") (pintype "passive"))
      (node (ref "C122") (pin "1") (pintype "passive"))
      (node (ref "C123") (pin "1") (pintype "passive"))
      (node (ref "C124") (pin "1") (pintype "passive"))
      (node (ref "C125") (pin "1") (pintype "passive"))
      (node (ref "C126") (pin "1") (pintype "passive"))
      (node (ref "C127") (pin "1") (pintype "passive"))
      (node (ref "C128") (pin "1") (pintype "passive"))
      (node (ref "C135") (pin "2") (pintype "passive"))
      (node (ref "C136") (pin "2") (pintype "passive"))
      (node (ref "C23") (pin "1") (pintype "passive"))
      (node (ref "C24") (pin "1") (pintype "passive"))
      (node (ref "C54") (pin "1") (pinfunction "1_1") (pintype "passive"))
      (node (ref "C55") (pin "1") (pintype "passive"))
      (node (ref "C60") (pin "1") (pintype "passive"))
      (node (ref "C61") (pin "1") (pintype "passive"))
      (node (ref "C62") (pin "1") (pintype "passive"))
      (node (ref "C80") (pin "1") (pintype "passive"))
      (node (ref "C81") (pin "1") (pintype "passive"))
      (node (ref "C82") (pin "1") (pintype "passive"))
      (node (ref "C83") (pin "1") (pintype "passive"))
      (node (ref "C84") (pin "1") (pintype "passive"))
      (node (ref "C85") (pin "1") (pintype "passive"))
      (node (ref "C86") (pin "1") (pinfunction "1_1") (pintype "passive"))
      (node (ref "C87") (pin "1") (pintype "passive"))
      (node (ref "C88") (pin "1") (pintype "passive"))
      (node (ref "C89") (pin "1") (pintype "passive"))
      (node (ref "C97") (pin "1") (pinfunction "1_1") (pintype "passive"))
      (node (ref "C98") (pin "1") (pintype "passive"))
      (node (ref "C99") (pin "1") (pintype "passive"))
      (node (ref "CAP3") (pin "115") (pinfunction "115_115") (pintype "passive"))
      (node (ref "CAP3") (pin "116") (pinfunction "116_116") (pintype "passive"))
      (node (ref "CAP3") (pin "57") (pinfunction "57_57") (pintype "passive"))
      (node (ref "D1") (pin "1") (pintype "passive"))
      (node (ref "D10") (pin "1") (pintype "passive"))
      (node (ref "D2") (pin "1") (pintype "passive"))
      (node (ref "D3") (pin "1") (pintype "passive"))
      (node (ref "D4") (pin "1") (pintype "passive"))
      (node (ref "D5") (pin "1") (pintype "passive"))
      (node (ref "D6") (pin "1") (pintype "passive"))
      (node (ref "D7") (pin "1") (pintype "passive"))
      (node (ref "D8") (pin "1") (pintype "passive"))
      (node (ref "EXTBUS") (pin "65") (pinfunction "65_65") (pintype "passive"))
      (node (ref "EXTBUS") (pin "66") (pinfunction "66_66") (pintype "passive"))
      (node (ref "EXTBUS") (pin "67") (pinfunction "67_67") (pintype "passive"))
      (node (ref "EXTBUS") (pin "68") (pinfunction "68_68") (pintype "passive"))
      (node (ref "J10") (pin "17") (pinfunction "17_17") (pintype "passive"))
      (node (ref "J10") (pin "19") (pinfunction "19_19") (pintype "passive"))
      (node (ref "J2") (pin "3") (pinfunction "3_3") (pintype "passive"))
      (node (ref "LED2") (pin "1") (pintype "passive"))
      (node (ref "LED3") (pin "1") (pintype "passive"))
      (node (ref "LED4") (pin "1") (pintype "passive"))
      (node (ref "P11") (pin "3") (pinfunction "3_3") (pintype "passive"))
      (node (ref "P12") (pin "3") (pinfunction "3_3") (pintype "passive"))
      (node (ref "P9") (pin "1") (pinfunction "1_1") (pintype "passive"))
      (node (ref "R15") (pin "1") (pinfunction "1_1") (pintype "passive"))
      (node (ref "R16") (pin "1") (pinfunction "1_1") (pintype "passive"))
      (node (ref "R28") (pin "1") (pintype "passive"))
      (node (ref "R33") (pin "2") (pintype "passive"))
      (node (ref "R34") (pin "2") (pintype "passive"))
      (node (ref "R35") (pin "1") (pintype "passive"))
      (node (ref "R36") (pin "1") (pintype "passive"))
      (node (ref "R42") (pin "2") (pintype "passive"))
      (node (ref "R43") (pin "2") (pintype "passive"))
      (node (ref "U1") (pin "23") (pinfunction "VDRIVE_23") (pintype "passive"))
      (node (ref "U10") (pin "3") (pinfunction "VCC_3") (pintype "passive"))
      (node (ref "U11") (pin "2") (pinfunction "TD_2") (pintype "passive"))
      (node (ref "U11") (pin "5") (pinfunction "CTD_5") (pintype "passive"))
      (node (ref "U11") (pin "7") (pinfunction "RD_7") (pintype "passive"))
      (node (ref "U12") (pin "101") (pinfunction "VCC33_101") (pintype "passive"))
      (node (ref "U12") (pin "122") (pinfunction "VCC33_122") (pintype "passive"))
      (node (ref "U12") (pin "21") (pinfunction "VCC33_21") (pintype "passive"))
      (node (ref "U12") (pin "26") (pinfunction "VCC33_26") (pintype "passive"))
      (node (ref "U12") (pin "39") (pinfunction "VCC33_39") (pintype "passive"))
      (node (ref "U12") (pin "56") (pinfunction "VCC33_56") (pintype "passive"))
      (node (ref "U12") (pin "7") (pinfunction "VCC33_7") (pintype "passive"))
      (node (ref "U12") (pin "70") (pinfunction "VCC33_70") (pintype "passive"))
      (node (ref "U12") (pin "72") (pinfunction "VCC33_72") (pintype "passive"))
      (node (ref "U12") (pin "83") (pinfunction "VCC33_83") (pintype "passive"))
      (node (ref "U12") (pin "92") (pinfunction "VCC33_92") (pintype "passive"))
      (node (ref "U15") (pin "2") (pinfunction "OUT_2") (pintype "power_in"))
      (node (ref "U15") (pin "4") (pinfunction "TAB_4") (pintype "power_in"))
      (node (ref "U2") (pin "23") (pinfunction "VDRIVE_23") (pintype "passive"))
      (node (ref "U25") (pin "15") (pinfunction "~{PD}_15") (pintype "passive"))
      (node (ref "U25") (pin "16") (pinfunction "VDD_16") (pintype "passive"))
      (node (ref "U28") (pin "1") (pinfunction "VccIO_1") (pintype "passive"))
      (node (ref "U28") (pin "109") (pinfunction "VccIO_109") (pintype "passive"))
      (node (ref "U28") (pin "127") (pinfunction "VccIO_127") (pintype "passive"))
      (node (ref "U28") (pin "141") (pinfunction "VccINT_141") (pintype "passive"))
      (node (ref "U28") (pin "37") (pinfunction "VccIO_37") (pintype "passive"))
      (node (ref "U28") (pin "42") (pinfunction "VccINT_42") (pintype "passive"))
      (node (ref "U28") (pin "55") (pinfunction "VccIO_55") (pintype "passive"))
      (node (ref "U28") (pin "73") (pinfunction "VccIO_73") (pintype "passive"))
      (node (ref "U28") (pin "8") (pinfunction "VccINT_8") (pintype "passive"))
      (node (ref "U28") (pin "84") (pinfunction "VccINT_84") (pintype "passive"))
      (node (ref "U3") (pin "23") (pinfunction "VCCB_23") (pintype "passive"))
      (node (ref "U3") (pin "24") (pinfunction "VCCB_24") (pintype "passive"))
      (node (ref "U4") (pin "23") (pinfunction "VCCB_23") (pintype "passive"))
      (node (ref "U4") (pin "24") (pinfunction "VCCB_24") (pintype "passive"))
      (node (ref "U6") (pin "28") (pinfunction "VCC_28") (pintype "power_in"))
      (node (ref "U6") (pin "9") (pinfunction "V3_9") (pintype "power_in"))
      (node (ref "U7") (pin "3") (pinfunction "VIN_3") (pintype "passive"))
      (node (ref "U9") (pin "16") (pinfunction "Vcc_16") (pintype "passive"))
    )
    (net (code "301") (name "5V") (class "Default")
      (node (ref "C49") (pin "1") (pinfunction "1_1") (pintype "passive"))
      (node (ref "C50") (pin "1") (pinfunction "1_1") (pintype "passive"))
      (node (ref "C51") (pin "1") (pintype "passive"))
      (node (ref "C52") (pin "1") (pintype "passive"))
      (node (ref "CAP3") (pin "119") (pinfunction "119_119") (pintype "passive"))
      (node (ref "CAP3") (pin "120") (pinfunction "120_120") (pintype "passive"))
      (node (ref "CAP3") (pin "58") (pinfunction "58_58") (pintype "passive"))
      (node (ref "EXTBUS") (pin "71") (pinfunction "71_71") (pintype "passive"))
      (node (ref "EXTBUS") (pin "72") (pinfunction "72_72") (pintype "passive"))
      (node (ref "EXTBUS") (pin "73") (pinfunction "73_73") (pintype "passive"))
      (node (ref "EXTBUS") (pin "74") (pinfunction "74_74") (pintype "passive"))
      (node (ref "J3") (pin "3") (pinfunction "3_3") (pintype "passive"))
      (node (ref "J3") (pin "37") (pinfunction "37_37") (pintype "passive"))
      (node (ref "J7") (pin "1") (pinfunction "1_1") (pintype "passive"))
      (node (ref "J8") (pin "1") (pinfunction "1_1") (pintype "passive"))
      (node (ref "L3") (pin "2") (pinfunction "2_2") (pintype "passive"))
      (node (ref "P5") (pin "10") (pinfunction "10_10") (pintype "passive"))
      (node (ref "P5") (pin "8") (pinfunction "8_8") (pintype "passive"))
      (node (ref "U8") (pin "8") (pinfunction "VCC_8") (pintype "power_in"))
    )
    (net (code "302") (name "5V-LCD") (class "Default")
      (node (ref "C139") (pin "1") (pinfunction "1_1") (pintype "passive"))
      (node (ref "C140") (pin "1") (pinfunction "1_1") (pintype "passive"))
      (node (ref "C141") (pin "1") (pintype "passive"))
      (node (ref "C142") (pin "1") (pintype "passive"))
      (node (ref "J2") (pin "35") (pinfunction "35_35") (pintype "passive"))
      (node (ref "L4") (pin "2") (pinfunction "2_2") (pintype "passive"))
    )
    (net (code "303") (name "Net-(B1-Pad1)") (class "Default")
      (node (ref "B1") (pin "1") (pinfunction "1_1") (pintype "passive"))
      (node (ref "U8") (pin "6") (pintype "bidirectional"))
    )
    (net (code "304") (name "Net-(B2-Pad1)") (class "Default")
      (node (ref "B2") (pin "1") (pinfunction "1_1") (pintype "passive"))
      (node (ref "R23") (pin "2") (pintype "passive"))
      (node (ref "R25") (pin "2") (pintype "passive"))
      (node (ref "TVS2") (pin "1") (pintype "passive"))
      (node (ref "U8") (pin "7") (pintype "bidirectional"))
    )
    (net (code "305") (name "Net-(C15-Pad1)") (class "Default")
      (node (ref "C15") (pin "1") (pinfunction "1_1") (pintype "passive"))
      (node (ref "C17") (pin "1") (pintype "passive"))
      (node (ref "U2") (pin "36") (pinfunction "REGCAP_36") (pintype "passive"))
    )
    (net (code "306") (name "Net-(C16-Pad1)") (class "Default")
      (node (ref "C16") (pin "1") (pinfunction "1_1") (pintype "passive"))
      (node (ref "C18") (pin "1") (pintype "passive"))
      (node (ref "U2") (pin "39") (pinfunction "REGCAP_39") (pintype "passive"))
    )
    (net (code "307") (name "Net-(C19-Pad1)") (class "Default")
      (node (ref "C19") (pin "1") (pinfunction "1_1") (pintype "passive"))
      (node (ref "C21") (pin "1") (pintype "passive"))
      (node (ref "U1") (pin "36") (pinfunction "REGCAP_36") (pintype "passive"))
    )
    (net (code "308") (name "Net-(C20-Pad1)") (class "Default")
      (node (ref "C20") (pin "1") (pinfunction "1_1") (pintype "passive"))
      (node (ref "C22") (pin "1") (pintype "passive"))
      (node (ref "U1") (pin "39") (pinfunction "REGCAP_39") (pintype "passive"))
    )
    (net (code "309") (name "Net-(C58-Pad1)") (class "Default")
      (node (ref "C58") (pin "1") (pintype "passive"))
      (node (ref "P3") (pin "1") (pintype "passive"))
      (node (ref "R27") (pin "1") (pintype "passive"))
    )
    (net (code "310") (name "Net-(C134-Pad1)") (class "Default")
      (node (ref "C134") (pin "1") (pintype "passive"))
      (node (ref "R29") (pin "1") (pintype "passive"))
      (node (ref "R30") (pin "1") (pintype "passive"))
      (node (ref "R31") (pin "1") (pintype "passive"))
    )
    (net (code "311") (name "Net-(D1-Pad2)") (class "Default")
      (node (ref "D1") (pin "2") (pintype "passive"))
      (node (ref "R1") (pin "2") (pintype "passive"))
    )
    (net (code "312") (name "Net-(D2-Pad2)") (class "Default")
      (node (ref "D2") (pin "2") (pintype "passive"))
      (node (ref "R2") (pin "2") (pintype "passive"))
    )
    (net (code "313") (name "Net-(D3-Pad2)") (class "Default")
      (node (ref "D3") (pin "2") (pintype "passive"))
      (node (ref "R3") (pin "2") (pintype "passive"))
    )
    (net (code "314") (name "Net-(D4-Pad2)") (class "Default")
      (node (ref "D4") (pin "2") (pintype "passive"))
      (node (ref "R4") (pin "2") (pintype "passive"))
    )
    (net (code "315") (name "Net-(D5-Pad2)") (class "Default")
      (node (ref "D5") (pin "2") (pintype "passive"))
      (node (ref "R5") (pin "2") (pintype "passive"))
    )
    (net (code "316") (name "Net-(D6-Pad2)") (class "Default")
      (node (ref "D6") (pin "2") (pintype "passive"))
      (node (ref "R6") (pin "2") (pintype "passive"))
    )
    (net (code "317") (name "Net-(D7-Pad2)") (class "Default")
      (node (ref "D7") (pin "2") (pintype "passive"))
      (node (ref "R7") (pin "2") (pintype "passive"))
    )
    (net (code "318") (name "Net-(D8-Pad2)") (class "Default")
      (node (ref "D8") (pin "2") (pintype "passive"))
      (node (ref "R8") (pin "2") (pintype "passive"))
    )
    (net (code "319") (name "Net-(D9-Pad2)") (class "Default")
      (node (ref "D9") (pin "2") (pintype "passive"))
      (node (ref "R39") (pin "1") (pintype "passive"))
    )
    (net (code "320") (name "Net-(D10-Pad2)") (class "Default")
      (node (ref "D10") (pin "2") (pintype "passive"))
      (node (ref "R40") (pin "1") (pintype "passive"))
    )
    (net (code "321") (name "Net-(J3-Pad35)") (class "Default")
      (node (ref "J3") (pin "35") (pinfunction "35_35") (pintype "passive"))
      (node (ref "RL1") (pin "2") (pintype "passive"))
      (node (ref "RL2") (pin "1") (pintype "passive"))
    )
    (net (code "322") (name "Net-(J4-R)") (class "Default")
      (node (ref "J4") (pin "2") (pinfunction "R_2") (pintype "input"))
      (node (ref "L3") (pin "1") (pinfunction "1_1") (pintype "passive"))
    )
    (net (code "323") (name "Net-(J11-R)") (class "Default")
      (node (ref "J11") (pin "2") (pinfunction "R_2") (pintype "input"))
      (node (ref "L4") (pin "1") (pinfunction "1_1") (pintype "passive"))
    )
    (net (code "324") (name "Net-(LED1-Pad1)") (class "Default")
      (node (ref "LED1") (pin "1") (pintype "passive"))
      (node (ref "R28") (pin "2") (pintype "passive"))
    )
    (net (code "325") (name "Net-(LED2-Pad2)") (class "Default")
      (node (ref "LED2") (pin "2") (pintype "passive"))
      (node (ref "R45") (pin "2") (pintype "passive"))
    )
    (net (code "326") (name "Net-(LED3-Pad2)") (class "Default")
      (node (ref "LED3") (pin "2") (pintype "passive"))
      (node (ref "R46") (pin "2") (pintype "passive"))
    )
    (net (code "327") (name "Net-(LED4-Pad2)") (class "Default")
      (node (ref "LED4") (pin "2") (pintype "passive"))
      (node (ref "R47") (pin "2") (pintype "passive"))
    )
    (net (code "328") (name "Net-(P4-NC-Pad4)") (class "Default")
      (node (ref "P4") (pin "4") (pinfunction "NC_4") (pintype "passive"))
      (node (ref "P4") (pin "5") (pinfunction "NC_5") (pintype "passive"))
      (node (ref "R30") (pin "2") (pintype "passive"))
    )
    (net (code "329") (name "Net-(P4-NC-Pad7)") (class "Default")
      (node (ref "P4") (pin "7") (pinfunction "NC_7") (pintype "passive"))
      (node (ref "P4") (pin "8") (pinfunction "NC_8") (pintype "passive"))
      (node (ref "R29") (pin "2") (pintype "passive"))
    )
    (net (code "330") (name "Net-(P4-RX+)") (class "Default")
      (node (ref "P4") (pin "3") (pinfunction "RX+_3") (pintype "passive"))
      (node (ref "U11") (pin "11") (pinfunction "RXP_11") (pintype "passive"))
    )
    (net (code "331") (name "Net-(P4-RX-)") (class "Default")
      (node (ref "P4") (pin "6") (pinfunction "RX-_6") (pintype "passive"))
      (node (ref "U11") (pin "9") (pinfunction "RXN_9") (pintype "passive"))
    )
    (net (code "332") (name "Net-(P4-TX+)") (class "Default")
      (node (ref "P4") (pin "1") (pinfunction "TX+_1") (pintype "passive"))
      (node (ref "U11") (pin "16") (pinfunction "TXP_16") (pintype "passive"))
    )
    (net (code "333") (name "Net-(P4-TX-)") (class "Default")
      (node (ref "P4") (pin "2") (pinfunction "TX-_2") (pintype "passive"))
      (node (ref "U11") (pin "14") (pinfunction "TXN_14") (pintype "passive"))
    )
    (net (code "334") (name "Net-(P11-Pad2)") (class "Default")
      (node (ref "P11") (pin "2") (pinfunction "2_2") (pintype "passive"))
      (node (ref "R11") (pin "1") (pinfunction "1_1") (pintype "passive"))
    )
    (net (code "335") (name "Net-(P12-Pad2)") (class "Default")
      (node (ref "P12") (pin "2") (pinfunction "2_2") (pintype "passive"))
      (node (ref "R9") (pin "1") (pinfunction "1_1") (pintype "passive"))
    )
    (net (code "336") (name "Net-(R23-Pad1)") (class "Default")
      (node (ref "R23") (pin "1") (pintype "passive"))
      (node (ref "R24") (pin "2") (pintype "passive"))
      (node (ref "TVS1") (pin "1") (pintype "passive"))
    )
    (net (code "337") (name "Net-(R110-Pad2)") (class "Default")
      (node (ref "R110") (pin "2") (pintype "passive"))
      (node (ref "R176") (pin "1") (pintype "passive"))
      (node (ref "U33") (pin "1") (pintype "passive"))
    )
    (net (code "338") (name "Net-(R111-Pad2)") (class "Default")
      (node (ref "R111") (pin "2") (pintype "passive"))
      (node (ref "R177") (pin "1") (pintype "passive"))
      (node (ref "U33B") (pin "1") (pintype "passive"))
    )
    (net (code "339") (name "Net-(R127-Pad1)") (class "Default")
      (node (ref "R127") (pin "1") (pintype "passive"))
      (node (ref "R174") (pin "2") (pintype "passive"))
      (node (ref "R178") (pin "1") (pintype "passive"))
      (node (ref "U31") (pin "3") (pintype "passive"))
    )
    (net (code "340") (name "Net-(R128-Pad1)") (class "Default")
      (node (ref "R128") (pin "1") (pintype "passive"))
      (node (ref "R175") (pin "2") (pintype "passive"))
      (node (ref "R179") (pin "1") (pintype "passive"))
      (node (ref "U31B") (pin "3") (pintype "passive"))
    )
    (net (code "341") (name "Net-(R129-Pad1)") (class "Default")
      (node (ref "R129") (pin "1") (pintype "passive"))
      (node (ref "R176") (pin "2") (pintype "passive"))
      (node (ref "R180") (pin "1") (pintype "passive"))
      (node (ref "U33") (pin "3") (pintype "passive"))
    )
    (net (code "342") (name "Net-(R130-Pad1)") (class "Default")
      (node (ref "R130") (pin "1") (pintype "passive"))
      (node (ref "R177") (pin "2") (pintype "passive"))
      (node (ref "R181") (pin "1") (pintype "passive"))
      (node (ref "U33B") (pin "3") (pintype "passive"))
    )
    (net (code "343") (name "Net-(R174-Pad1)") (class "Default")
      (node (ref "R174") (pin "1") (pintype "passive"))
      (node (ref "R89") (pin "2") (pintype "passive"))
      (node (ref "U31") (pin "1") (pintype "passive"))
    )
    (net (code "344") (name "Net-(R175-Pad1)") (class "Default")
      (node (ref "R175") (pin "1") (pintype "passive"))
      (node (ref "R90") (pin "2") (pintype "passive"))
      (node (ref "U31B") (pin "1") (pintype "passive"))
    )
    (net (code "345") (name "Net-(R183-Pad1)") (class "Default")
      (node (ref "R183") (pin "1") (pintype "passive"))
      (node (ref "U31") (pin "2") (pintype "passive"))
    )
    (net (code "346") (name "Net-(R184-Pad1)") (class "Default")
      (node (ref "R184") (pin "1") (pintype "passive"))
      (node (ref "U31B") (pin "2") (pintype "passive"))
    )
    (net (code "347") (name "Net-(R185-Pad1)") (class "Default")
      (node (ref "R185") (pin "1") (pintype "passive"))
      (node (ref "U33") (pin "2") (pintype "passive"))
    )
    (net (code "348") (name "Net-(R186-Pad1)") (class "Default")
      (node (ref "R186") (pin "1") (pintype "passive"))
      (node (ref "U33B") (pin "2") (pintype "passive"))
    )
    (net (code "349") (name "Net-(U9-C1+)") (class "Default")
      (node (ref "C44") (pin "2") (pintype "passive"))
      (node (ref "U9") (pin "1") (pinfunction "C1+_1") (pintype "passive"))
    )
    (net (code "350") (name "Net-(U9-C1-)") (class "Default")
      (node (ref "C44") (pin "1") (pintype "passive"))
      (node (ref "U9") (pin "3") (pinfunction "C1-_3") (pintype "passive"))
    )
    (net (code "351") (name "Net-(U9-C2+)") (class "Default")
      (node (ref "C45") (pin "2") (pintype "passive"))
      (node (ref "U9") (pin "4") (pinfunction "C2+_4") (pintype "passive"))
    )
    (net (code "352") (name "Net-(U9-C2-)") (class "Default")
      (node (ref "C45") (pin "1") (pintype "passive"))
      (node (ref "U9") (pin "5") (pinfunction "C2-_5") (pintype "passive"))
    )
    (net (code "353") (name "Net-(U9-R1in)") (class "Default")
      (node (ref "R32") (pin "2") (pintype "passive"))
      (node (ref "RS232-1") (pin "4") (pinfunction "4_4") (pintype "passive"))
      (node (ref "U9") (pin "13") (pinfunction "R1in_13") (pintype "passive"))
    )
    (net (code "354") (name "Net-(U9-R2in)") (class "Default")
      (node (ref "RS232-2") (pin "4") (pinfunction "4_4") (pintype "passive"))
      (node (ref "U9") (pin "8") (pinfunction "R2in_8") (pintype "passive"))
    )
    (net (code "355") (name "Net-(U9-T1out)") (class "Default")
      (node (ref "RS232-1") (pin "3") (pinfunction "3_3") (pintype "passive"))
      (node (ref "U9") (pin "14") (pinfunction "T1out_14") (pintype "passive"))
    )
    (net (code "356") (name "Net-(U9-T2out)") (class "Default")
      (node (ref "RS232-2") (pin "3") (pinfunction "3_3") (pintype "passive"))
      (node (ref "U9") (pin "7") (pinfunction "T2out_7") (pintype "passive"))
    )
    (net (code "357") (name "Net-(U9-V+)") (class "Default")
      (node (ref "C43") (pin "1") (pintype "passive"))
      (node (ref "U9") (pin "2") (pinfunction "V+_2") (pintype "passive"))
    )
    (net (code "358") (name "Net-(U9-V-)") (class "Default")
      (node (ref "C46") (pin "1") (pintype "passive"))
      (node (ref "R32") (pin "1") (pintype "passive"))
      (node (ref "U9") (pin "6") (pinfunction "V-_6") (pintype "passive"))
    )
    (net (code "359") (name "Net-(U11-CTX)") (class "Default")
      (node (ref "R31") (pin "2") (pintype "passive"))
      (node (ref "U11") (pin "10") (pinfunction "RX_10") (pintype "passive"))
      (node (ref "U11") (pin "13") (pinfunction "CTX_13") (pintype "passive"))
      (node (ref "U11") (pin "15") (pinfunction "TX_15") (pintype "passive"))
    )
    (net (code "360") (name "Net-(U12-RESTE)") (class "Default")
      (node (ref "R44") (pin "2") (pintype "passive"))
      (node (ref "U12") (pin "6") (pinfunction "RESTE_6") (pintype "passive"))
    )
    (net (code "361") (name "Net-(U12-XI)") (class "Default")
      (node (ref "C138") (pin "2") (pintype "passive"))
      (node (ref "U12") (pin "19") (pinfunction "XI_19") (pintype "passive"))
      (node (ref "X1") (pin "1") (pintype "passive"))
    )
    (net (code "362") (name "Net-(U12-XO)") (class "Default")
      (node (ref "C137") (pin "2") (pintype "passive"))
      (node (ref "U12") (pin "20") (pinfunction "XO_20") (pintype "passive"))
      (node (ref "X1") (pin "2") (pintype "passive"))
    )
    (net (code "363") (name "Net-(U14-VIN)") (class "Default")
      (node (ref "L24.7uH") (pin "2") (pinfunction "2_2") (pintype "passive"))
      (node (ref "U14") (pin "1") (pinfunction "VIN_1") (pintype "power_in"))
    )
    (net (code "364") (name "Net-(U15-GND)") (class "Default")
      (node (ref "C54") (pin "2") (pinfunction "2_2") (pintype "passive"))
      (node (ref "C55") (pin "2") (pintype "passive"))
      (node (ref "U15") (pin "1") (pinfunction "GND_1") (pintype "power_in"))
    )
    (net (code "365") (name "VCC") (class "Default")
      (node (ref "C25") (pin "1") (pinfunction "1_1") (pintype "passive"))
      (node (ref "C26") (pin "1") (pinfunction "1_1") (pintype "passive"))
      (node (ref "C27") (pin "1") (pintype "passive"))
      (node (ref "C28") (pin "1") (pintype "passive"))
      (node (ref "C29") (pin "1") (pinfunction "1_1") (pintype "passive"))
      (node (ref "C3") (pin "1") (pinfunction "1_1") (pintype "passive"))
      (node (ref "C30") (pin "1") (pinfunction "1_1") (pintype "passive"))
      (node (ref "C31") (pin "1") (pinfunction "1_1") (pintype "passive"))
      (node (ref "C32") (pin "1") (pintype "passive"))
      (node (ref "C33") (pin "1") (pintype "passive"))
      (node (ref "C34") (pin "1") (pintype "passive"))
      (node (ref "C35") (pin "1") (pintype "passive"))
      (node (ref "C36") (pin "1") (pintype "passive"))
      (node (ref "C37") (pin "1") (pintype "passive"))
      (node (ref "C38") (pin "1") (pinfunction "1_1") (pintype "passive"))
      (node (ref "C39") (pin "1") (pinfunction "1_1") (pintype "passive"))
      (node (ref "C4") (pin "1") (pintype "passive"))
      (node (ref "C40") (pin "1") (pinfunction "1_1") (pintype "passive"))
      (node (ref "C48") (pin "1") (pintype "passive"))
      (node (ref "L1") (pin "2") (pinfunction "2_2") (pintype "passive"))
      (node (ref "U1") (pin "1") (pinfunction "AVCC_1") (pintype "passive"))
      (node (ref "U1") (pin "37") (pinfunction "AVCC_37") (pintype "passive"))
      (node (ref "U1") (pin "38") (pinfunction "AVCC_38") (pintype "passive"))
      (node (ref "U1") (pin "48") (pinfunction "AVCC_48") (pintype "passive"))
      (node (ref "U14") (pin "6") (pinfunction "+V_6") (pintype "output"))
      (node (ref "U2") (pin "1") (pinfunction "AVCC_1") (pintype "passive"))
      (node (ref "U2") (pin "37") (pinfunction "AVCC_37") (pintype "passive"))
      (node (ref "U2") (pin "38") (pinfunction "AVCC_38") (pintype "passive"))
      (node (ref "U2") (pin "48") (pinfunction "AVCC_48") (pintype "passive"))
      (node (ref "U5") (pin "2") (pinfunction "VIN_2") (pintype "input"))
    )
    (net (code "366") (name "unconnected-(CAP3-Pad44)") (class "Default")
      (node (ref "CAP3") (pin "44") (pinfunction "44_44") (pintype "passive"))
    )
    (net (code "367") (name "unconnected-(CAP3-Pad46)") (class "Default")
      (node (ref "CAP3") (pin "46") (pinfunction "46_46") (pintype "passive"))
    )
    (net (code "368") (name "unconnected-(CAP3-Pad48)") (class "Default")
      (node (ref "CAP3") (pin "48") (pinfunction "48_48") (pintype "passive"))
    )
    (net (code "369") (name "unconnected-(CAP3-Pad50)") (class "Default")
      (node (ref "CAP3") (pin "50") (pinfunction "50_50") (pintype "passive"))
    )
    (net (code "370") (name "unconnected-(CAP3-Pad52)") (class "Default")
      (node (ref "CAP3") (pin "52") (pinfunction "52_52") (pintype "passive"))
    )
    (net (code "371") (name "unconnected-(J2-Pad5)") (class "Default")
      (node (ref "J2") (pin "5") (pinfunction "5_5") (pintype "passive"))
    )
    (net (code "372") (name "unconnected-(J2-Pad18)") (class "Default")
      (node (ref "J2") (pin "18") (pinfunction "18_18") (pintype "passive"))
    )
    (net (code "373") (name "unconnected-(J2-Pad20)") (class "Default")
      (node (ref "J2") (pin "20") (pinfunction "20_20") (pintype "passive"))
    )
    (net (code "374") (name "unconnected-(J2-Pad22)") (class "Default")
      (node (ref "J2") (pin "22") (pinfunction "22_22") (pintype "passive"))
    )
    (net (code "375") (name "unconnected-(J2-Pad24)") (class "Default")
      (node (ref "J2") (pin "24") (pinfunction "24_24") (pintype "passive"))
    )
    (net (code "376") (name "unconnected-(J2-Pad26)") (class "Default")
      (node (ref "J2") (pin "26") (pinfunction "26_26") (pintype "passive"))
    )
    (net (code "377") (name "unconnected-(J2-Pad28)") (class "Default")
      (node (ref "J2") (pin "28") (pinfunction "28_28") (pintype "passive"))
    )
    (net (code "378") (name "unconnected-(J2-Pad30)") (class "Default")
      (node (ref "J2") (pin "30") (pinfunction "30_30") (pintype "passive"))
    )
    (net (code "379") (name "unconnected-(J2-Pad31)") (class "Default")
      (node (ref "J2") (pin "31") (pinfunction "31_31") (pintype "passive"))
    )
    (net (code "380") (name "unconnected-(J2-Pad32)") (class "Default")
      (node (ref "J2") (pin "32") (pinfunction "32_32") (pintype "passive"))
    )
    (net (code "381") (name "unconnected-(J2-Pad34)") (class "Default")
      (node (ref "J2") (pin "34") (pinfunction "34_34") (pintype "passive"))
    )
    (net (code "382") (name "unconnected-(J2-Pad36)") (class "Default")
      (node (ref "J2") (pin "36") (pinfunction "36_36") (pintype "passive"))
    )
    (net (code "383") (name "unconnected-(J2-Pad38)") (class "Default")
      (node (ref "J2") (pin "38") (pinfunction "38_38") (pintype "passive"))
    )
    (net (code "384") (name "unconnected-(J2-Pad39)") (class "Default")
      (node (ref "J2") (pin "39") (pinfunction "39_39") (pintype "passive"))
    )
    (net (code "385") (name "unconnected-(J2-Pad40)") (class "Default")
      (node (ref "J2") (pin "40") (pinfunction "40_40") (pintype "passive"))
    )
    (net (code "386") (name "unconnected-(J3-Pad2)") (class "Default")
      (node (ref "J3") (pin "2") (pinfunction "2_2") (pintype "passive"))
    )
    (net (code "387") (name "unconnected-(J3-Pad4)") (class "Default")
      (node (ref "J3") (pin "4") (pinfunction "4_4") (pintype "passive"))
    )
    (net (code "388") (name "unconnected-(J3-Pad5)") (class "Default")
      (node (ref "J3") (pin "5") (pinfunction "5_5") (pintype "passive"))
    )
    (net (code "389") (name "unconnected-(J3-Pad6)") (class "Default")
      (node (ref "J3") (pin "6") (pinfunction "6_6") (pintype "passive"))
    )
    (net (code "390") (name "unconnected-(J3-Pad8)") (class "Default")
      (node (ref "J3") (pin "8") (pinfunction "8_8") (pintype "passive"))
    )
    (net (code "391") (name "unconnected-(J3-Pad10)") (class "Default")
      (node (ref "J3") (pin "10") (pinfunction "10_10") (pintype "passive"))
    )
    (net (code "392") (name "unconnected-(J3-Pad12)") (class "Default")
      (node (ref "J3") (pin "12") (pinfunction "12_12") (pintype "passive"))
    )
    (net (code "393") (name "unconnected-(J3-Pad13)") (class "Default")
      (node (ref "J3") (pin "13") (pinfunction "13_13") (pintype "passive"))
    )
    (net (code "394") (name "unconnected-(J3-Pad14)") (class "Default")
      (node (ref "J3") (pin "14") (pinfunction "14_14") (pintype "passive"))
    )
    (net (code "395") (name "unconnected-(J3-Pad15)") (class "Default")
      (node (ref "J3") (pin "15") (pinfunction "15_15") (pintype "passive"))
    )
    (net (code "396") (name "unconnected-(J3-Pad16)") (class "Default")
      (node (ref "J3") (pin "16") (pinfunction "16_16") (pintype "passive"))
    )
    (net (code "397") (name "unconnected-(J3-Pad17)") (class "Default")
      (node (ref "J3") (pin "17") (pinfunction "17_17") (pintype "passive"))
    )
    (net (code "398") (name "unconnected-(J3-Pad18)") (class "Default")
      (node (ref "J3") (pin "18") (pinfunction "18_18") (pintype "passive"))
    )
    (net (code "399") (name "unconnected-(J3-Pad19)") (class "Default")
      (node (ref "J3") (pin "19") (pinfunction "19_19") (pintype "passive"))
    )
    (net (code "400") (name "unconnected-(J3-Pad20)") (class "Default")
      (node (ref "J3") (pin "20") (pinfunction "20_20") (pintype "passive"))
    )
    (net (code "401") (name "unconnected-(J3-Pad21)") (class "Default")
      (node (ref "J3") (pin "21") (pinfunction "21_21") (pintype "passive"))
    )
    (net (code "402") (name "unconnected-(J3-Pad22)") (class "Default")
      (node (ref "J3") (pin "22") (pinfunction "22_22") (pintype "passive"))
    )
    (net (code "403") (name "unconnected-(J3-Pad23)") (class "Default")
      (node (ref "J3") (pin "23") (pinfunction "23_23") (pintype "passive"))
    )
    (net (code "404") (name "unconnected-(J3-Pad24)") (class "Default")
      (node (ref "J3") (pin "24") (pinfunction "24_24") (pintype "passive"))
    )
    (net (code "405") (name "unconnected-(J3-Pad25)") (class "Default")
      (node (ref "J3") (pin "25") (pinfunction "25_25") (pintype "passive"))
    )
    (net (code "406") (name "unconnected-(J3-Pad26)") (class "Default")
      (node (ref "J3") (pin "26") (pinfunction "26_26") (pintype "passive"))
    )
    (net (code "407") (name "unconnected-(J3-Pad27)") (class "Default")
      (node (ref "J3") (pin "27") (pinfunction "27_27") (pintype "passive"))
    )
    (net (code "408") (name "unconnected-(J3-Pad28)") (class "Default")
      (node (ref "J3") (pin "28") (pinfunction "28_28") (pintype "passive"))
    )
    (net (code "409") (name "unconnected-(J3-Pad30)") (class "Default")
      (node (ref "J3") (pin "30") (pinfunction "30_30") (pintype "passive"))
    )
    (net (code "410") (name "unconnected-(J3-Pad32)") (class "Default")
      (node (ref "J3") (pin "32") (pinfunction "32_32") (pintype "passive"))
    )
    (net (code "411") (name "unconnected-(J3-Pad34)") (class "Default")
      (node (ref "J3") (pin "34") (pinfunction "34_34") (pintype "passive"))
    )
    (net (code "412") (name "unconnected-(J3-Pad36)") (class "Default")
      (node (ref "J3") (pin "36") (pinfunction "36_36") (pintype "passive"))
    )
    (net (code "413") (name "unconnected-(J3-Pad38)") (class "Default")
      (node (ref "J3") (pin "38") (pinfunction "38_38") (pintype "passive"))
    )
    (net (code "414") (name "unconnected-(J3-Pad40)") (class "Default")
      (node (ref "J3") (pin "40") (pinfunction "40_40") (pintype "passive"))
    )
    (net (code "415") (name "unconnected-(J5-Pad10)") (class "Default")
      (node (ref "J5") (pin "10") (pinfunction "10_10") (pintype "passive"))
    )
    (net (code "416") (name "unconnected-(J5-Pad15)") (class "Default")
      (node (ref "J5") (pin "15") (pinfunction "15_15") (pintype "passive"))
    )
    (net (code "417") (name "unconnected-(J6-Pad8)") (class "Default")
      (node (ref "J6") (pin "8") (pinfunction "8_8") (pintype "passive"))
    )
    (net (code "418") (name "unconnected-(J6-Pad9)") (class "Default")
      (node (ref "J6") (pin "9") (pinfunction "9_9") (pintype "passive"))
    )
    (net (code "419") (name "unconnected-(J6-Pad10)") (class "Default")
      (node (ref "J6") (pin "10") (pinfunction "10_10") (pintype "passive"))
    )
    (net (code "420") (name "unconnected-(J6-Pad11)") (class "Default")
      (node (ref "J6") (pin "11") (pinfunction "11_11") (pintype "passive"))
    )
    (net (code "421") (name "unconnected-(J6-Pad12)") (class "Default")
      (node (ref "J6") (pin "12") (pinfunction "12_12") (pintype "passive"))
    )
    (net (code "422") (name "unconnected-(J6-Pad13)") (class "Default")
      (node (ref "J6") (pin "13") (pinfunction "13_13") (pintype "passive"))
    )
    (net (code "423") (name "unconnected-(J6-Pad14)") (class "Default")
      (node (ref "J6") (pin "14") (pinfunction "14_14") (pintype "passive"))
    )
    (net (code "424") (name "unconnected-(J6-Pad15)") (class "Default")
      (node (ref "J6") (pin "15") (pinfunction "15_15") (pintype "passive"))
    )
    (net (code "425") (name "unconnected-(J8-Pad3)") (class "Default")
      (node (ref "J8") (pin "3") (pinfunction "3_3") (pintype "passive"))
    )
    (net (code "426") (name "unconnected-(J8-Pad4)") (class "Default")
      (node (ref "J8") (pin "4") (pinfunction "4_4") (pintype "passive"))
    )
    (net (code "427") (name "unconnected-(P9-Pad3)") (class "Default")
      (node (ref "P9") (pin "3") (pinfunction "3_3") (pintype "passive"))
    )
    (net (code "428") (name "unconnected-(P9-Pad5)") (class "Default")
      (node (ref "P9") (pin "5") (pinfunction "5_5") (pintype "passive"))
    )
    (net (code "429") (name "unconnected-(P9-Pad8)") (class "Default")
      (node (ref "P9") (pin "8") (pinfunction "8_8") (pintype "passive"))
    )
    (net (code "430") (name "unconnected-(P9-Pad10)") (class "Default")
      (node (ref "P9") (pin "10") (pinfunction "10_10") (pintype "passive"))
    )
    (net (code "431") (name "unconnected-(RS232-1-Pad2)") (class "Default")
      (node (ref "RS232-1") (pin "2") (pinfunction "2_2") (pintype "passive"))
    )
    (net (code "432") (name "unconnected-(RS232-1-Pad5)") (class "Default")
      (node (ref "RS232-1") (pin "5") (pinfunction "5_5") (pintype "passive"))
    )
    (net (code "433") (name "unconnected-(RS232-1-Pad6)") (class "Default")
      (node (ref "RS232-1") (pin "6") (pinfunction "6_6") (pintype "passive"))
    )
    (net (code "434") (name "unconnected-(RS232-1-Pad7)") (class "Default")
      (node (ref "RS232-1") (pin "7") (pinfunction "7_7") (pintype "passive"))
    )
    (net (code "435") (name "unconnected-(RS232-1-Pad8)") (class "Default")
      (node (ref "RS232-1") (pin "8") (pinfunction "8_8") (pintype "passive"))
    )
    (net (code "436") (name "unconnected-(RS232-1-Pad9)") (class "Default")
      (node (ref "RS232-1") (pin "9") (pinfunction "9_9") (pintype "passive"))
    )
    (net (code "437") (name "unconnected-(RS232-2-Pad2)") (class "Default")
      (node (ref "RS232-2") (pin "2") (pinfunction "2_2") (pintype "passive"))
    )
    (net (code "438") (name "unconnected-(RS232-2-Pad5)") (class "Default")
      (node (ref "RS232-2") (pin "5") (pinfunction "5_5") (pintype "passive"))
    )
    (net (code "439") (name "unconnected-(RS232-2-Pad6)") (class "Default")
      (node (ref "RS232-2") (pin "6") (pinfunction "6_6") (pintype "passive"))
    )
    (net (code "440") (name "unconnected-(RS232-2-Pad7)") (class "Default")
      (node (ref "RS232-2") (pin "7") (pinfunction "7_7") (pintype "passive"))
    )
    (net (code "441") (name "unconnected-(RS232-2-Pad8)") (class "Default")
      (node (ref "RS232-2") (pin "8") (pinfunction "8_8") (pintype "passive"))
    )
    (net (code "442") (name "unconnected-(RS232-2-Pad9)") (class "Default")
      (node (ref "RS232-2") (pin "9") (pinfunction "9_9") (pintype "passive"))
    )
    (net (code "443") (name "unconnected-(U1-FRSTDATA-Pad15)") (class "Default")
      (node (ref "U1") (pin "15") (pinfunction "FRSTDATA_15") (pintype "passive"))
    )
    (net (code "444") (name "unconnected-(U2-FRSTDATA-Pad15)") (class "Default")
      (node (ref "U2") (pin "15") (pinfunction "FRSTDATA_15") (pintype "passive"))
    )
    (net (code "445") (name "unconnected-(U5-NIC-Pad3)") (class "Default")
      (node (ref "U5") (pin "3") (pinfunction "NIC_3") (pintype "bidirectional"))
    )
    (net (code "446") (name "unconnected-(U5-NIC-Pad7)") (class "Default")
      (node (ref "U5") (pin "7") (pinfunction "NIC_7") (pintype "bidirectional"))
    )
    (net (code "447") (name "unconnected-(U5-TP-Pad1)") (class "Default")
      (node (ref "U5") (pin "1") (pinfunction "TP_1") (pintype "bidirectional"))
    )
    (net (code "448") (name "unconnected-(U5-TP-Pad8)") (class "Default")
      (node (ref "U5") (pin "8") (pinfunction "TP_8") (pintype "bidirectional"))
    )
    (net (code "449") (name "unconnected-(U5-TRIM-Pad5)") (class "Default")
      (node (ref "U5") (pin "5") (pinfunction "TRIM_5") (pintype "input"))
    )
    (net (code "450") (name "unconnected-(U6-A0-Pad8)") (class "Default")
      (node (ref "U6") (pin "8") (pinfunction "A0_8") (pintype "bidirectional"))
    )
    (net (code "451") (name "unconnected-(U6-BZ{slash}D4-Pad19)") (class "Default")
      (node (ref "U6") (pin "19") (pinfunction "BZ/D4_19") (pintype "bidirectional"))
    )
    (net (code "452") (name "unconnected-(U6-D0-Pad15)") (class "Default")
      (node (ref "U6") (pin "15") (pinfunction "D0_15") (pintype "bidirectional"))
    )
    (net (code "453") (name "unconnected-(U6-D1-Pad16)") (class "Default")
      (node (ref "U6") (pin "16") (pinfunction "D1_16") (pintype "bidirectional"))
    )
    (net (code "454") (name "unconnected-(U6-D2-Pad17)") (class "Default")
      (node (ref "U6") (pin "17") (pinfunction "D2_17") (pintype "bidirectional"))
    )
    (net (code "455") (name "unconnected-(U6-PCS#-Pad27)") (class "Default")
      (node (ref "U6") (pin "27") (pinfunction "PCS#_27") (pintype "input"))
    )
    (net (code "456") (name "unconnected-(U6-RSTI-Pad2)") (class "Default")
      (node (ref "U6") (pin "2") (pinfunction "RSTI_2") (pintype "input"))
    )
    (net (code "457") (name "unconnected-(U6-RXD-Pad6)") (class "Default")
      (node (ref "U6") (pin "6") (pinfunction "RXD_6") (pintype "input"))
    )
    (net (code "458") (name "unconnected-(U6-SD_CK-Pad26)") (class "Default")
      (node (ref "U6") (pin "26") (pinfunction "SD_CK_26") (pintype "output"))
    )
    (net (code "459") (name "unconnected-(U6-SD_CS-Pad23)") (class "Default")
      (node (ref "U6") (pin "23") (pinfunction "SD_CS_23") (pintype "output"))
    )
    (net (code "460") (name "unconnected-(U6-SD_DI-Pad7)") (class "Default")
      (node (ref "U6") (pin "7") (pinfunction "SD_DI_7") (pintype "input"))
    )
    (net (code "461") (name "unconnected-(U6-SD_DO-Pad25)") (class "Default")
      (node (ref "U6") (pin "25") (pinfunction "SD_DO_25") (pintype "output"))
    )
    (net (code "462") (name "unconnected-(U6-TXD-Pad5)") (class "Default")
      (node (ref "U6") (pin "5") (pinfunction "TXD_5") (pintype "bidirectional"))
    )
    (net (code "463") (name "unconnected-(U10-VREF-Pad5)") (class "Default")
      (node (ref "U10") (pin "5") (pinfunction "VREF_5") (pintype "passive"))
    )
    (net (code "464") (name "unconnected-(U12-A0-Pad99)") (class "Default")
      (node (ref "U12") (pin "99") (pinfunction "A0_99") (pintype "passive"))
    )
    (net (code "465") (name "unconnected-(U12-D0-Pad118)") (class "Default")
      (node (ref "U12") (pin "118") (pinfunction "D0_118") (pintype "passive"))
    )
    (net (code "466") (name "unconnected-(U12-D1-Pad119)") (class "Default")
      (node (ref "U12") (pin "119") (pinfunction "D1_119") (pintype "passive"))
    )
    (net (code "467") (name "unconnected-(U12-D2-Pad120)") (class "Default")
      (node (ref "U12") (pin "120") (pinfunction "D2_120") (pintype "passive"))
    )
    (net (code "468") (name "unconnected-(U12-D3-Pad121)") (class "Default")
      (node (ref "U12") (pin "121") (pinfunction "D3_121") (pintype "passive"))
    )
    (net (code "469") (name "unconnected-(U12-D4-Pad123)") (class "Default")
      (node (ref "U12") (pin "123") (pinfunction "D4_123") (pintype "passive"))
    )
    (net (code "470") (name "unconnected-(U12-D5-Pad124)") (class "Default")
      (node (ref "U12") (pin "124") (pinfunction "D5_124") (pintype "passive"))
    )
    (net (code "471") (name "unconnected-(U12-D6-Pad125)") (class "Default")
      (node (ref "U12") (pin "125") (pinfunction "D6_125") (pintype "passive"))
    )
    (net (code "472") (name "unconnected-(U12-D7-Pad126)") (class "Default")
      (node (ref "U12") (pin "126") (pinfunction "D7_126") (pintype "passive"))
    )
    (net (code "473") (name "unconnected-(U12-PCS#-Pad100)") (class "Default")
      (node (ref "U12") (pin "100") (pinfunction "PCS#_100") (pintype "passive"))
    )
    (net (code "474") (name "unconnected-(U12-RD#-Pad106)") (class "Default")
      (node (ref "U12") (pin "106") (pinfunction "RD#_106") (pintype "passive"))
    )
    (net (code "475") (name "unconnected-(U12-WR#-Pad107)") (class "Default")
      (node (ref "U12") (pin "107") (pinfunction "WR#_107") (pintype "passive"))
    )
    (net (code "476") (name "unconnected-(U13-1B5-Pad10)") (class "Default")
      (node (ref "U13") (pin "10") (pinfunction "1B5_10") (pintype "bidirectional"))
    )
    (net (code "477") (name "unconnected-(U13-2B1-Pad15)") (class "Default")
      (node (ref "U13") (pin "15") (pinfunction "2B1_15") (pintype "bidirectional"))
    )
    (net (code "478") (name "unconnected-(U13-2B2-Pad16)") (class "Default")
      (node (ref "U13") (pin "16") (pinfunction "2B2_16") (pintype "bidirectional"))
    )
    (net (code "479") (name "unconnected-(U28-Pad81)") (class "Default")
      (node (ref "U28") (pin "81") (pinfunction "81_81") (pintype "passive"))
    )
  )
)
